# nodeTestPanel.net
KiCad netlist of a schematic drawn in EAGLE
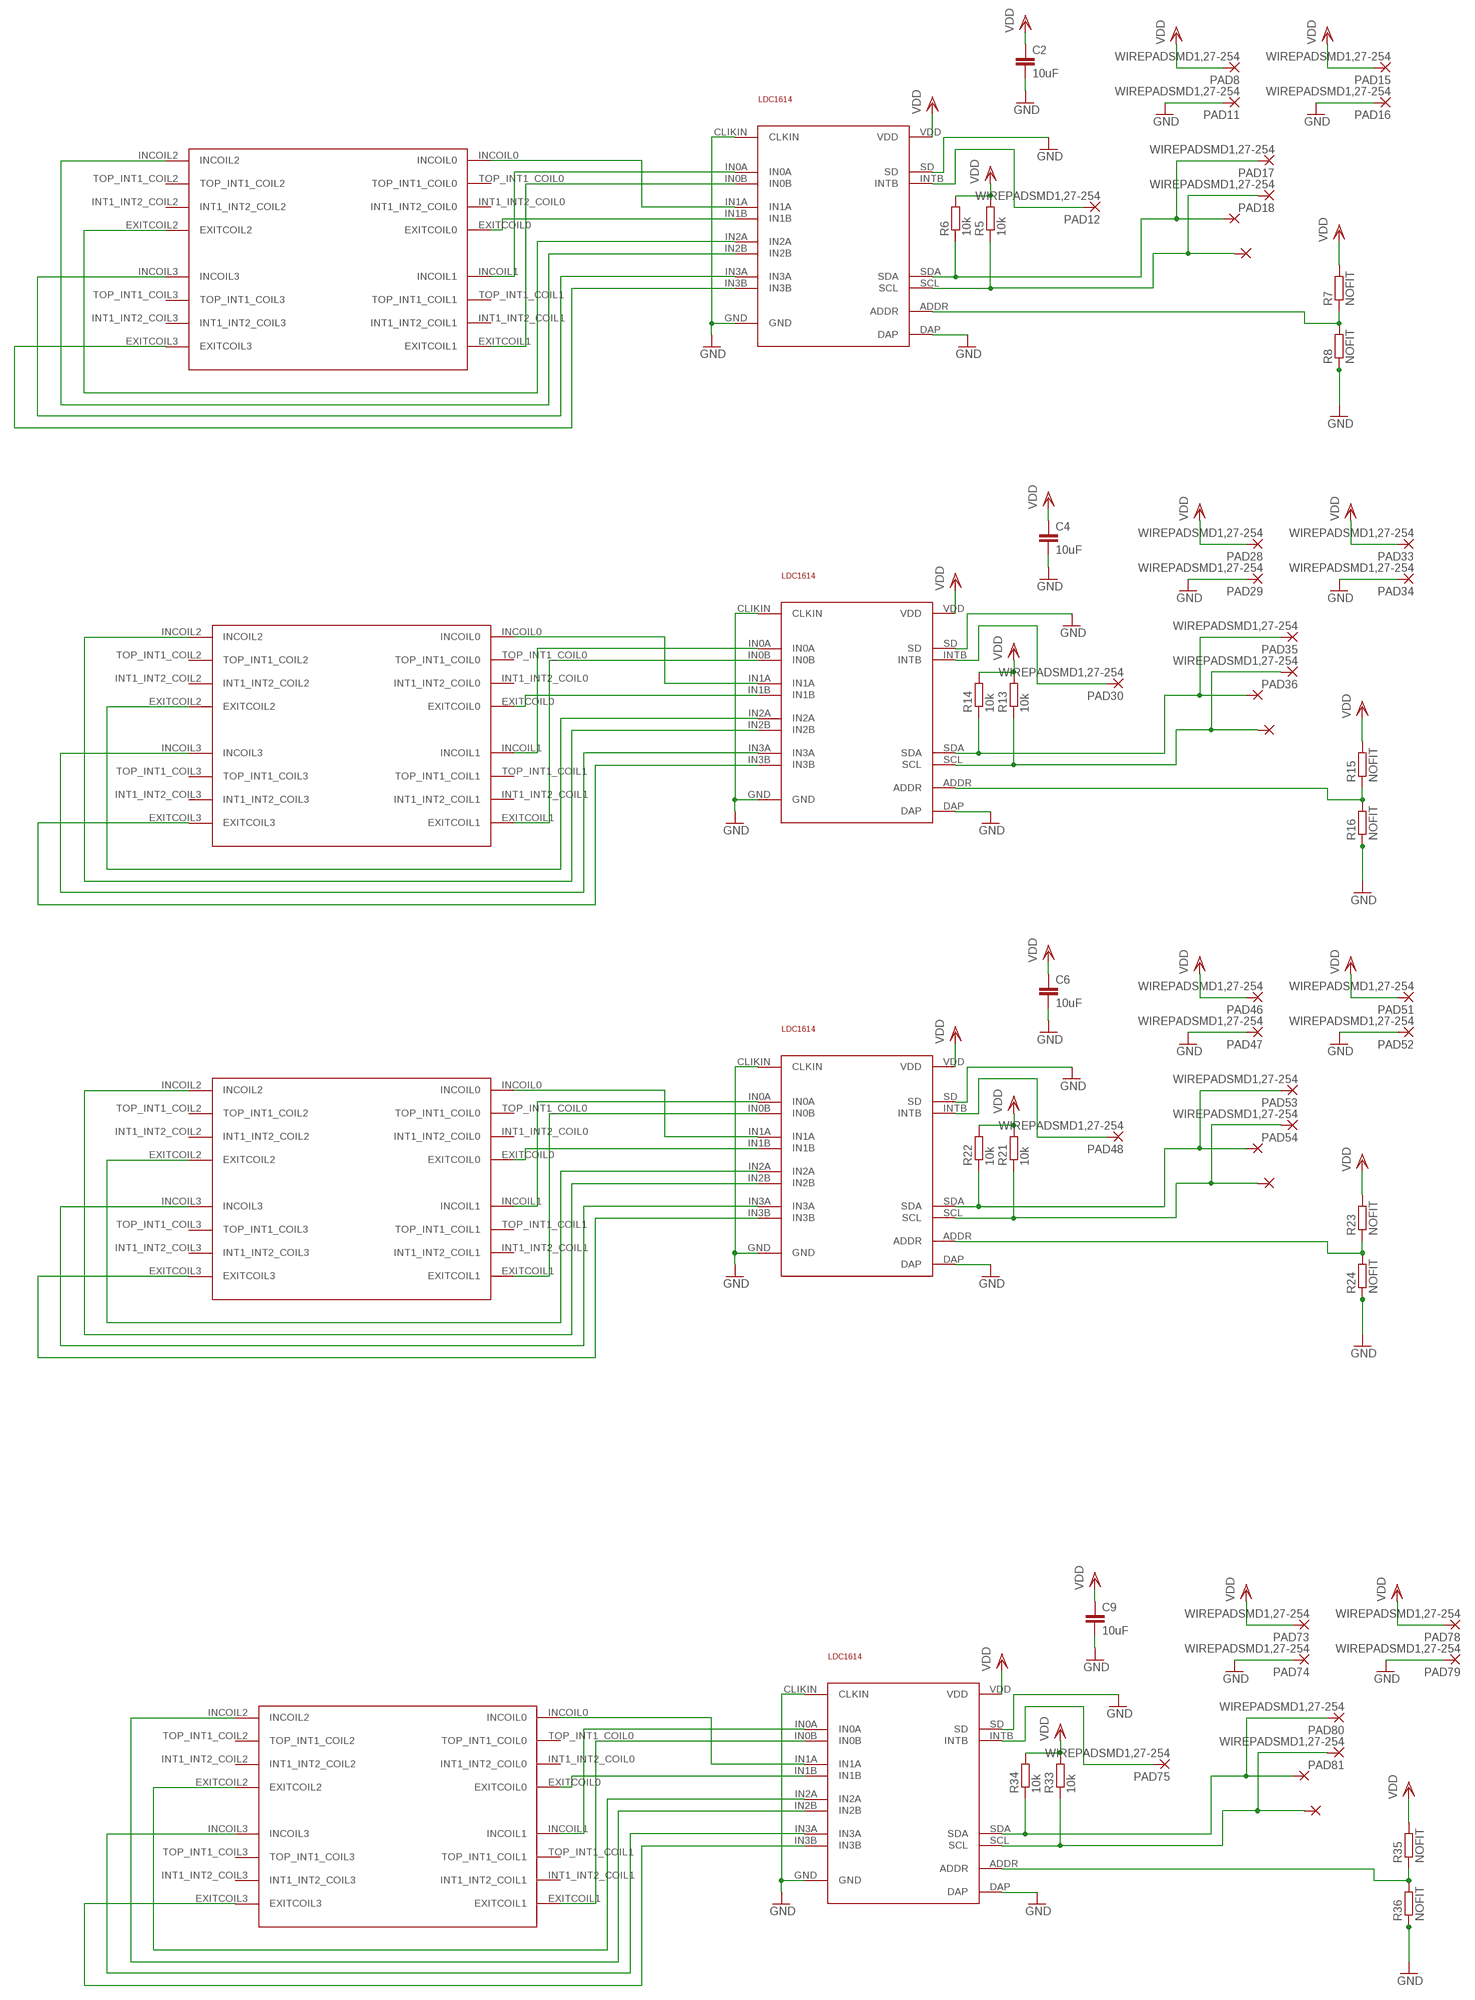
[diagram p0: schematic, sheet 1, part 1 of 3]
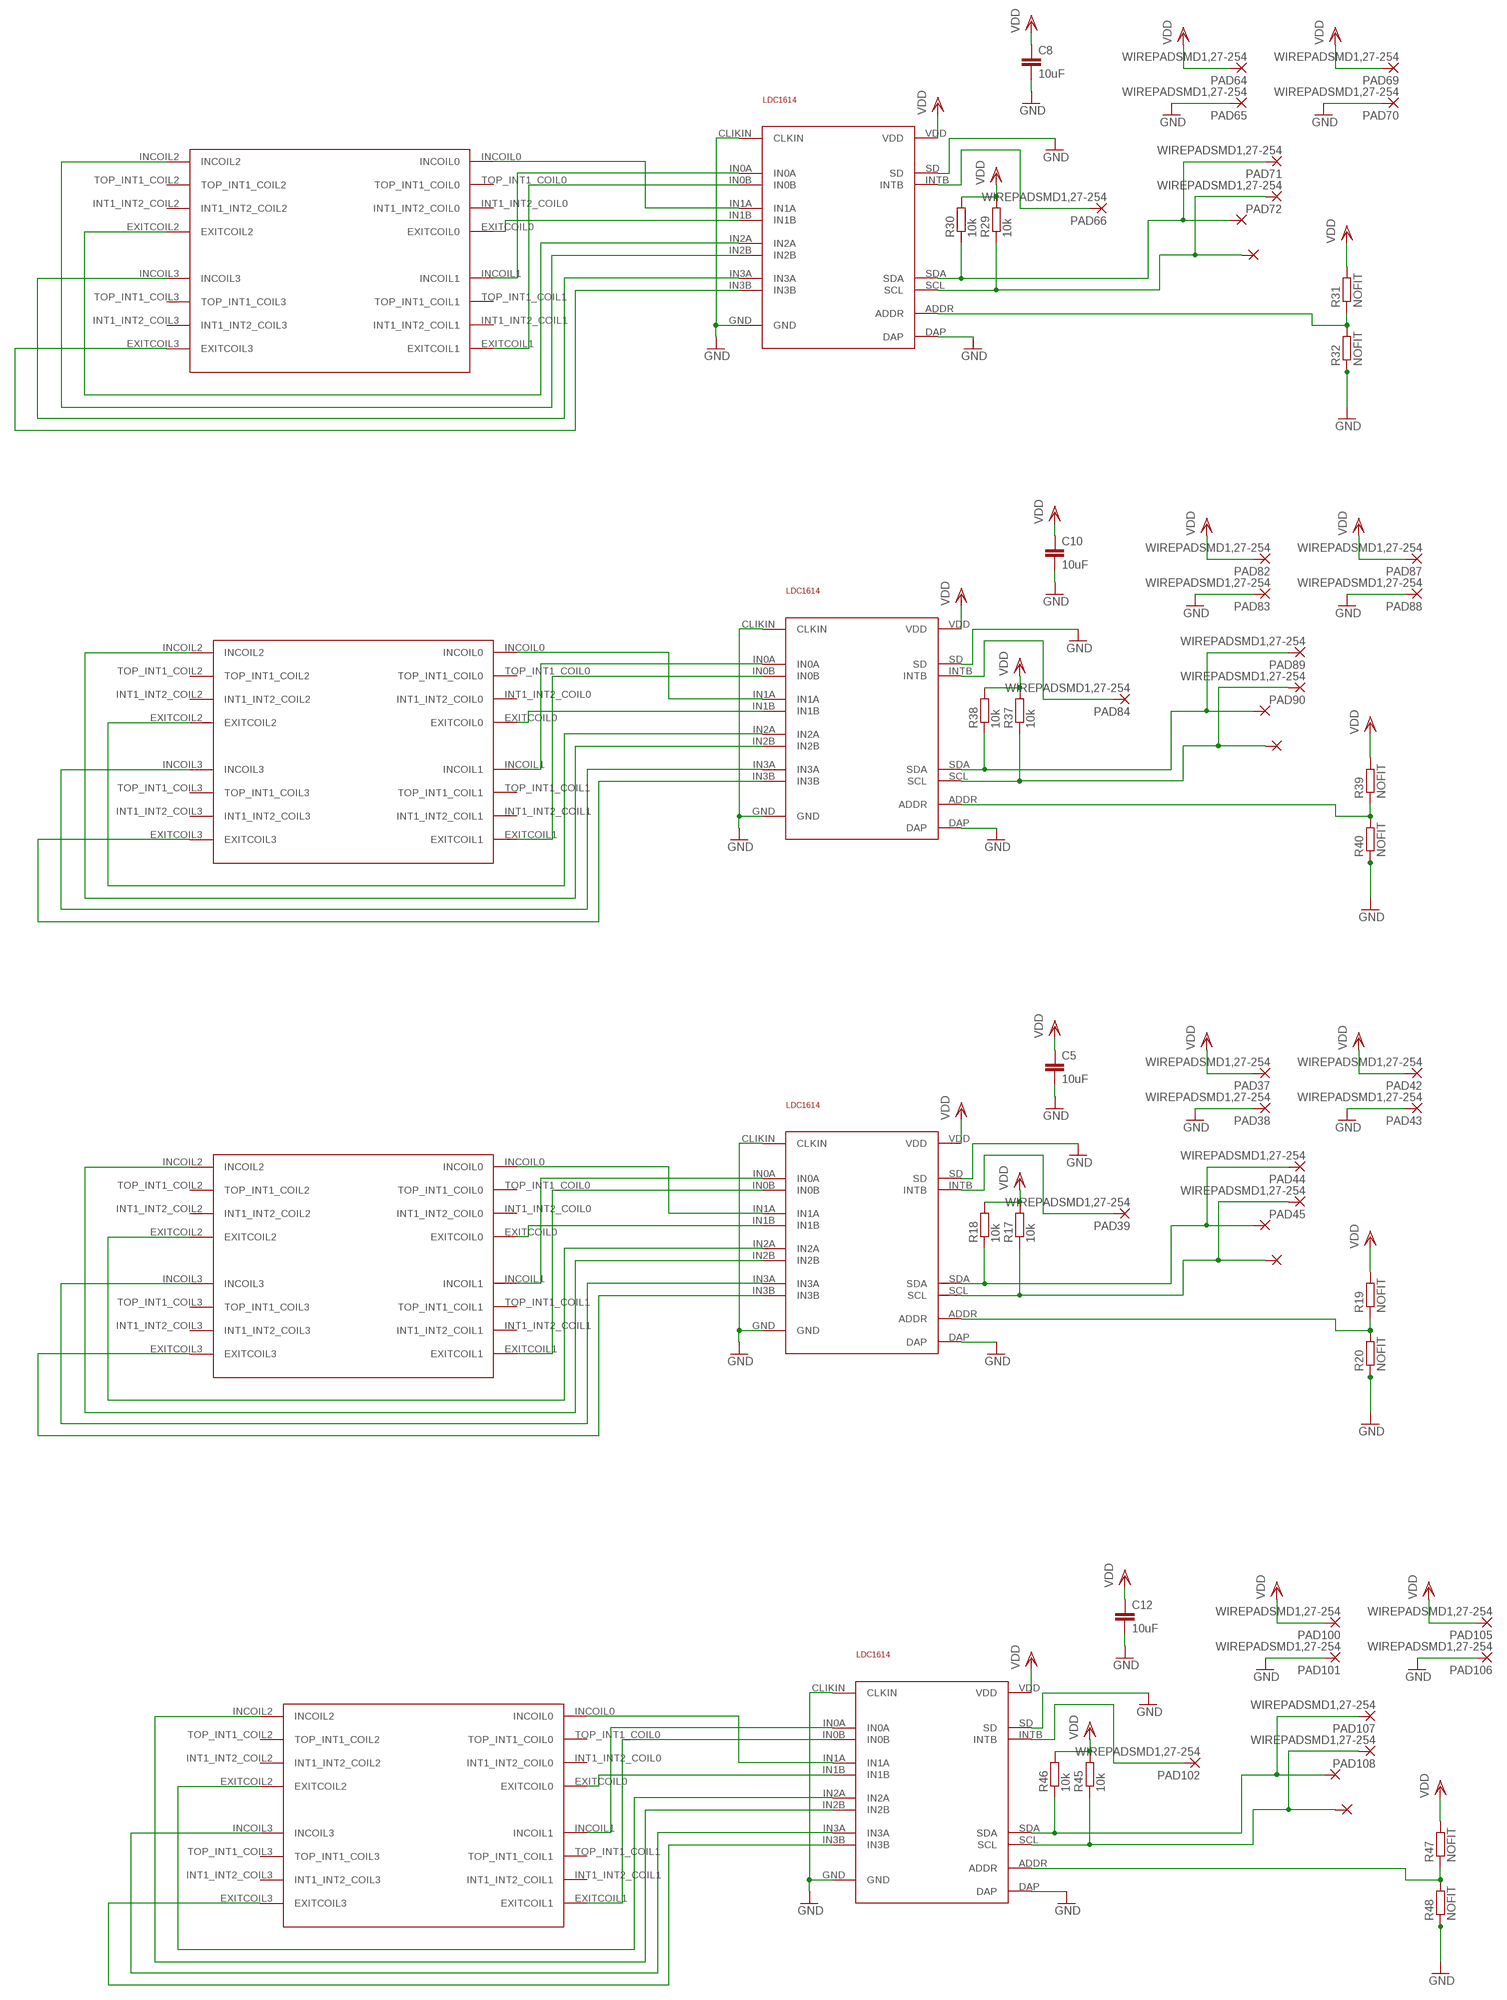
[diagram p1: schematic, sheet 1, part 2 of 3]
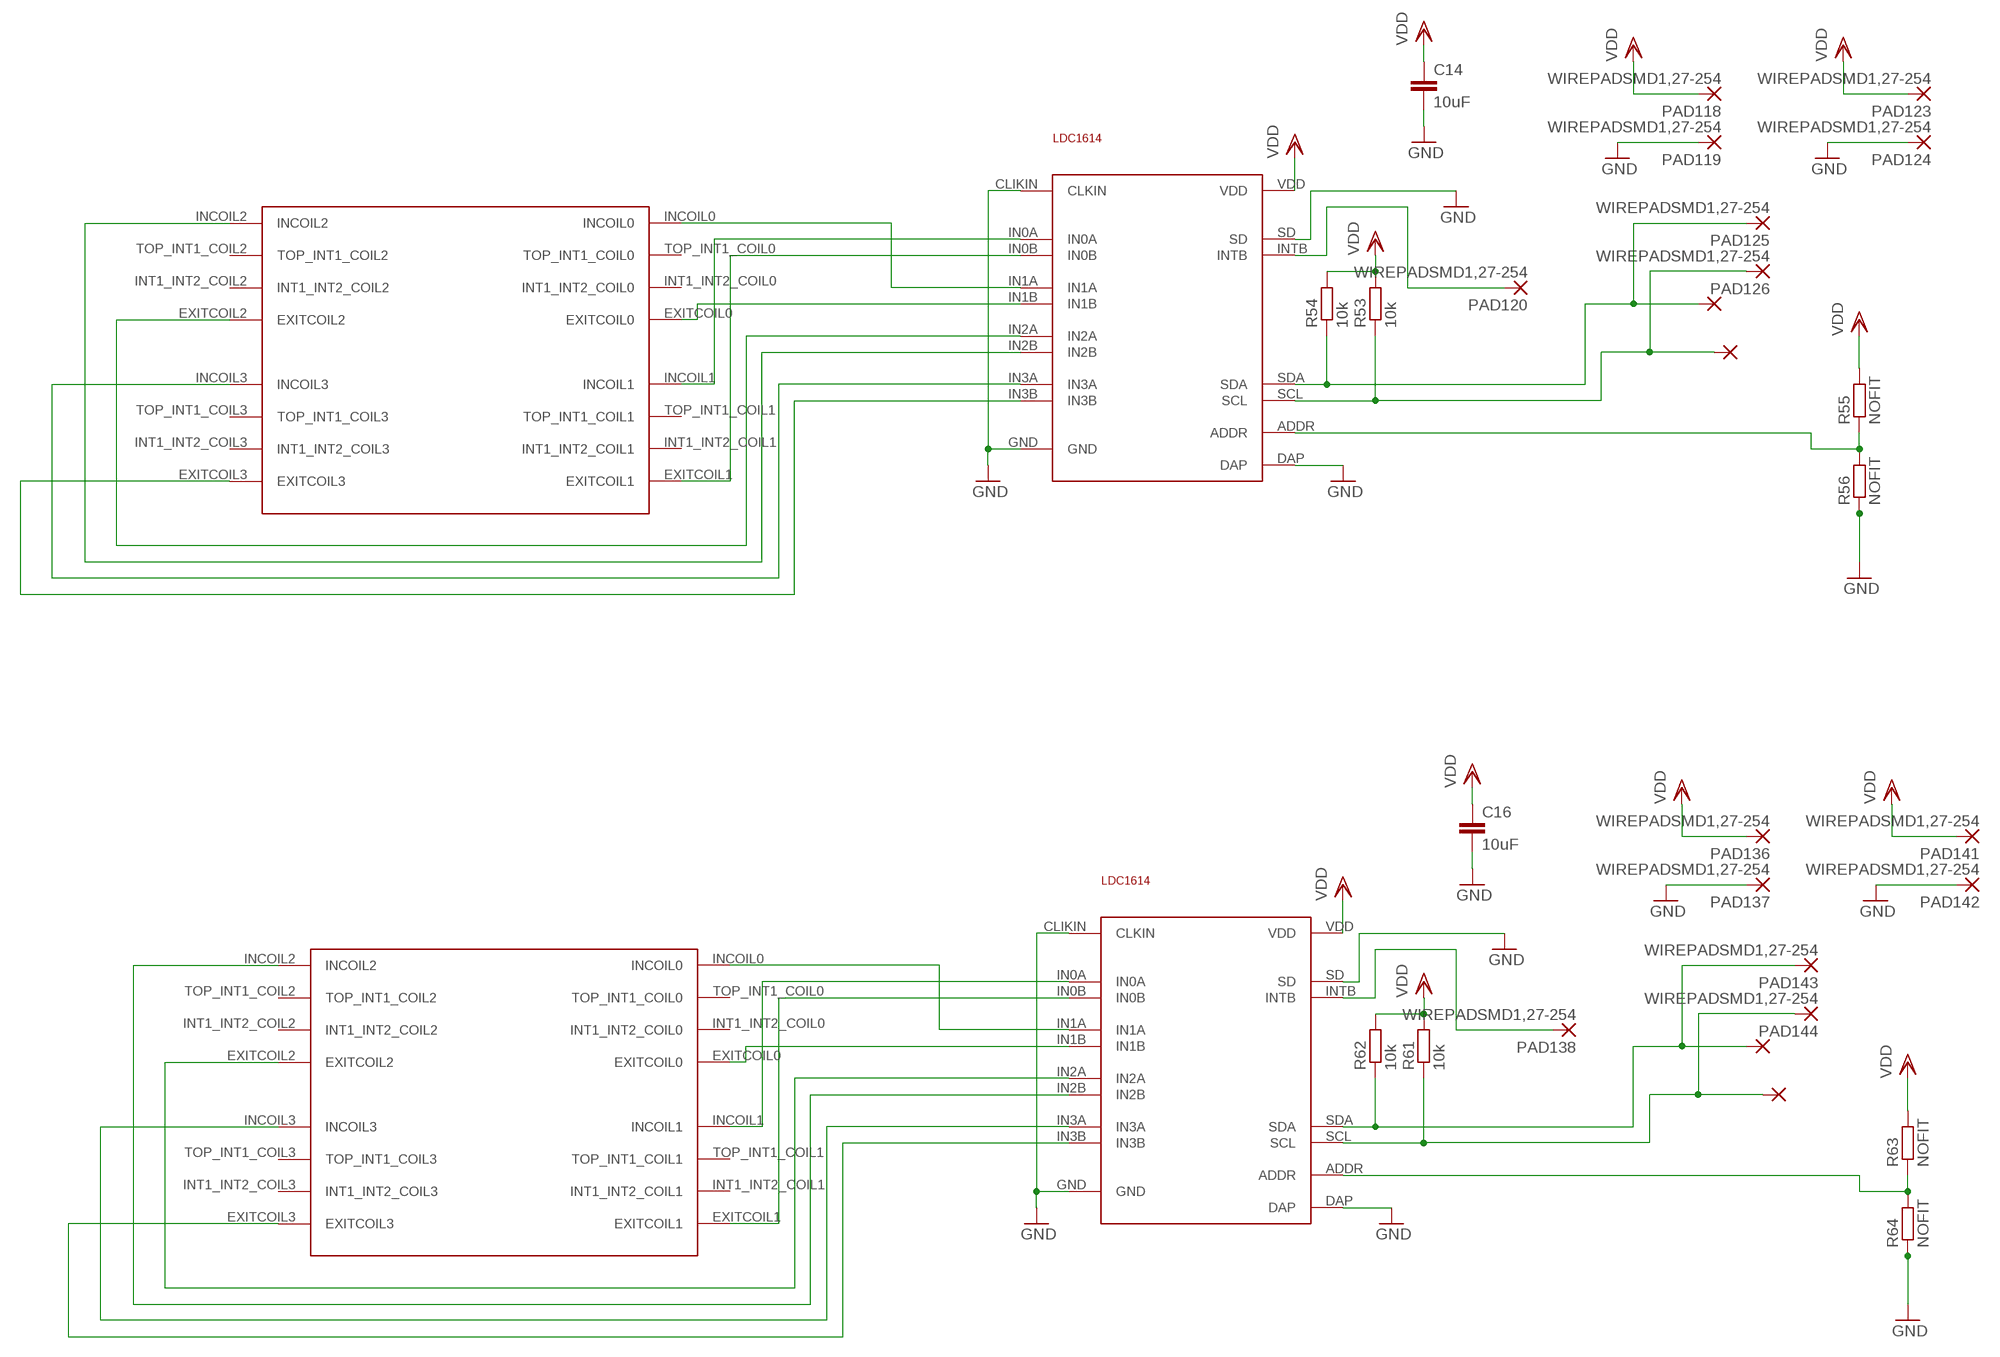
[diagram p2: schematic, sheet 1, part 3 of 3]
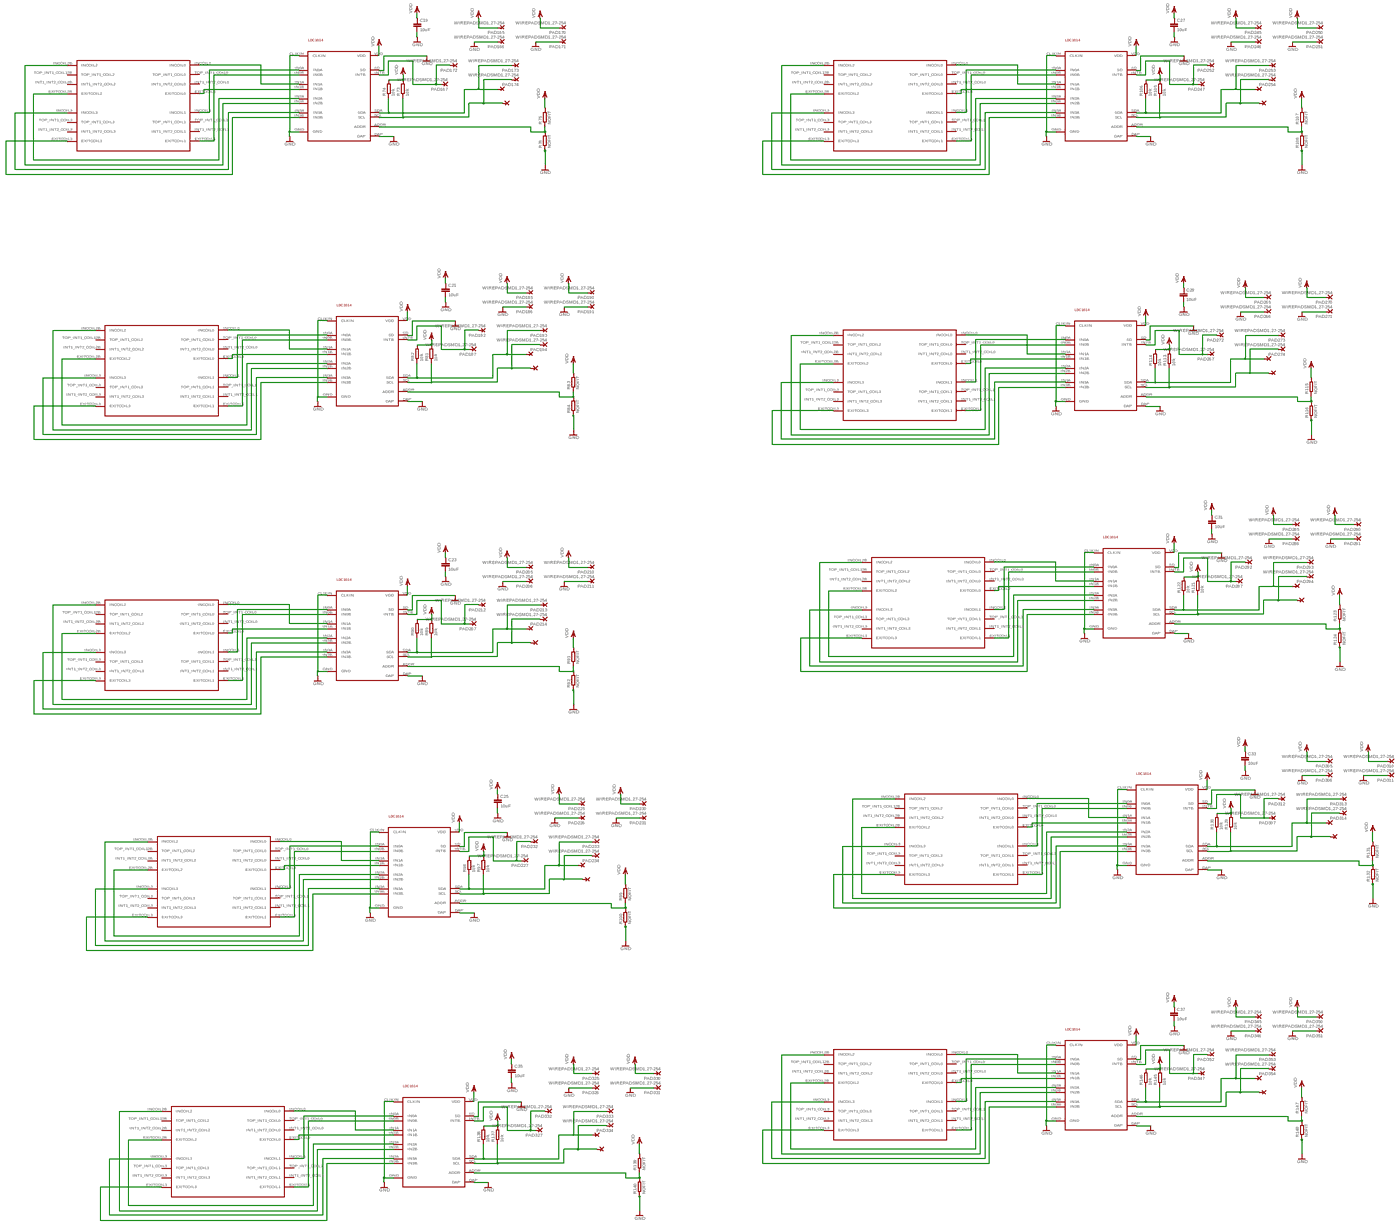
[diagram p3: schematic, sheet 2, overview]
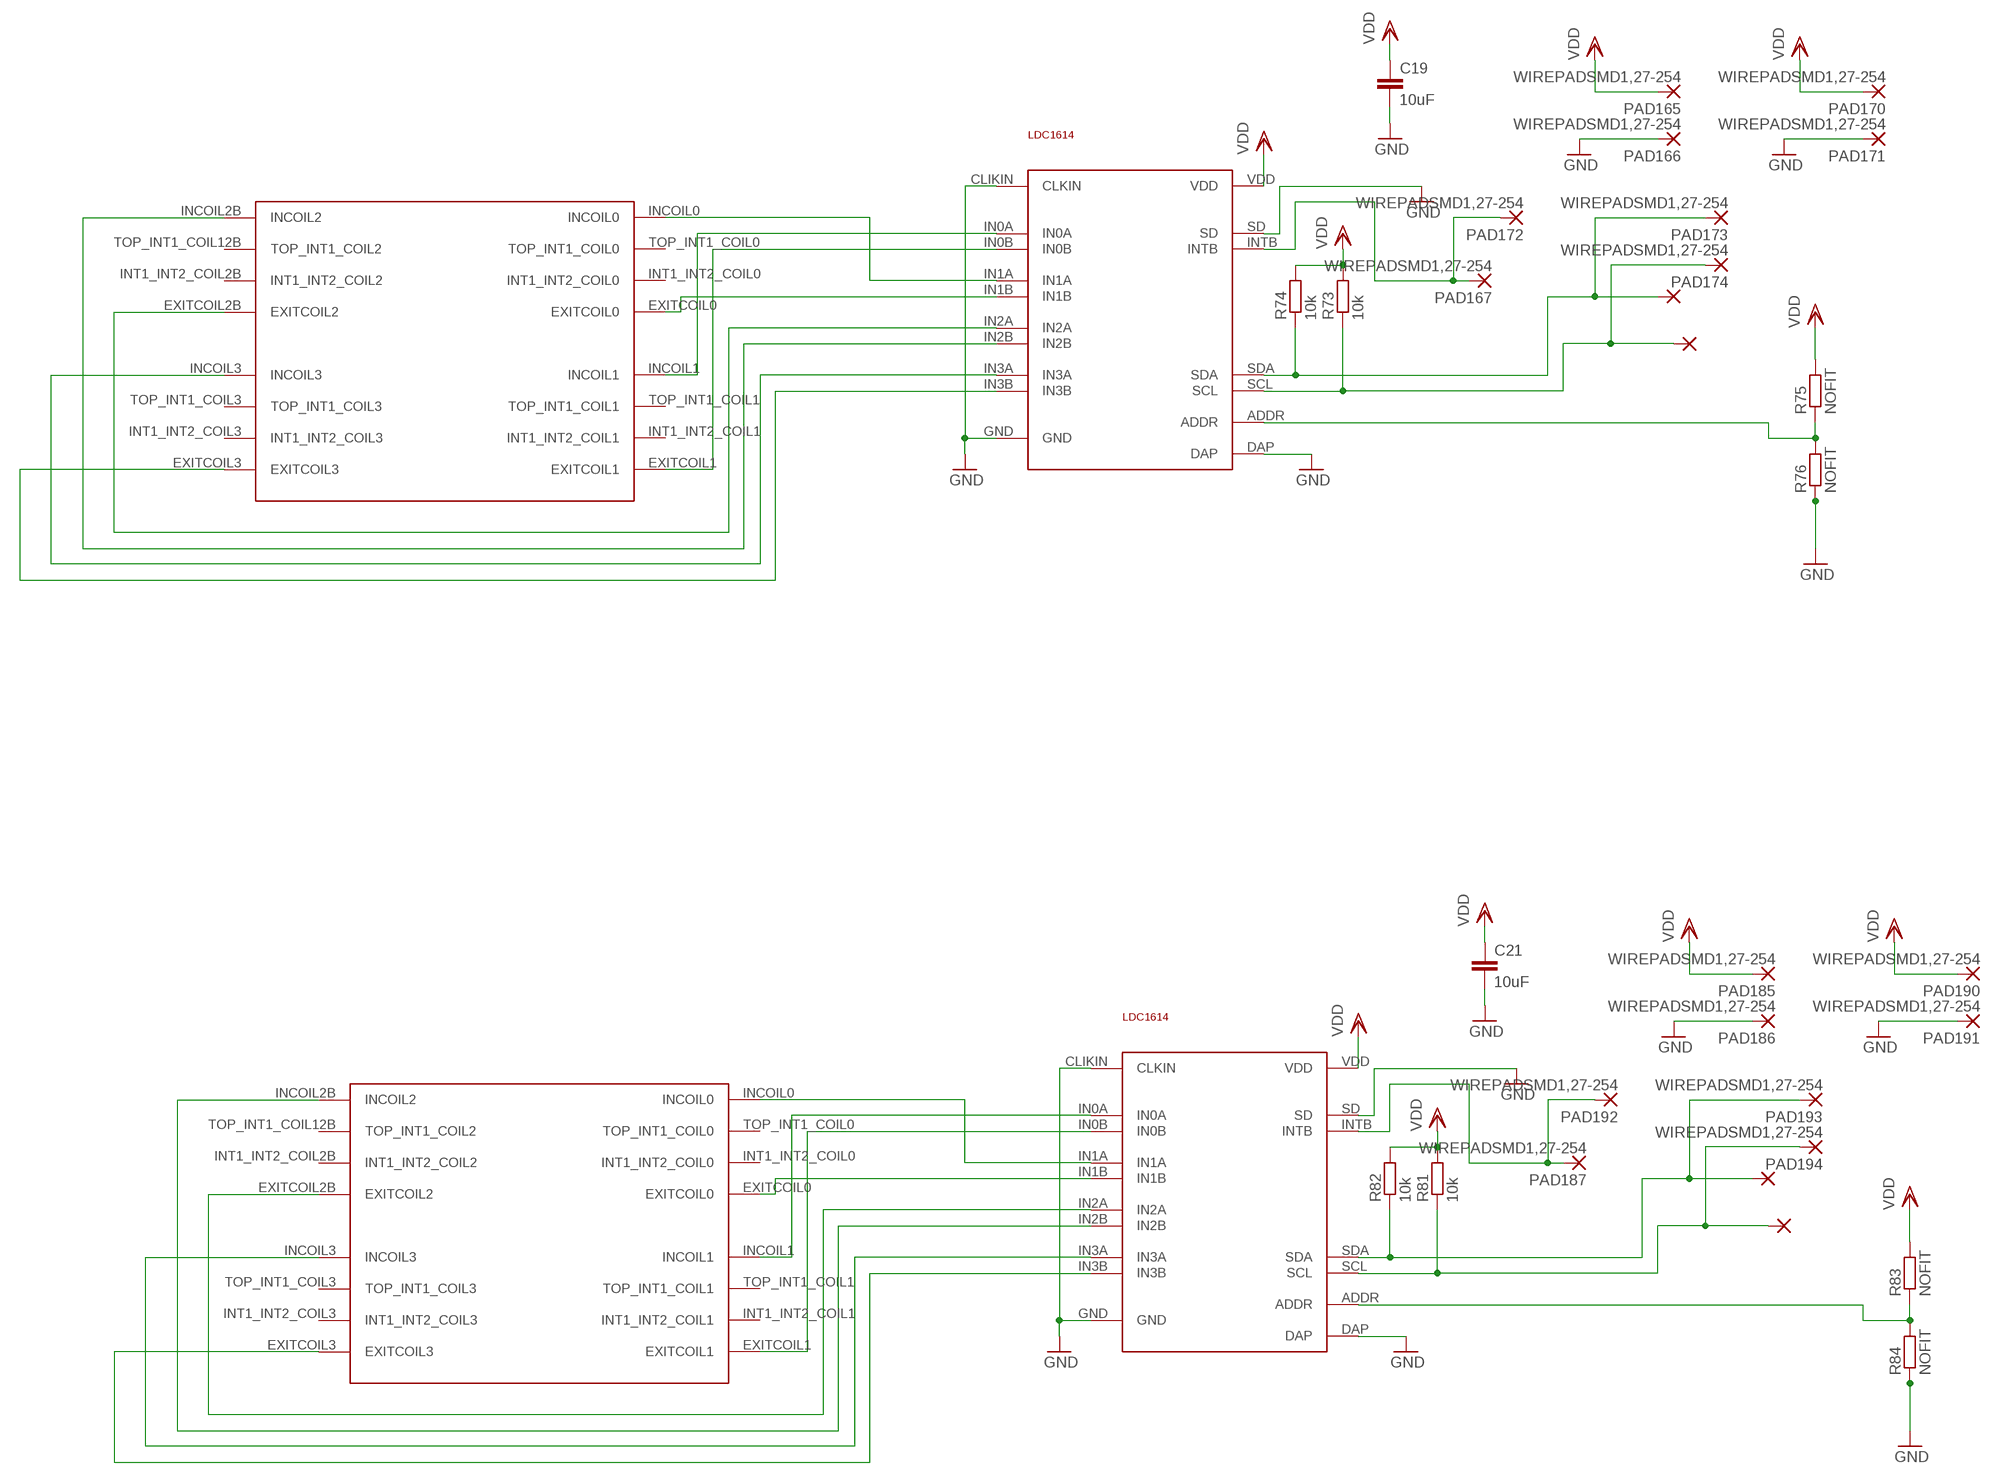
[diagram p4: schematic, sheet 2, part 1 of 4]
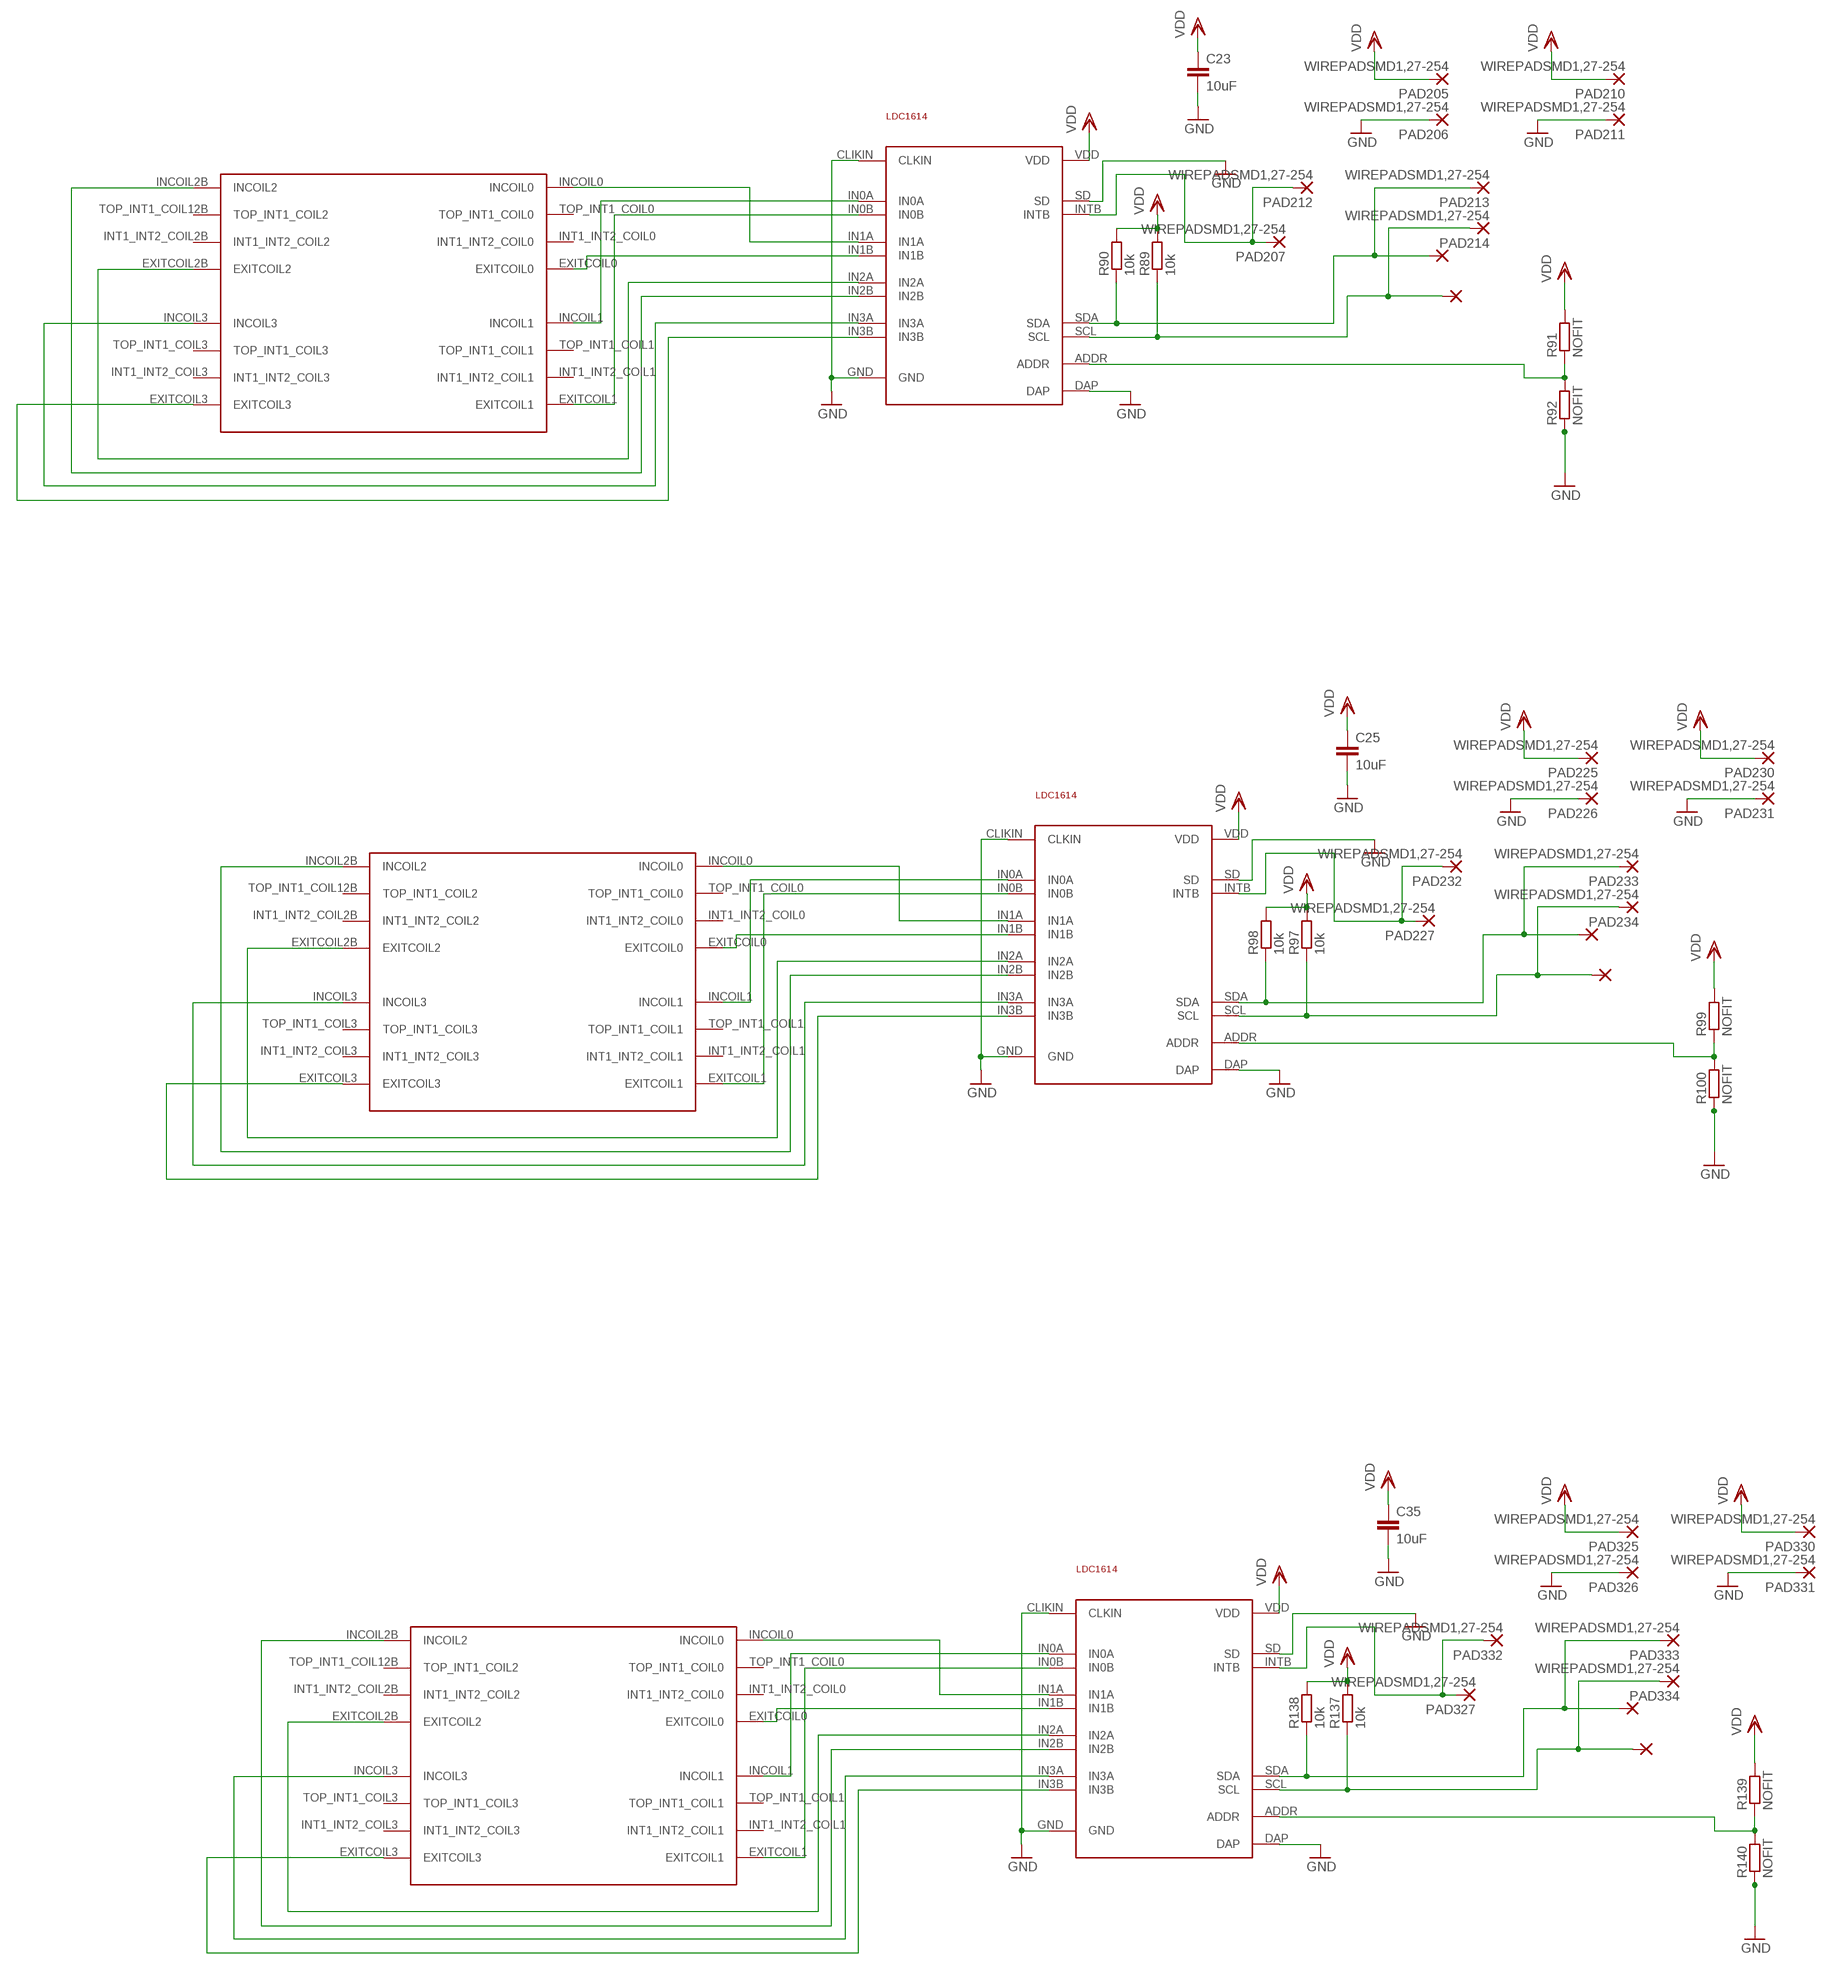
[diagram p5: schematic, sheet 2, part 2 of 4]
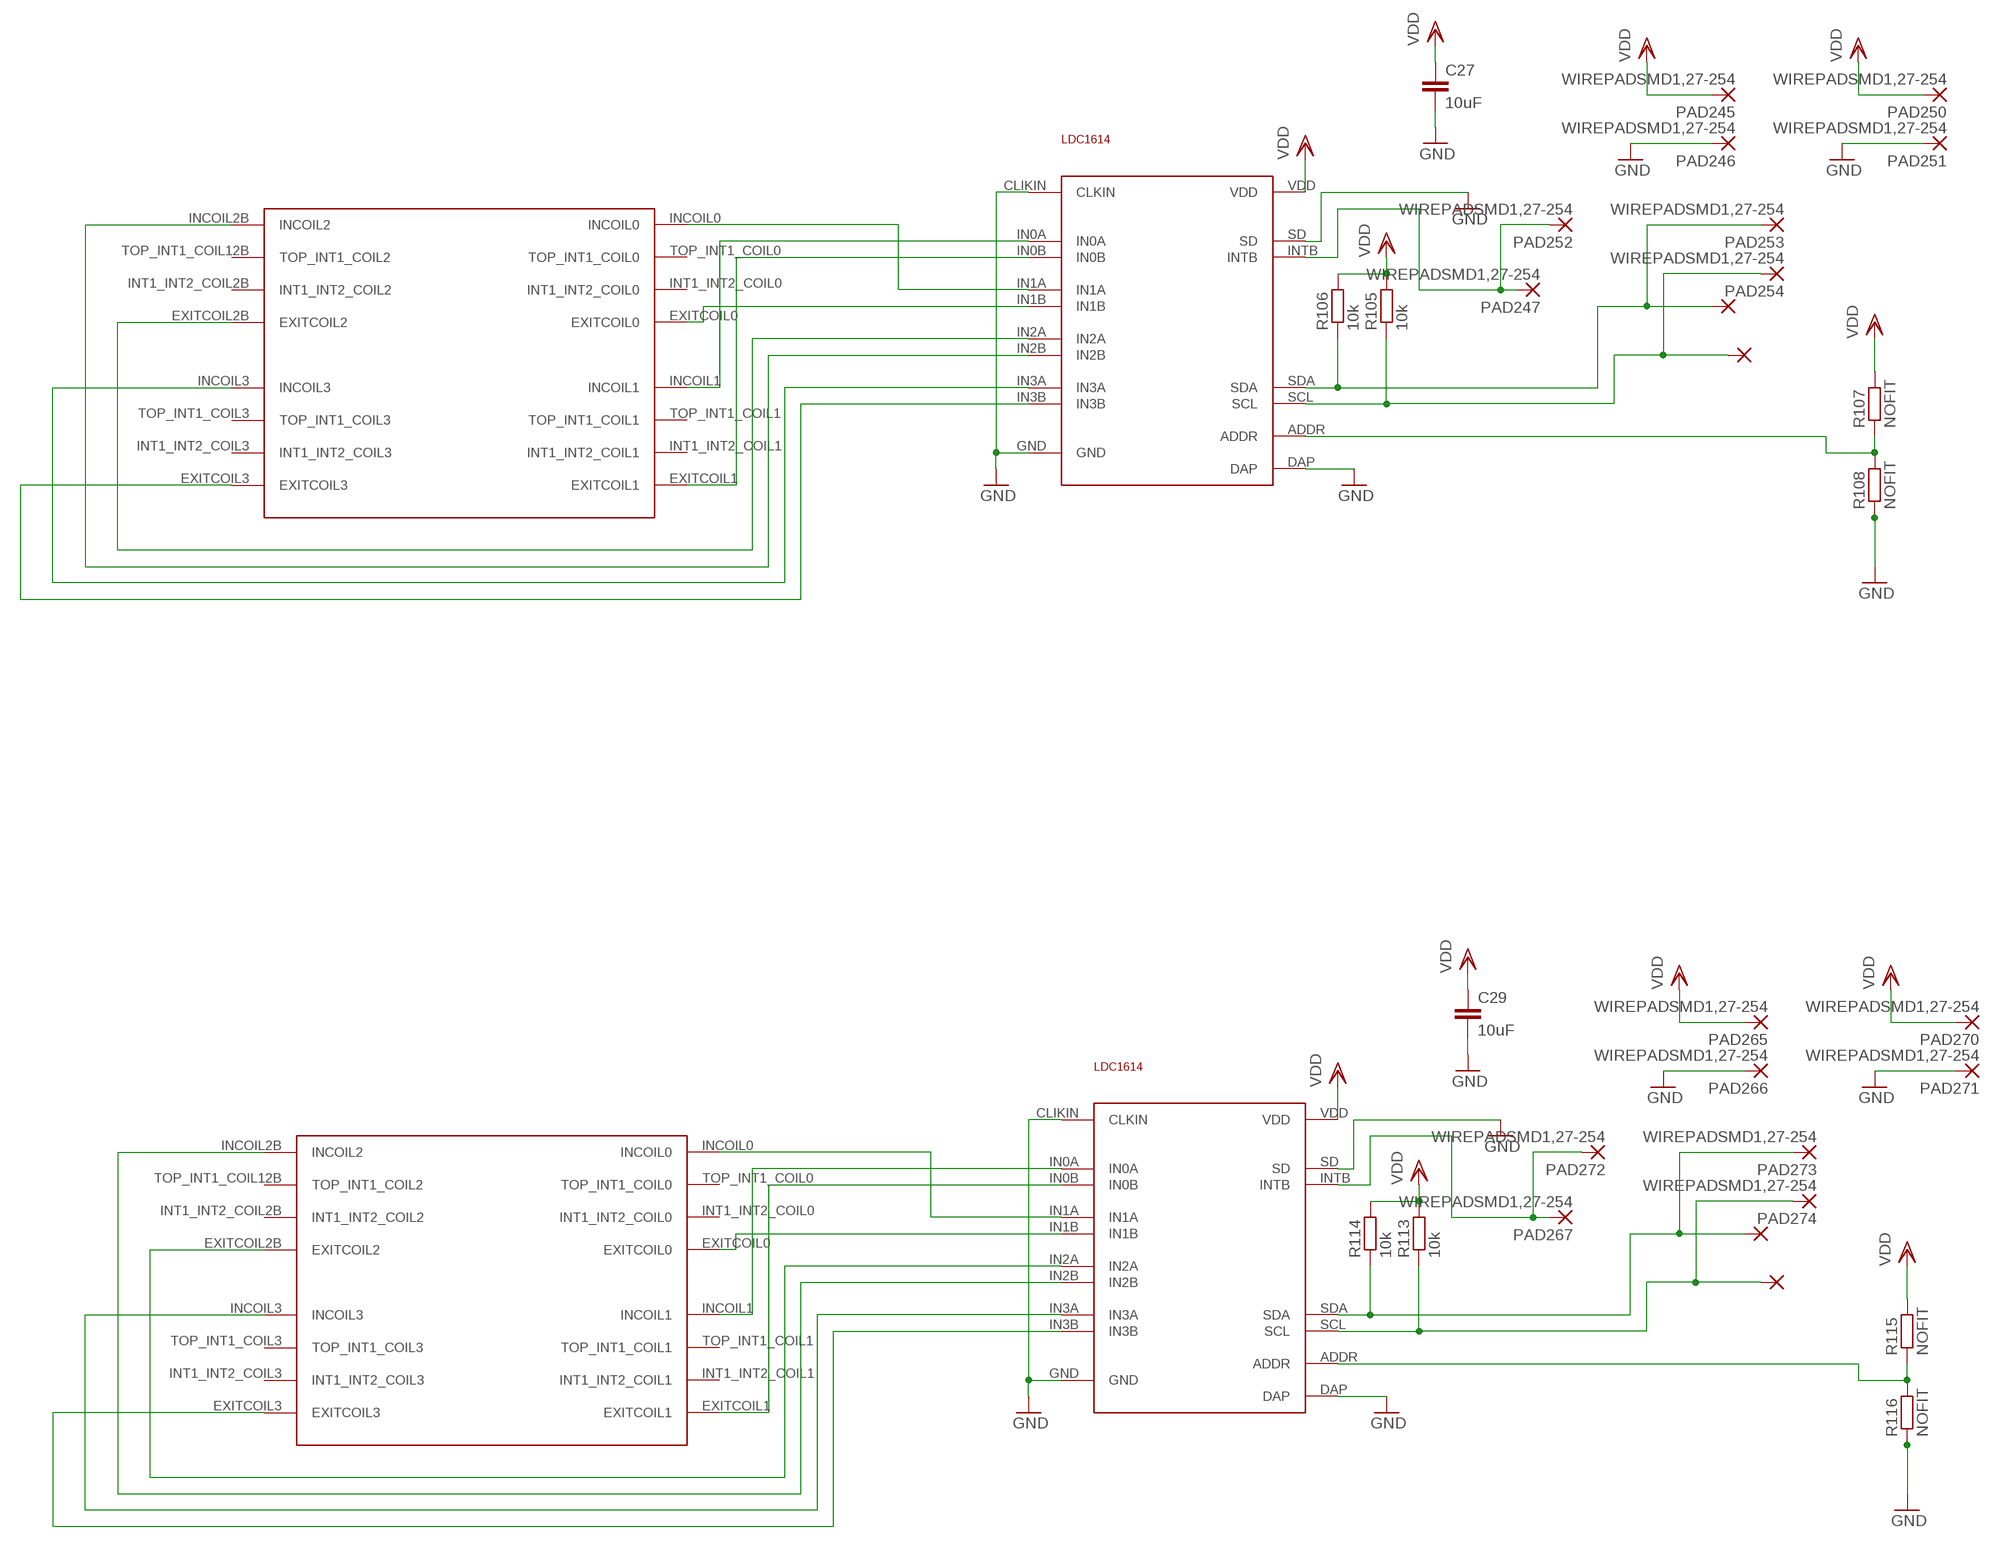
[diagram p6: schematic, sheet 2, part 3 of 4]
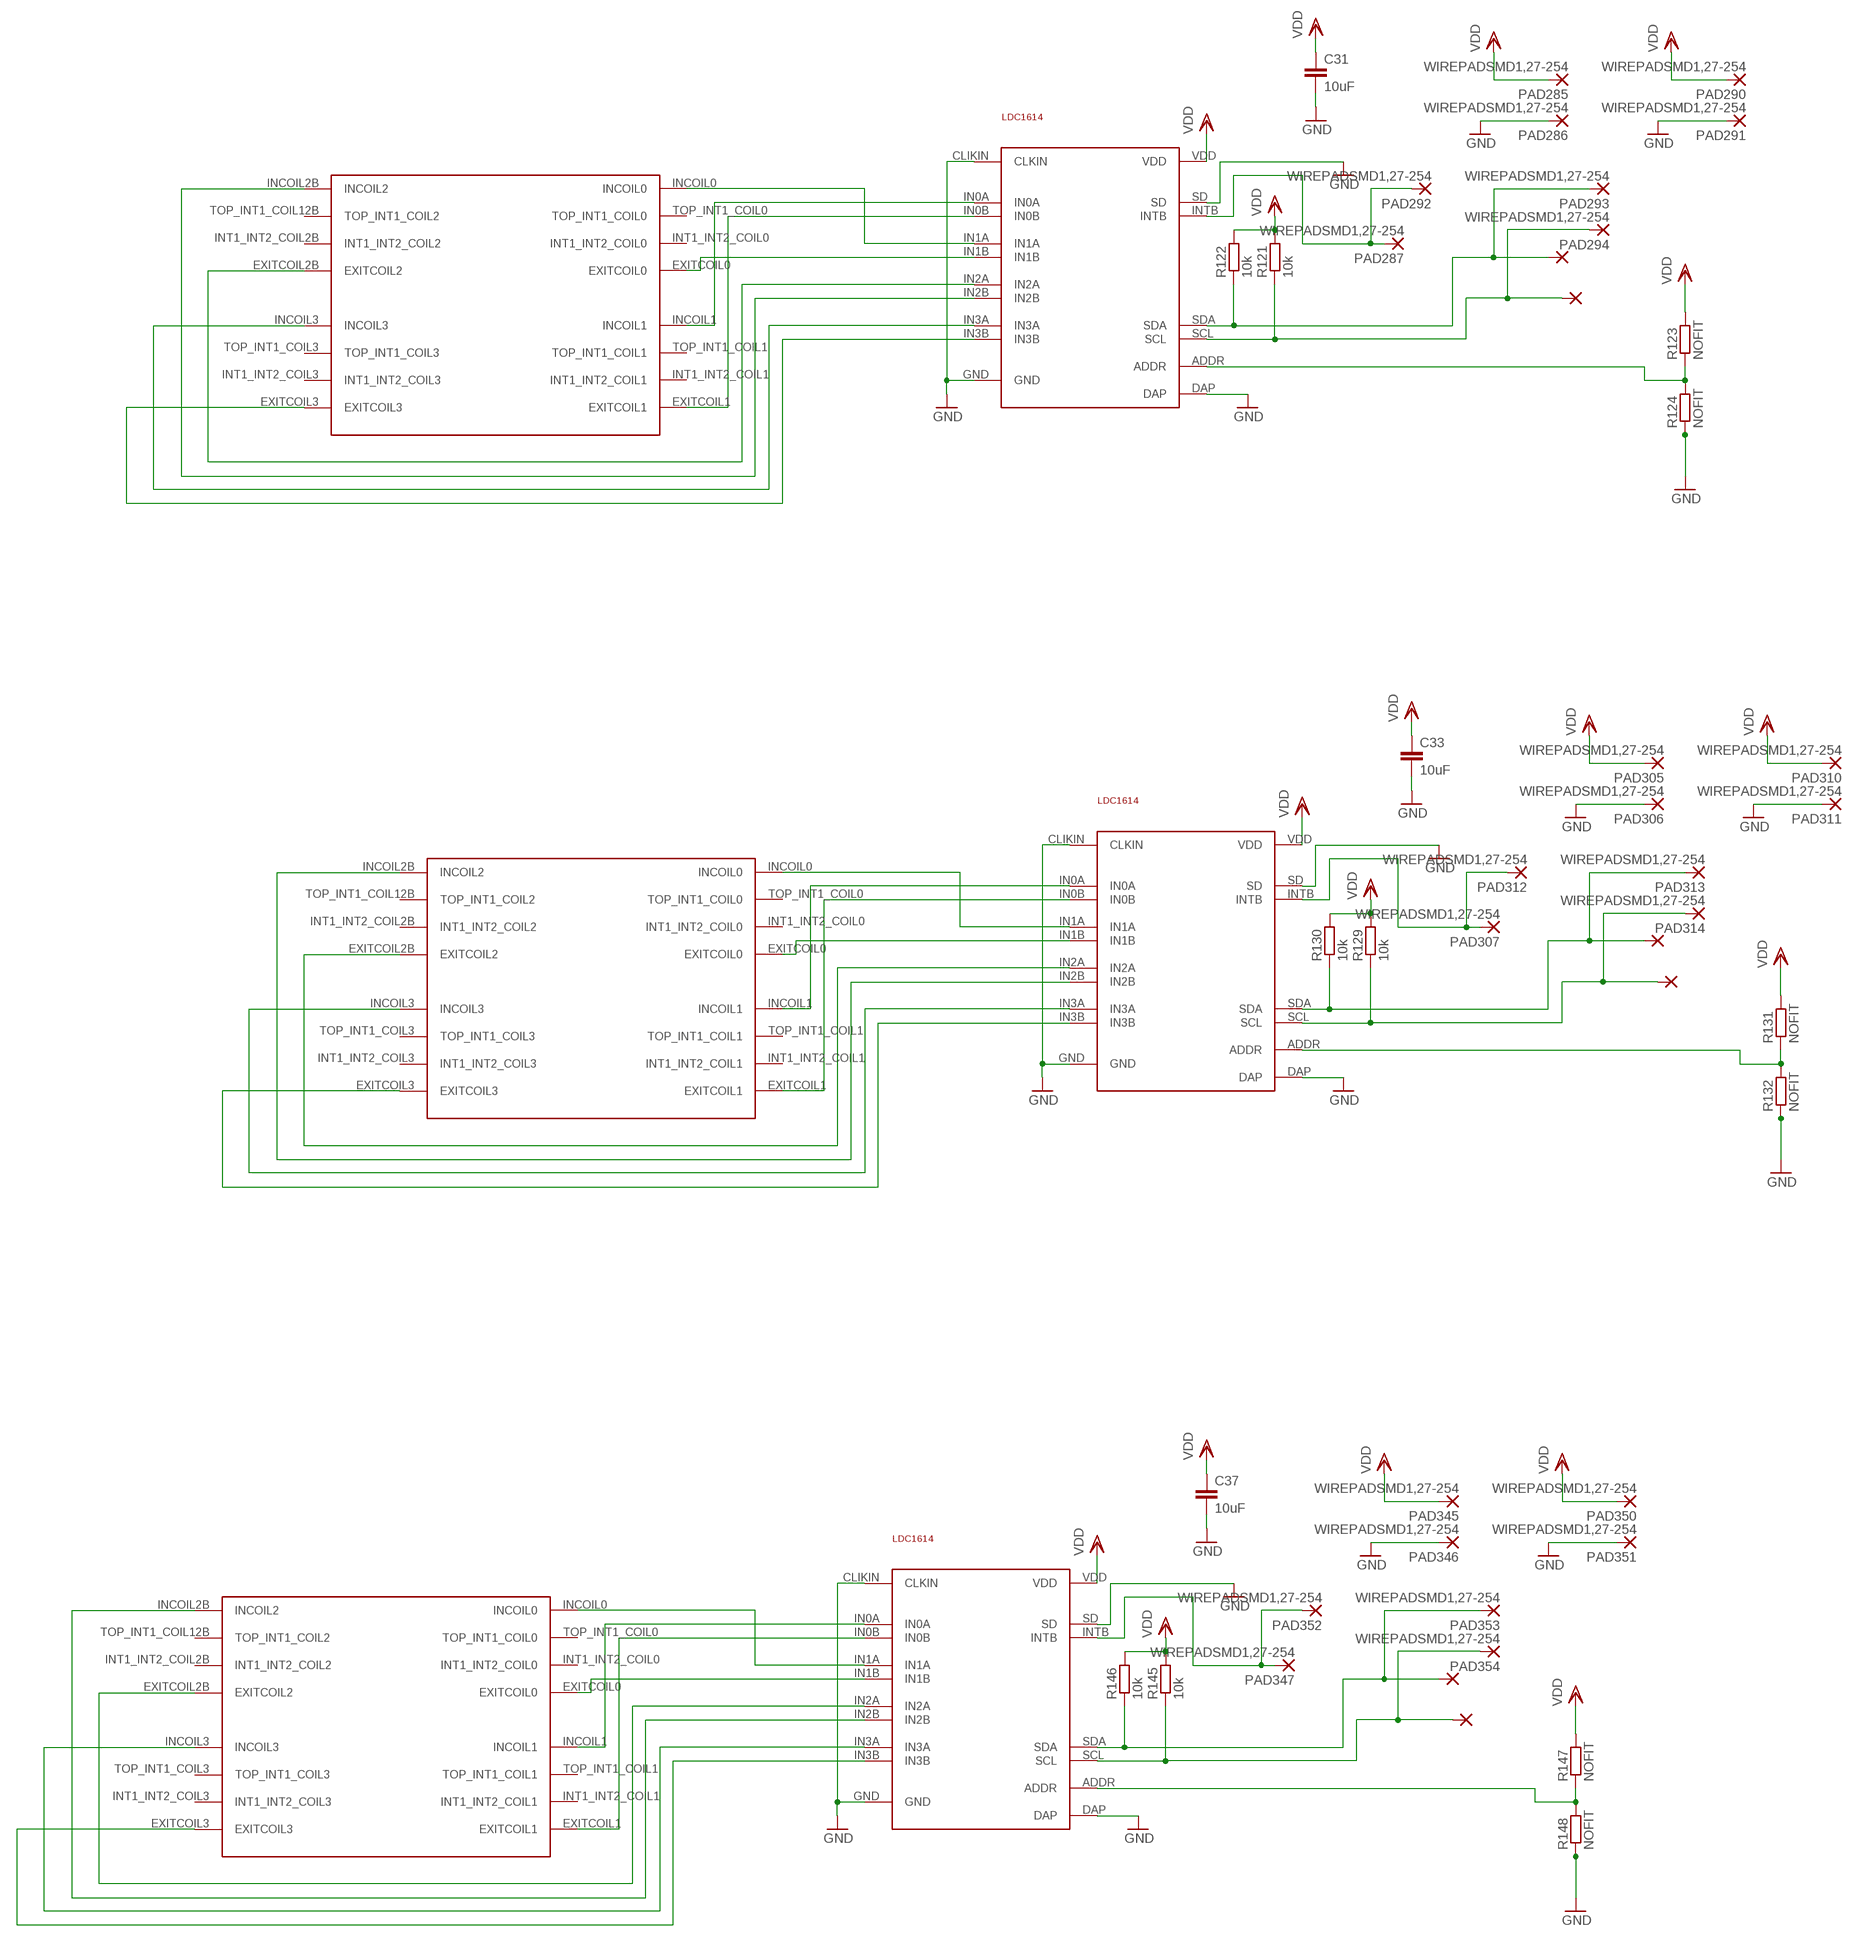
[diagram p7: schematic, sheet 2, part 4 of 4]

(export (version "E")
  (design (tool "Eeschema 10.0.6"))
  (components
    (comp (ref "C19")
      (value "10uF")
      (footprint "eagle-import:C0402")
      (libsource (lib "eagle-import") (part "C-EUC0402"))
    )
    (comp (ref "C21")
      (value "10uF")
      (footprint "eagle-import:C0402")
      (libsource (lib "eagle-import") (part "C-EUC0402"))
    )
    (comp (ref "C23")
      (value "10uF")
      (footprint "eagle-import:C0402")
      (libsource (lib "eagle-import") (part "C-EUC0402"))
    )
    (comp (ref "C25")
      (value "10uF")
      (footprint "eagle-import:C0402")
      (libsource (lib "eagle-import") (part "C-EUC0402"))
    )
    (comp (ref "C27")
      (value "10uF")
      (footprint "eagle-import:C0402")
      (libsource (lib "eagle-import") (part "C-EUC0402"))
    )
    (comp (ref "C29")
      (value "10uF")
      (footprint "eagle-import:C0402")
      (libsource (lib "eagle-import") (part "C-EUC0402"))
    )
    (comp (ref "C31")
      (value "10uF")
      (footprint "eagle-import:C0402")
      (libsource (lib "eagle-import") (part "C-EUC0402"))
    )
    (comp (ref "C33")
      (value "10uF")
      (footprint "eagle-import:C0402")
      (libsource (lib "eagle-import") (part "C-EUC0402"))
    )
    (comp (ref "C35")
      (value "10uF")
      (footprint "eagle-import:C0402")
      (libsource (lib "eagle-import") (part "C-EUC0402"))
    )
    (comp (ref "C37")
      (value "10uF")
      (footprint "eagle-import:C0402")
      (libsource (lib "eagle-import") (part "C-EUC0402"))
    )
    (comp (ref "PAD165")
      (value "WIREPADSMD1,27-254")
      (footprint "eagle-import:SMD1,27-2,54")
      (libsource (lib "eagle-import") (part "WIREPADSMD1,27-254"))
    )
    (comp (ref "PAD166")
      (value "WIREPADSMD1,27-254")
      (footprint "eagle-import:SMD1,27-2,54")
      (libsource (lib "eagle-import") (part "WIREPADSMD1,27-254"))
    )
    (comp (ref "PAD167")
      (value "WIREPADSMD1,27-254")
      (footprint "eagle-import:SMD1,27-2,54")
      (libsource (lib "eagle-import") (part "WIREPADSMD1,27-254"))
    )
    (comp (ref "PAD168")
      (value "WIREPADSMD1,27-254")
      (footprint "eagle-import:SMD1,27-2,54")
      (libsource (lib "eagle-import") (part "WIREPADSMD1,27-254"))
    )
    (comp (ref "PAD169")
      (value "WIREPADSMD1,27-254")
      (footprint "eagle-import:SMD1,27-2,54")
      (libsource (lib "eagle-import") (part "WIREPADSMD1,27-254"))
    )
    (comp (ref "PAD170")
      (value "WIREPADSMD1,27-254")
      (footprint "eagle-import:SMD1,27-2,54")
      (libsource (lib "eagle-import") (part "WIREPADSMD1,27-254"))
    )
    (comp (ref "PAD171")
      (value "WIREPADSMD1,27-254")
      (footprint "eagle-import:SMD1,27-2,54")
      (libsource (lib "eagle-import") (part "WIREPADSMD1,27-254"))
    )
    (comp (ref "PAD172")
      (value "WIREPADSMD1,27-254")
      (footprint "eagle-import:SMD1,27-2,54")
      (libsource (lib "eagle-import") (part "WIREPADSMD1,27-254"))
    )
    (comp (ref "PAD173")
      (value "WIREPADSMD1,27-254")
      (footprint "eagle-import:SMD1,27-2,54")
      (libsource (lib "eagle-import") (part "WIREPADSMD1,27-254"))
    )
    (comp (ref "PAD174")
      (value "WIREPADSMD1,27-254")
      (footprint "eagle-import:SMD1,27-2,54")
      (libsource (lib "eagle-import") (part "WIREPADSMD1,27-254"))
    )
    (comp (ref "PAD185")
      (value "WIREPADSMD1,27-254")
      (footprint "eagle-import:SMD1,27-2,54")
      (libsource (lib "eagle-import") (part "WIREPADSMD1,27-254"))
    )
    (comp (ref "PAD186")
      (value "WIREPADSMD1,27-254")
      (footprint "eagle-import:SMD1,27-2,54")
      (libsource (lib "eagle-import") (part "WIREPADSMD1,27-254"))
    )
    (comp (ref "PAD187")
      (value "WIREPADSMD1,27-254")
      (footprint "eagle-import:SMD1,27-2,54")
      (libsource (lib "eagle-import") (part "WIREPADSMD1,27-254"))
    )
    (comp (ref "PAD188")
      (value "WIREPADSMD1,27-254")
      (footprint "eagle-import:SMD1,27-2,54")
      (libsource (lib "eagle-import") (part "WIREPADSMD1,27-254"))
    )
    (comp (ref "PAD189")
      (value "WIREPADSMD1,27-254")
      (footprint "eagle-import:SMD1,27-2,54")
      (libsource (lib "eagle-import") (part "WIREPADSMD1,27-254"))
    )
    (comp (ref "PAD190")
      (value "WIREPADSMD1,27-254")
      (footprint "eagle-import:SMD1,27-2,54")
      (libsource (lib "eagle-import") (part "WIREPADSMD1,27-254"))
    )
    (comp (ref "PAD191")
      (value "WIREPADSMD1,27-254")
      (footprint "eagle-import:SMD1,27-2,54")
      (libsource (lib "eagle-import") (part "WIREPADSMD1,27-254"))
    )
    (comp (ref "PAD192")
      (value "WIREPADSMD1,27-254")
      (footprint "eagle-import:SMD1,27-2,54")
      (libsource (lib "eagle-import") (part "WIREPADSMD1,27-254"))
    )
    (comp (ref "PAD193")
      (value "WIREPADSMD1,27-254")
      (footprint "eagle-import:SMD1,27-2,54")
      (libsource (lib "eagle-import") (part "WIREPADSMD1,27-254"))
    )
    (comp (ref "PAD194")
      (value "WIREPADSMD1,27-254")
      (footprint "eagle-import:SMD1,27-2,54")
      (libsource (lib "eagle-import") (part "WIREPADSMD1,27-254"))
    )
    (comp (ref "PAD205")
      (value "WIREPADSMD1,27-254")
      (footprint "eagle-import:SMD1,27-2,54")
      (libsource (lib "eagle-import") (part "WIREPADSMD1,27-254"))
    )
    (comp (ref "PAD206")
      (value "WIREPADSMD1,27-254")
      (footprint "eagle-import:SMD1,27-2,54")
      (libsource (lib "eagle-import") (part "WIREPADSMD1,27-254"))
    )
    (comp (ref "PAD207")
      (value "WIREPADSMD1,27-254")
      (footprint "eagle-import:SMD1,27-2,54")
      (libsource (lib "eagle-import") (part "WIREPADSMD1,27-254"))
    )
    (comp (ref "PAD208")
      (value "WIREPADSMD1,27-254")
      (footprint "eagle-import:SMD1,27-2,54")
      (libsource (lib "eagle-import") (part "WIREPADSMD1,27-254"))
    )
    (comp (ref "PAD209")
      (value "WIREPADSMD1,27-254")
      (footprint "eagle-import:SMD1,27-2,54")
      (libsource (lib "eagle-import") (part "WIREPADSMD1,27-254"))
    )
    (comp (ref "PAD210")
      (value "WIREPADSMD1,27-254")
      (footprint "eagle-import:SMD1,27-2,54")
      (libsource (lib "eagle-import") (part "WIREPADSMD1,27-254"))
    )
    (comp (ref "PAD211")
      (value "WIREPADSMD1,27-254")
      (footprint "eagle-import:SMD1,27-2,54")
      (libsource (lib "eagle-import") (part "WIREPADSMD1,27-254"))
    )
    (comp (ref "PAD212")
      (value "WIREPADSMD1,27-254")
      (footprint "eagle-import:SMD1,27-2,54")
      (libsource (lib "eagle-import") (part "WIREPADSMD1,27-254"))
    )
    (comp (ref "PAD213")
      (value "WIREPADSMD1,27-254")
      (footprint "eagle-import:SMD1,27-2,54")
      (libsource (lib "eagle-import") (part "WIREPADSMD1,27-254"))
    )
    (comp (ref "PAD214")
      (value "WIREPADSMD1,27-254")
      (footprint "eagle-import:SMD1,27-2,54")
      (libsource (lib "eagle-import") (part "WIREPADSMD1,27-254"))
    )
    (comp (ref "PAD225")
      (value "WIREPADSMD1,27-254")
      (footprint "eagle-import:SMD1,27-2,54")
      (libsource (lib "eagle-import") (part "WIREPADSMD1,27-254"))
    )
    (comp (ref "PAD226")
      (value "WIREPADSMD1,27-254")
      (footprint "eagle-import:SMD1,27-2,54")
      (libsource (lib "eagle-import") (part "WIREPADSMD1,27-254"))
    )
    (comp (ref "PAD227")
      (value "WIREPADSMD1,27-254")
      (footprint "eagle-import:SMD1,27-2,54")
      (libsource (lib "eagle-import") (part "WIREPADSMD1,27-254"))
    )
    (comp (ref "PAD228")
      (value "WIREPADSMD1,27-254")
      (footprint "eagle-import:SMD1,27-2,54")
      (libsource (lib "eagle-import") (part "WIREPADSMD1,27-254"))
    )
    (comp (ref "PAD229")
      (value "WIREPADSMD1,27-254")
      (footprint "eagle-import:SMD1,27-2,54")
      (libsource (lib "eagle-import") (part "WIREPADSMD1,27-254"))
    )
    (comp (ref "PAD230")
      (value "WIREPADSMD1,27-254")
      (footprint "eagle-import:SMD1,27-2,54")
      (libsource (lib "eagle-import") (part "WIREPADSMD1,27-254"))
    )
    (comp (ref "PAD231")
      (value "WIREPADSMD1,27-254")
      (footprint "eagle-import:SMD1,27-2,54")
      (libsource (lib "eagle-import") (part "WIREPADSMD1,27-254"))
    )
    (comp (ref "PAD232")
      (value "WIREPADSMD1,27-254")
      (footprint "eagle-import:SMD1,27-2,54")
      (libsource (lib "eagle-import") (part "WIREPADSMD1,27-254"))
    )
    (comp (ref "PAD233")
      (value "WIREPADSMD1,27-254")
      (footprint "eagle-import:SMD1,27-2,54")
      (libsource (lib "eagle-import") (part "WIREPADSMD1,27-254"))
    )
    (comp (ref "PAD234")
      (value "WIREPADSMD1,27-254")
      (footprint "eagle-import:SMD1,27-2,54")
      (libsource (lib "eagle-import") (part "WIREPADSMD1,27-254"))
    )
    (comp (ref "PAD245")
      (value "WIREPADSMD1,27-254")
      (footprint "eagle-import:SMD1,27-2,54")
      (libsource (lib "eagle-import") (part "WIREPADSMD1,27-254"))
    )
    (comp (ref "PAD246")
      (value "WIREPADSMD1,27-254")
      (footprint "eagle-import:SMD1,27-2,54")
      (libsource (lib "eagle-import") (part "WIREPADSMD1,27-254"))
    )
    (comp (ref "PAD247")
      (value "WIREPADSMD1,27-254")
      (footprint "eagle-import:SMD1,27-2,54")
      (libsource (lib "eagle-import") (part "WIREPADSMD1,27-254"))
    )
    (comp (ref "PAD248")
      (value "WIREPADSMD1,27-254")
      (footprint "eagle-import:SMD1,27-2,54")
      (libsource (lib "eagle-import") (part "WIREPADSMD1,27-254"))
    )
    (comp (ref "PAD249")
      (value "WIREPADSMD1,27-254")
      (footprint "eagle-import:SMD1,27-2,54")
      (libsource (lib "eagle-import") (part "WIREPADSMD1,27-254"))
    )
    (comp (ref "PAD250")
      (value "WIREPADSMD1,27-254")
      (footprint "eagle-import:SMD1,27-2,54")
      (libsource (lib "eagle-import") (part "WIREPADSMD1,27-254"))
    )
    (comp (ref "PAD251")
      (value "WIREPADSMD1,27-254")
      (footprint "eagle-import:SMD1,27-2,54")
      (libsource (lib "eagle-import") (part "WIREPADSMD1,27-254"))
    )
    (comp (ref "PAD252")
      (value "WIREPADSMD1,27-254")
      (footprint "eagle-import:SMD1,27-2,54")
      (libsource (lib "eagle-import") (part "WIREPADSMD1,27-254"))
    )
    (comp (ref "PAD253")
      (value "WIREPADSMD1,27-254")
      (footprint "eagle-import:SMD1,27-2,54")
      (libsource (lib "eagle-import") (part "WIREPADSMD1,27-254"))
    )
    (comp (ref "PAD254")
      (value "WIREPADSMD1,27-254")
      (footprint "eagle-import:SMD1,27-2,54")
      (libsource (lib "eagle-import") (part "WIREPADSMD1,27-254"))
    )
    (comp (ref "PAD265")
      (value "WIREPADSMD1,27-254")
      (footprint "eagle-import:SMD1,27-2,54")
      (libsource (lib "eagle-import") (part "WIREPADSMD1,27-254"))
    )
    (comp (ref "PAD266")
      (value "WIREPADSMD1,27-254")
      (footprint "eagle-import:SMD1,27-2,54")
      (libsource (lib "eagle-import") (part "WIREPADSMD1,27-254"))
    )
    (comp (ref "PAD267")
      (value "WIREPADSMD1,27-254")
      (footprint "eagle-import:SMD1,27-2,54")
      (libsource (lib "eagle-import") (part "WIREPADSMD1,27-254"))
    )
    (comp (ref "PAD268")
      (value "WIREPADSMD1,27-254")
      (footprint "eagle-import:SMD1,27-2,54")
      (libsource (lib "eagle-import") (part "WIREPADSMD1,27-254"))
    )
    (comp (ref "PAD269")
      (value "WIREPADSMD1,27-254")
      (footprint "eagle-import:SMD1,27-2,54")
      (libsource (lib "eagle-import") (part "WIREPADSMD1,27-254"))
    )
    (comp (ref "PAD270")
      (value "WIREPADSMD1,27-254")
      (footprint "eagle-import:SMD1,27-2,54")
      (libsource (lib "eagle-import") (part "WIREPADSMD1,27-254"))
    )
    (comp (ref "PAD271")
      (value "WIREPADSMD1,27-254")
      (footprint "eagle-import:SMD1,27-2,54")
      (libsource (lib "eagle-import") (part "WIREPADSMD1,27-254"))
    )
    (comp (ref "PAD272")
      (value "WIREPADSMD1,27-254")
      (footprint "eagle-import:SMD1,27-2,54")
      (libsource (lib "eagle-import") (part "WIREPADSMD1,27-254"))
    )
    (comp (ref "PAD273")
      (value "WIREPADSMD1,27-254")
      (footprint "eagle-import:SMD1,27-2,54")
      (libsource (lib "eagle-import") (part "WIREPADSMD1,27-254"))
    )
    (comp (ref "PAD274")
      (value "WIREPADSMD1,27-254")
      (footprint "eagle-import:SMD1,27-2,54")
      (libsource (lib "eagle-import") (part "WIREPADSMD1,27-254"))
    )
    (comp (ref "PAD285")
      (value "WIREPADSMD1,27-254")
      (footprint "eagle-import:SMD1,27-2,54")
      (libsource (lib "eagle-import") (part "WIREPADSMD1,27-254"))
    )
    (comp (ref "PAD286")
      (value "WIREPADSMD1,27-254")
      (footprint "eagle-import:SMD1,27-2,54")
      (libsource (lib "eagle-import") (part "WIREPADSMD1,27-254"))
    )
    (comp (ref "PAD287")
      (value "WIREPADSMD1,27-254")
      (footprint "eagle-import:SMD1,27-2,54")
      (libsource (lib "eagle-import") (part "WIREPADSMD1,27-254"))
    )
    (comp (ref "PAD288")
      (value "WIREPADSMD1,27-254")
      (footprint "eagle-import:SMD1,27-2,54")
      (libsource (lib "eagle-import") (part "WIREPADSMD1,27-254"))
    )
    (comp (ref "PAD289")
      (value "WIREPADSMD1,27-254")
      (footprint "eagle-import:SMD1,27-2,54")
      (libsource (lib "eagle-import") (part "WIREPADSMD1,27-254"))
    )
    (comp (ref "PAD290")
      (value "WIREPADSMD1,27-254")
      (footprint "eagle-import:SMD1,27-2,54")
      (libsource (lib "eagle-import") (part "WIREPADSMD1,27-254"))
    )
    (comp (ref "PAD291")
      (value "WIREPADSMD1,27-254")
      (footprint "eagle-import:SMD1,27-2,54")
      (libsource (lib "eagle-import") (part "WIREPADSMD1,27-254"))
    )
    (comp (ref "PAD292")
      (value "WIREPADSMD1,27-254")
      (footprint "eagle-import:SMD1,27-2,54")
      (libsource (lib "eagle-import") (part "WIREPADSMD1,27-254"))
    )
    (comp (ref "PAD293")
      (value "WIREPADSMD1,27-254")
      (footprint "eagle-import:SMD1,27-2,54")
      (libsource (lib "eagle-import") (part "WIREPADSMD1,27-254"))
    )
    (comp (ref "PAD294")
      (value "WIREPADSMD1,27-254")
      (footprint "eagle-import:SMD1,27-2,54")
      (libsource (lib "eagle-import") (part "WIREPADSMD1,27-254"))
    )
    (comp (ref "PAD305")
      (value "WIREPADSMD1,27-254")
      (footprint "eagle-import:SMD1,27-2,54")
      (libsource (lib "eagle-import") (part "WIREPADSMD1,27-254"))
    )
    (comp (ref "PAD306")
      (value "WIREPADSMD1,27-254")
      (footprint "eagle-import:SMD1,27-2,54")
      (libsource (lib "eagle-import") (part "WIREPADSMD1,27-254"))
    )
    (comp (ref "PAD307")
      (value "WIREPADSMD1,27-254")
      (footprint "eagle-import:SMD1,27-2,54")
      (libsource (lib "eagle-import") (part "WIREPADSMD1,27-254"))
    )
    (comp (ref "PAD308")
      (value "WIREPADSMD1,27-254")
      (footprint "eagle-import:SMD1,27-2,54")
      (libsource (lib "eagle-import") (part "WIREPADSMD1,27-254"))
    )
    (comp (ref "PAD309")
      (value "WIREPADSMD1,27-254")
      (footprint "eagle-import:SMD1,27-2,54")
      (libsource (lib "eagle-import") (part "WIREPADSMD1,27-254"))
    )
    (comp (ref "PAD310")
      (value "WIREPADSMD1,27-254")
      (footprint "eagle-import:SMD1,27-2,54")
      (libsource (lib "eagle-import") (part "WIREPADSMD1,27-254"))
    )
    (comp (ref "PAD311")
      (value "WIREPADSMD1,27-254")
      (footprint "eagle-import:SMD1,27-2,54")
      (libsource (lib "eagle-import") (part "WIREPADSMD1,27-254"))
    )
    (comp (ref "PAD312")
      (value "WIREPADSMD1,27-254")
      (footprint "eagle-import:SMD1,27-2,54")
      (libsource (lib "eagle-import") (part "WIREPADSMD1,27-254"))
    )
    (comp (ref "PAD313")
      (value "WIREPADSMD1,27-254")
      (footprint "eagle-import:SMD1,27-2,54")
      (libsource (lib "eagle-import") (part "WIREPADSMD1,27-254"))
    )
    (comp (ref "PAD314")
      (value "WIREPADSMD1,27-254")
      (footprint "eagle-import:SMD1,27-2,54")
      (libsource (lib "eagle-import") (part "WIREPADSMD1,27-254"))
    )
    (comp (ref "PAD325")
      (value "WIREPADSMD1,27-254")
      (footprint "eagle-import:SMD1,27-2,54")
      (libsource (lib "eagle-import") (part "WIREPADSMD1,27-254"))
    )
    (comp (ref "PAD326")
      (value "WIREPADSMD1,27-254")
      (footprint "eagle-import:SMD1,27-2,54")
      (libsource (lib "eagle-import") (part "WIREPADSMD1,27-254"))
    )
    (comp (ref "PAD327")
      (value "WIREPADSMD1,27-254")
      (footprint "eagle-import:SMD1,27-2,54")
      (libsource (lib "eagle-import") (part "WIREPADSMD1,27-254"))
    )
    (comp (ref "PAD328")
      (value "WIREPADSMD1,27-254")
      (footprint "eagle-import:SMD1,27-2,54")
      (libsource (lib "eagle-import") (part "WIREPADSMD1,27-254"))
    )
    (comp (ref "PAD329")
      (value "WIREPADSMD1,27-254")
      (footprint "eagle-import:SMD1,27-2,54")
      (libsource (lib "eagle-import") (part "WIREPADSMD1,27-254"))
    )
    (comp (ref "PAD330")
      (value "WIREPADSMD1,27-254")
      (footprint "eagle-import:SMD1,27-2,54")
      (libsource (lib "eagle-import") (part "WIREPADSMD1,27-254"))
    )
    (comp (ref "PAD331")
      (value "WIREPADSMD1,27-254")
      (footprint "eagle-import:SMD1,27-2,54")
      (libsource (lib "eagle-import") (part "WIREPADSMD1,27-254"))
    )
    (comp (ref "PAD332")
      (value "WIREPADSMD1,27-254")
      (footprint "eagle-import:SMD1,27-2,54")
      (libsource (lib "eagle-import") (part "WIREPADSMD1,27-254"))
    )
    (comp (ref "PAD333")
      (value "WIREPADSMD1,27-254")
      (footprint "eagle-import:SMD1,27-2,54")
      (libsource (lib "eagle-import") (part "WIREPADSMD1,27-254"))
    )
    (comp (ref "PAD334")
      (value "WIREPADSMD1,27-254")
      (footprint "eagle-import:SMD1,27-2,54")
      (libsource (lib "eagle-import") (part "WIREPADSMD1,27-254"))
    )
    (comp (ref "PAD345")
      (value "WIREPADSMD1,27-254")
      (footprint "eagle-import:SMD1,27-2,54")
      (libsource (lib "eagle-import") (part "WIREPADSMD1,27-254"))
    )
    (comp (ref "PAD346")
      (value "WIREPADSMD1,27-254")
      (footprint "eagle-import:SMD1,27-2,54")
      (libsource (lib "eagle-import") (part "WIREPADSMD1,27-254"))
    )
    (comp (ref "PAD347")
      (value "WIREPADSMD1,27-254")
      (footprint "eagle-import:SMD1,27-2,54")
      (libsource (lib "eagle-import") (part "WIREPADSMD1,27-254"))
    )
    (comp (ref "PAD348")
      (value "WIREPADSMD1,27-254")
      (footprint "eagle-import:SMD1,27-2,54")
      (libsource (lib "eagle-import") (part "WIREPADSMD1,27-254"))
    )
    (comp (ref "PAD349")
      (value "WIREPADSMD1,27-254")
      (footprint "eagle-import:SMD1,27-2,54")
      (libsource (lib "eagle-import") (part "WIREPADSMD1,27-254"))
    )
    (comp (ref "PAD350")
      (value "WIREPADSMD1,27-254")
      (footprint "eagle-import:SMD1,27-2,54")
      (libsource (lib "eagle-import") (part "WIREPADSMD1,27-254"))
    )
    (comp (ref "PAD351")
      (value "WIREPADSMD1,27-254")
      (footprint "eagle-import:SMD1,27-2,54")
      (libsource (lib "eagle-import") (part "WIREPADSMD1,27-254"))
    )
    (comp (ref "PAD352")
      (value "WIREPADSMD1,27-254")
      (footprint "eagle-import:SMD1,27-2,54")
      (libsource (lib "eagle-import") (part "WIREPADSMD1,27-254"))
    )
    (comp (ref "PAD353")
      (value "WIREPADSMD1,27-254")
      (footprint "eagle-import:SMD1,27-2,54")
      (libsource (lib "eagle-import") (part "WIREPADSMD1,27-254"))
    )
    (comp (ref "PAD354")
      (value "WIREPADSMD1,27-254")
      (footprint "eagle-import:SMD1,27-2,54")
      (libsource (lib "eagle-import") (part "WIREPADSMD1,27-254"))
    )
    (comp (ref "R73")
      (value "10k")
      (footprint "eagle-import:R0402")
      (libsource (lib "eagle-import") (part "R-EU_R0402"))
    )
    (comp (ref "R74")
      (value "10k")
      (footprint "eagle-import:R0402")
      (libsource (lib "eagle-import") (part "R-EU_R0402"))
    )
    (comp (ref "R75")
      (value "NOFIT")
      (footprint "eagle-import:R0201")
      (libsource (lib "eagle-import") (part "R-EU_R0201"))
    )
    (comp (ref "R76")
      (value "NOFIT")
      (footprint "eagle-import:R0201")
      (libsource (lib "eagle-import") (part "R-EU_R0201"))
    )
    (comp (ref "R81")
      (value "10k")
      (footprint "eagle-import:R0402")
      (libsource (lib "eagle-import") (part "R-EU_R0402"))
    )
    (comp (ref "R82")
      (value "10k")
      (footprint "eagle-import:R0402")
      (libsource (lib "eagle-import") (part "R-EU_R0402"))
    )
    (comp (ref "R83")
      (value "NOFIT")
      (footprint "eagle-import:R0201")
      (libsource (lib "eagle-import") (part "R-EU_R0201"))
    )
    (comp (ref "R84")
      (value "NOFIT")
      (footprint "eagle-import:R0201")
      (libsource (lib "eagle-import") (part "R-EU_R0201"))
    )
    (comp (ref "R89")
      (value "10k")
      (footprint "eagle-import:R0402")
      (libsource (lib "eagle-import") (part "R-EU_R0402"))
    )
    (comp (ref "R90")
      (value "10k")
      (footprint "eagle-import:R0402")
      (libsource (lib "eagle-import") (part "R-EU_R0402"))
    )
    (comp (ref "R91")
      (value "NOFIT")
      (footprint "eagle-import:R0201")
      (libsource (lib "eagle-import") (part "R-EU_R0201"))
    )
    (comp (ref "R92")
      (value "NOFIT")
      (footprint "eagle-import:R0201")
      (libsource (lib "eagle-import") (part "R-EU_R0201"))
    )
    (comp (ref "R97")
      (value "10k")
      (footprint "eagle-import:R0402")
      (libsource (lib "eagle-import") (part "R-EU_R0402"))
    )
    (comp (ref "R98")
      (value "10k")
      (footprint "eagle-import:R0402")
      (libsource (lib "eagle-import") (part "R-EU_R0402"))
    )
    (comp (ref "R99")
      (value "NOFIT")
      (footprint "eagle-import:R0201")
      (libsource (lib "eagle-import") (part "R-EU_R0201"))
    )
    (comp (ref "R100")
      (value "NOFIT")
      (footprint "eagle-import:R0201")
      (libsource (lib "eagle-import") (part "R-EU_R0201"))
    )
    (comp (ref "R105")
      (value "10k")
      (footprint "eagle-import:R0402")
      (libsource (lib "eagle-import") (part "R-EU_R0402"))
    )
    (comp (ref "R106")
      (value "10k")
      (footprint "eagle-import:R0402")
      (libsource (lib "eagle-import") (part "R-EU_R0402"))
    )
    (comp (ref "R107")
      (value "NOFIT")
      (footprint "eagle-import:R0201")
      (libsource (lib "eagle-import") (part "R-EU_R0201"))
    )
    (comp (ref "R108")
      (value "NOFIT")
      (footprint "eagle-import:R0201")
      (libsource (lib "eagle-import") (part "R-EU_R0201"))
    )
    (comp (ref "R113")
      (value "10k")
      (footprint "eagle-import:R0402")
      (libsource (lib "eagle-import") (part "R-EU_R0402"))
    )
    (comp (ref "R114")
      (value "10k")
      (footprint "eagle-import:R0402")
      (libsource (lib "eagle-import") (part "R-EU_R0402"))
    )
    (comp (ref "R115")
      (value "NOFIT")
      (footprint "eagle-import:R0201")
      (libsource (lib "eagle-import") (part "R-EU_R0201"))
    )
    (comp (ref "R116")
      (value "NOFIT")
      (footprint "eagle-import:R0201")
      (libsource (lib "eagle-import") (part "R-EU_R0201"))
    )
    (comp (ref "R121")
      (value "10k")
      (footprint "eagle-import:R0402")
      (libsource (lib "eagle-import") (part "R-EU_R0402"))
    )
    (comp (ref "R122")
      (value "10k")
      (footprint "eagle-import:R0402")
      (libsource (lib "eagle-import") (part "R-EU_R0402"))
    )
    (comp (ref "R123")
      (value "NOFIT")
      (footprint "eagle-import:R0201")
      (libsource (lib "eagle-import") (part "R-EU_R0201"))
    )
    (comp (ref "R124")
      (value "NOFIT")
      (footprint "eagle-import:R0201")
      (libsource (lib "eagle-import") (part "R-EU_R0201"))
    )
    (comp (ref "R129")
      (value "10k")
      (footprint "eagle-import:R0402")
      (libsource (lib "eagle-import") (part "R-EU_R0402"))
    )
    (comp (ref "R130")
      (value "10k")
      (footprint "eagle-import:R0402")
      (libsource (lib "eagle-import") (part "R-EU_R0402"))
    )
    (comp (ref "R131")
      (value "NOFIT")
      (footprint "eagle-import:R0201")
      (libsource (lib "eagle-import") (part "R-EU_R0201"))
    )
    (comp (ref "R132")
      (value "NOFIT")
      (footprint "eagle-import:R0201")
      (libsource (lib "eagle-import") (part "R-EU_R0201"))
    )
    (comp (ref "R137")
      (value "10k")
      (footprint "eagle-import:R0402")
      (libsource (lib "eagle-import") (part "R-EU_R0402"))
    )
    (comp (ref "R138")
      (value "10k")
      (footprint "eagle-import:R0402")
      (libsource (lib "eagle-import") (part "R-EU_R0402"))
    )
    (comp (ref "R139")
      (value "NOFIT")
      (footprint "eagle-import:R0201")
      (libsource (lib "eagle-import") (part "R-EU_R0201"))
    )
    (comp (ref "R140")
      (value "NOFIT")
      (footprint "eagle-import:R0201")
      (libsource (lib "eagle-import") (part "R-EU_R0201"))
    )
    (comp (ref "R145")
      (value "10k")
      (footprint "eagle-import:R0402")
      (libsource (lib "eagle-import") (part "R-EU_R0402"))
    )
    (comp (ref "R146")
      (value "10k")
      (footprint "eagle-import:R0402")
      (libsource (lib "eagle-import") (part "R-EU_R0402"))
    )
    (comp (ref "R147")
      (value "NOFIT")
      (footprint "eagle-import:R0201")
      (libsource (lib "eagle-import") (part "R-EU_R0201"))
    )
    (comp (ref "R148")
      (value "NOFIT")
      (footprint "eagle-import:R0201")
      (libsource (lib "eagle-import") (part "R-EU_R0201"))
    )
    (comp (ref "U$19")
      (value "FATFAN_GROUP")
      (footprint "eagle-import:FAT_FAN")
      (libsource (lib "eagle-import") (part "FATFAN_GROUP"))
    )
    (comp (ref "U$21")
      (value "FATFAN_GROUP")
      (footprint "eagle-import:FAT_FAN")
      (libsource (lib "eagle-import") (part "FATFAN_GROUP"))
    )
    (comp (ref "U$23")
      (value "FATFAN_GROUP")
      (footprint "eagle-import:FAT_FAN")
      (libsource (lib "eagle-import") (part "FATFAN_GROUP"))
    )
    (comp (ref "U$25")
      (value "FATFAN_GROUP")
      (footprint "eagle-import:FAT_FAN")
      (libsource (lib "eagle-import") (part "FATFAN_GROUP"))
    )
    (comp (ref "U$27")
      (value "FATFAN_GROUP")
      (footprint "eagle-import:FAT_FAN")
      (libsource (lib "eagle-import") (part "FATFAN_GROUP"))
    )
    (comp (ref "U$29")
      (value "FATFAN_GROUP")
      (footprint "eagle-import:FAT_FAN")
      (libsource (lib "eagle-import") (part "FATFAN_GROUP"))
    )
    (comp (ref "U$31")
      (value "FATFAN_GROUP")
      (footprint "eagle-import:FAT_FAN")
      (libsource (lib "eagle-import") (part "FATFAN_GROUP"))
    )
    (comp (ref "U$33")
      (value "FATFAN_GROUP")
      (footprint "eagle-import:FAT_FAN")
      (libsource (lib "eagle-import") (part "FATFAN_GROUP"))
    )
    (comp (ref "U$35")
      (value "FATFAN_GROUP")
      (footprint "eagle-import:FAT_FAN")
      (libsource (lib "eagle-import") (part "FATFAN_GROUP"))
    )
    (comp (ref "U$37")
      (value "FATFAN_GROUP")
      (footprint "eagle-import:FAT_FAN")
      (libsource (lib "eagle-import") (part "FATFAN_GROUP"))
    )
    (comp (ref "U19")
      (value "LDC1614")
      (footprint "eagle-import:WQFN-16")
      (libsource (lib "eagle-import") (part "LDC1614"))
    )
    (comp (ref "U21")
      (value "LDC1614")
      (footprint "eagle-import:WQFN-16")
      (libsource (lib "eagle-import") (part "LDC1614"))
    )
    (comp (ref "U23")
      (value "LDC1614")
      (footprint "eagle-import:WQFN-16")
      (libsource (lib "eagle-import") (part "LDC1614"))
    )
    (comp (ref "U25")
      (value "LDC1614")
      (footprint "eagle-import:WQFN-16")
      (libsource (lib "eagle-import") (part "LDC1614"))
    )
    (comp (ref "U27")
      (value "LDC1614")
      (footprint "eagle-import:WQFN-16")
      (libsource (lib "eagle-import") (part "LDC1614"))
    )
    (comp (ref "U29")
      (value "LDC1614")
      (footprint "eagle-import:WQFN-16")
      (libsource (lib "eagle-import") (part "LDC1614"))
    )
    (comp (ref "U31")
      (value "LDC1614")
      (footprint "eagle-import:WQFN-16")
      (libsource (lib "eagle-import") (part "LDC1614"))
    )
    (comp (ref "U33")
      (value "LDC1614")
      (footprint "eagle-import:WQFN-16")
      (libsource (lib "eagle-import") (part "LDC1614"))
    )
    (comp (ref "U35")
      (value "LDC1614")
      (footprint "eagle-import:WQFN-16")
      (libsource (lib "eagle-import") (part "LDC1614"))
    )
    (comp (ref "U37")
      (value "LDC1614")
      (footprint "eagle-import:WQFN-16")
      (libsource (lib "eagle-import") (part "LDC1614"))
    )
    (comp (ref "C2")
      (value "10uF")
      (footprint "eagle-import:C0402")
      (libsource (lib "eagle-import") (part "C-EUC0402"))
    )
    (comp (ref "C4")
      (value "10uF")
      (footprint "eagle-import:C0402")
      (libsource (lib "eagle-import") (part "C-EUC0402"))
    )
    (comp (ref "C5")
      (value "10uF")
      (footprint "eagle-import:C0402")
      (libsource (lib "eagle-import") (part "C-EUC0402"))
    )
    (comp (ref "C6")
      (value "10uF")
      (footprint "eagle-import:C0402")
      (libsource (lib "eagle-import") (part "C-EUC0402"))
    )
    (comp (ref "C8")
      (value "10uF")
      (footprint "eagle-import:C0402")
      (libsource (lib "eagle-import") (part "C-EUC0402"))
    )
    (comp (ref "C9")
      (value "10uF")
      (footprint "eagle-import:C0402")
      (libsource (lib "eagle-import") (part "C-EUC0402"))
    )
    (comp (ref "C10")
      (value "10uF")
      (footprint "eagle-import:C0402")
      (libsource (lib "eagle-import") (part "C-EUC0402"))
    )
    (comp (ref "C12")
      (value "10uF")
      (footprint "eagle-import:C0402")
      (libsource (lib "eagle-import") (part "C-EUC0402"))
    )
    (comp (ref "C14")
      (value "10uF")
      (footprint "eagle-import:C0402")
      (libsource (lib "eagle-import") (part "C-EUC0402"))
    )
    (comp (ref "C16")
      (value "10uF")
      (footprint "eagle-import:C0402")
      (libsource (lib "eagle-import") (part "C-EUC0402"))
    )
    (comp (ref "PAD8")
      (value "WIREPADSMD1,27-254")
      (footprint "eagle-import:SMD1,27-2,54")
      (libsource (lib "eagle-import") (part "WIREPADSMD1,27-254"))
    )
    (comp (ref "PAD11")
      (value "WIREPADSMD1,27-254")
      (footprint "eagle-import:SMD1,27-2,54")
      (libsource (lib "eagle-import") (part "WIREPADSMD1,27-254"))
    )
    (comp (ref "PAD12")
      (value "WIREPADSMD1,27-254")
      (footprint "eagle-import:SMD1,27-2,54")
      (libsource (lib "eagle-import") (part "WIREPADSMD1,27-254"))
    )
    (comp (ref "PAD13")
      (value "WIREPADSMD1,27-254")
      (footprint "eagle-import:SMD1,27-2,54")
      (libsource (lib "eagle-import") (part "WIREPADSMD1,27-254"))
    )
    (comp (ref "PAD14")
      (value "WIREPADSMD1,27-254")
      (footprint "eagle-import:SMD1,27-2,54")
      (libsource (lib "eagle-import") (part "WIREPADSMD1,27-254"))
    )
    (comp (ref "PAD15")
      (value "WIREPADSMD1,27-254")
      (footprint "eagle-import:SMD1,27-2,54")
      (libsource (lib "eagle-import") (part "WIREPADSMD1,27-254"))
    )
    (comp (ref "PAD16")
      (value "WIREPADSMD1,27-254")
      (footprint "eagle-import:SMD1,27-2,54")
      (libsource (lib "eagle-import") (part "WIREPADSMD1,27-254"))
    )
    (comp (ref "PAD17")
      (value "WIREPADSMD1,27-254")
      (footprint "eagle-import:SMD1,27-2,54")
      (libsource (lib "eagle-import") (part "WIREPADSMD1,27-254"))
    )
    (comp (ref "PAD18")
      (value "WIREPADSMD1,27-254")
      (footprint "eagle-import:SMD1,27-2,54")
      (libsource (lib "eagle-import") (part "WIREPADSMD1,27-254"))
    )
    (comp (ref "PAD28")
      (value "WIREPADSMD1,27-254")
      (footprint "eagle-import:SMD1,27-2,54")
      (libsource (lib "eagle-import") (part "WIREPADSMD1,27-254"))
    )
    (comp (ref "PAD29")
      (value "WIREPADSMD1,27-254")
      (footprint "eagle-import:SMD1,27-2,54")
      (libsource (lib "eagle-import") (part "WIREPADSMD1,27-254"))
    )
    (comp (ref "PAD30")
      (value "WIREPADSMD1,27-254")
      (footprint "eagle-import:SMD1,27-2,54")
      (libsource (lib "eagle-import") (part "WIREPADSMD1,27-254"))
    )
    (comp (ref "PAD31")
      (value "WIREPADSMD1,27-254")
      (footprint "eagle-import:SMD1,27-2,54")
      (libsource (lib "eagle-import") (part "WIREPADSMD1,27-254"))
    )
    (comp (ref "PAD32")
      (value "WIREPADSMD1,27-254")
      (footprint "eagle-import:SMD1,27-2,54")
      (libsource (lib "eagle-import") (part "WIREPADSMD1,27-254"))
    )
    (comp (ref "PAD33")
      (value "WIREPADSMD1,27-254")
      (footprint "eagle-import:SMD1,27-2,54")
      (libsource (lib "eagle-import") (part "WIREPADSMD1,27-254"))
    )
    (comp (ref "PAD34")
      (value "WIREPADSMD1,27-254")
      (footprint "eagle-import:SMD1,27-2,54")
      (libsource (lib "eagle-import") (part "WIREPADSMD1,27-254"))
    )
    (comp (ref "PAD35")
      (value "WIREPADSMD1,27-254")
      (footprint "eagle-import:SMD1,27-2,54")
      (libsource (lib "eagle-import") (part "WIREPADSMD1,27-254"))
    )
    (comp (ref "PAD36")
      (value "WIREPADSMD1,27-254")
      (footprint "eagle-import:SMD1,27-2,54")
      (libsource (lib "eagle-import") (part "WIREPADSMD1,27-254"))
    )
    (comp (ref "PAD37")
      (value "WIREPADSMD1,27-254")
      (footprint "eagle-import:SMD1,27-2,54")
      (libsource (lib "eagle-import") (part "WIREPADSMD1,27-254"))
    )
    (comp (ref "PAD38")
      (value "WIREPADSMD1,27-254")
      (footprint "eagle-import:SMD1,27-2,54")
      (libsource (lib "eagle-import") (part "WIREPADSMD1,27-254"))
    )
    (comp (ref "PAD39")
      (value "WIREPADSMD1,27-254")
      (footprint "eagle-import:SMD1,27-2,54")
      (libsource (lib "eagle-import") (part "WIREPADSMD1,27-254"))
    )
    (comp (ref "PAD40")
      (value "WIREPADSMD1,27-254")
      (footprint "eagle-import:SMD1,27-2,54")
      (libsource (lib "eagle-import") (part "WIREPADSMD1,27-254"))
    )
    (comp (ref "PAD41")
      (value "WIREPADSMD1,27-254")
      (footprint "eagle-import:SMD1,27-2,54")
      (libsource (lib "eagle-import") (part "WIREPADSMD1,27-254"))
    )
    (comp (ref "PAD42")
      (value "WIREPADSMD1,27-254")
      (footprint "eagle-import:SMD1,27-2,54")
      (libsource (lib "eagle-import") (part "WIREPADSMD1,27-254"))
    )
    (comp (ref "PAD43")
      (value "WIREPADSMD1,27-254")
      (footprint "eagle-import:SMD1,27-2,54")
      (libsource (lib "eagle-import") (part "WIREPADSMD1,27-254"))
    )
    (comp (ref "PAD44")
      (value "WIREPADSMD1,27-254")
      (footprint "eagle-import:SMD1,27-2,54")
      (libsource (lib "eagle-import") (part "WIREPADSMD1,27-254"))
    )
    (comp (ref "PAD45")
      (value "WIREPADSMD1,27-254")
      (footprint "eagle-import:SMD1,27-2,54")
      (libsource (lib "eagle-import") (part "WIREPADSMD1,27-254"))
    )
    (comp (ref "PAD46")
      (value "WIREPADSMD1,27-254")
      (footprint "eagle-import:SMD1,27-2,54")
      (libsource (lib "eagle-import") (part "WIREPADSMD1,27-254"))
    )
    (comp (ref "PAD47")
      (value "WIREPADSMD1,27-254")
      (footprint "eagle-import:SMD1,27-2,54")
      (libsource (lib "eagle-import") (part "WIREPADSMD1,27-254"))
    )
    (comp (ref "PAD48")
      (value "WIREPADSMD1,27-254")
      (footprint "eagle-import:SMD1,27-2,54")
      (libsource (lib "eagle-import") (part "WIREPADSMD1,27-254"))
    )
    (comp (ref "PAD49")
      (value "WIREPADSMD1,27-254")
      (footprint "eagle-import:SMD1,27-2,54")
      (libsource (lib "eagle-import") (part "WIREPADSMD1,27-254"))
    )
    (comp (ref "PAD50")
      (value "WIREPADSMD1,27-254")
      (footprint "eagle-import:SMD1,27-2,54")
      (libsource (lib "eagle-import") (part "WIREPADSMD1,27-254"))
    )
    (comp (ref "PAD51")
      (value "WIREPADSMD1,27-254")
      (footprint "eagle-import:SMD1,27-2,54")
      (libsource (lib "eagle-import") (part "WIREPADSMD1,27-254"))
    )
    (comp (ref "PAD52")
      (value "WIREPADSMD1,27-254")
      (footprint "eagle-import:SMD1,27-2,54")
      (libsource (lib "eagle-import") (part "WIREPADSMD1,27-254"))
    )
    (comp (ref "PAD53")
      (value "WIREPADSMD1,27-254")
      (footprint "eagle-import:SMD1,27-2,54")
      (libsource (lib "eagle-import") (part "WIREPADSMD1,27-254"))
    )
    (comp (ref "PAD54")
      (value "WIREPADSMD1,27-254")
      (footprint "eagle-import:SMD1,27-2,54")
      (libsource (lib "eagle-import") (part "WIREPADSMD1,27-254"))
    )
    (comp (ref "PAD64")
      (value "WIREPADSMD1,27-254")
      (footprint "eagle-import:SMD1,27-2,54")
      (libsource (lib "eagle-import") (part "WIREPADSMD1,27-254"))
    )
    (comp (ref "PAD65")
      (value "WIREPADSMD1,27-254")
      (footprint "eagle-import:SMD1,27-2,54")
      (libsource (lib "eagle-import") (part "WIREPADSMD1,27-254"))
    )
    (comp (ref "PAD66")
      (value "WIREPADSMD1,27-254")
      (footprint "eagle-import:SMD1,27-2,54")
      (libsource (lib "eagle-import") (part "WIREPADSMD1,27-254"))
    )
    (comp (ref "PAD67")
      (value "WIREPADSMD1,27-254")
      (footprint "eagle-import:SMD1,27-2,54")
      (libsource (lib "eagle-import") (part "WIREPADSMD1,27-254"))
    )
    (comp (ref "PAD68")
      (value "WIREPADSMD1,27-254")
      (footprint "eagle-import:SMD1,27-2,54")
      (libsource (lib "eagle-import") (part "WIREPADSMD1,27-254"))
    )
    (comp (ref "PAD69")
      (value "WIREPADSMD1,27-254")
      (footprint "eagle-import:SMD1,27-2,54")
      (libsource (lib "eagle-import") (part "WIREPADSMD1,27-254"))
    )
    (comp (ref "PAD70")
      (value "WIREPADSMD1,27-254")
      (footprint "eagle-import:SMD1,27-2,54")
      (libsource (lib "eagle-import") (part "WIREPADSMD1,27-254"))
    )
    (comp (ref "PAD71")
      (value "WIREPADSMD1,27-254")
      (footprint "eagle-import:SMD1,27-2,54")
      (libsource (lib "eagle-import") (part "WIREPADSMD1,27-254"))
    )
    (comp (ref "PAD72")
      (value "WIREPADSMD1,27-254")
      (footprint "eagle-import:SMD1,27-2,54")
      (libsource (lib "eagle-import") (part "WIREPADSMD1,27-254"))
    )
    (comp (ref "PAD73")
      (value "WIREPADSMD1,27-254")
      (footprint "eagle-import:SMD1,27-2,54")
      (libsource (lib "eagle-import") (part "WIREPADSMD1,27-254"))
    )
    (comp (ref "PAD74")
      (value "WIREPADSMD1,27-254")
      (footprint "eagle-import:SMD1,27-2,54")
      (libsource (lib "eagle-import") (part "WIREPADSMD1,27-254"))
    )
    (comp (ref "PAD75")
      (value "WIREPADSMD1,27-254")
      (footprint "eagle-import:SMD1,27-2,54")
      (libsource (lib "eagle-import") (part "WIREPADSMD1,27-254"))
    )
    (comp (ref "PAD76")
      (value "WIREPADSMD1,27-254")
      (footprint "eagle-import:SMD1,27-2,54")
      (libsource (lib "eagle-import") (part "WIREPADSMD1,27-254"))
    )
    (comp (ref "PAD77")
      (value "WIREPADSMD1,27-254")
      (footprint "eagle-import:SMD1,27-2,54")
      (libsource (lib "eagle-import") (part "WIREPADSMD1,27-254"))
    )
    (comp (ref "PAD78")
      (value "WIREPADSMD1,27-254")
      (footprint "eagle-import:SMD1,27-2,54")
      (libsource (lib "eagle-import") (part "WIREPADSMD1,27-254"))
    )
    (comp (ref "PAD79")
      (value "WIREPADSMD1,27-254")
      (footprint "eagle-import:SMD1,27-2,54")
      (libsource (lib "eagle-import") (part "WIREPADSMD1,27-254"))
    )
    (comp (ref "PAD80")
      (value "WIREPADSMD1,27-254")
      (footprint "eagle-import:SMD1,27-2,54")
      (libsource (lib "eagle-import") (part "WIREPADSMD1,27-254"))
    )
    (comp (ref "PAD81")
      (value "WIREPADSMD1,27-254")
      (footprint "eagle-import:SMD1,27-2,54")
      (libsource (lib "eagle-import") (part "WIREPADSMD1,27-254"))
    )
    (comp (ref "PAD82")
      (value "WIREPADSMD1,27-254")
      (footprint "eagle-import:SMD1,27-2,54")
      (libsource (lib "eagle-import") (part "WIREPADSMD1,27-254"))
    )
    (comp (ref "PAD83")
      (value "WIREPADSMD1,27-254")
      (footprint "eagle-import:SMD1,27-2,54")
      (libsource (lib "eagle-import") (part "WIREPADSMD1,27-254"))
    )
    (comp (ref "PAD84")
      (value "WIREPADSMD1,27-254")
      (footprint "eagle-import:SMD1,27-2,54")
      (libsource (lib "eagle-import") (part "WIREPADSMD1,27-254"))
    )
    (comp (ref "PAD85")
      (value "WIREPADSMD1,27-254")
      (footprint "eagle-import:SMD1,27-2,54")
      (libsource (lib "eagle-import") (part "WIREPADSMD1,27-254"))
    )
    (comp (ref "PAD86")
      (value "WIREPADSMD1,27-254")
      (footprint "eagle-import:SMD1,27-2,54")
      (libsource (lib "eagle-import") (part "WIREPADSMD1,27-254"))
    )
    (comp (ref "PAD87")
      (value "WIREPADSMD1,27-254")
      (footprint "eagle-import:SMD1,27-2,54")
      (libsource (lib "eagle-import") (part "WIREPADSMD1,27-254"))
    )
    (comp (ref "PAD88")
      (value "WIREPADSMD1,27-254")
      (footprint "eagle-import:SMD1,27-2,54")
      (libsource (lib "eagle-import") (part "WIREPADSMD1,27-254"))
    )
    (comp (ref "PAD89")
      (value "WIREPADSMD1,27-254")
      (footprint "eagle-import:SMD1,27-2,54")
      (libsource (lib "eagle-import") (part "WIREPADSMD1,27-254"))
    )
    (comp (ref "PAD90")
      (value "WIREPADSMD1,27-254")
      (footprint "eagle-import:SMD1,27-2,54")
      (libsource (lib "eagle-import") (part "WIREPADSMD1,27-254"))
    )
    (comp (ref "PAD100")
      (value "WIREPADSMD1,27-254")
      (footprint "eagle-import:SMD1,27-2,54")
      (libsource (lib "eagle-import") (part "WIREPADSMD1,27-254"))
    )
    (comp (ref "PAD101")
      (value "WIREPADSMD1,27-254")
      (footprint "eagle-import:SMD1,27-2,54")
      (libsource (lib "eagle-import") (part "WIREPADSMD1,27-254"))
    )
    (comp (ref "PAD102")
      (value "WIREPADSMD1,27-254")
      (footprint "eagle-import:SMD1,27-2,54")
      (libsource (lib "eagle-import") (part "WIREPADSMD1,27-254"))
    )
    (comp (ref "PAD103")
      (value "WIREPADSMD1,27-254")
      (footprint "eagle-import:SMD1,27-2,54")
      (libsource (lib "eagle-import") (part "WIREPADSMD1,27-254"))
    )
    (comp (ref "PAD104")
      (value "WIREPADSMD1,27-254")
      (footprint "eagle-import:SMD1,27-2,54")
      (libsource (lib "eagle-import") (part "WIREPADSMD1,27-254"))
    )
    (comp (ref "PAD105")
      (value "WIREPADSMD1,27-254")
      (footprint "eagle-import:SMD1,27-2,54")
      (libsource (lib "eagle-import") (part "WIREPADSMD1,27-254"))
    )
    (comp (ref "PAD106")
      (value "WIREPADSMD1,27-254")
      (footprint "eagle-import:SMD1,27-2,54")
      (libsource (lib "eagle-import") (part "WIREPADSMD1,27-254"))
    )
    (comp (ref "PAD107")
      (value "WIREPADSMD1,27-254")
      (footprint "eagle-import:SMD1,27-2,54")
      (libsource (lib "eagle-import") (part "WIREPADSMD1,27-254"))
    )
    (comp (ref "PAD108")
      (value "WIREPADSMD1,27-254")
      (footprint "eagle-import:SMD1,27-2,54")
      (libsource (lib "eagle-import") (part "WIREPADSMD1,27-254"))
    )
    (comp (ref "PAD118")
      (value "WIREPADSMD1,27-254")
      (footprint "eagle-import:SMD1,27-2,54")
      (libsource (lib "eagle-import") (part "WIREPADSMD1,27-254"))
    )
    (comp (ref "PAD119")
      (value "WIREPADSMD1,27-254")
      (footprint "eagle-import:SMD1,27-2,54")
      (libsource (lib "eagle-import") (part "WIREPADSMD1,27-254"))
    )
    (comp (ref "PAD120")
      (value "WIREPADSMD1,27-254")
      (footprint "eagle-import:SMD1,27-2,54")
      (libsource (lib "eagle-import") (part "WIREPADSMD1,27-254"))
    )
    (comp (ref "PAD121")
      (value "WIREPADSMD1,27-254")
      (footprint "eagle-import:SMD1,27-2,54")
      (libsource (lib "eagle-import") (part "WIREPADSMD1,27-254"))
    )
    (comp (ref "PAD122")
      (value "WIREPADSMD1,27-254")
      (footprint "eagle-import:SMD1,27-2,54")
      (libsource (lib "eagle-import") (part "WIREPADSMD1,27-254"))
    )
    (comp (ref "PAD123")
      (value "WIREPADSMD1,27-254")
      (footprint "eagle-import:SMD1,27-2,54")
      (libsource (lib "eagle-import") (part "WIREPADSMD1,27-254"))
    )
    (comp (ref "PAD124")
      (value "WIREPADSMD1,27-254")
      (footprint "eagle-import:SMD1,27-2,54")
      (libsource (lib "eagle-import") (part "WIREPADSMD1,27-254"))
    )
    (comp (ref "PAD125")
      (value "WIREPADSMD1,27-254")
      (footprint "eagle-import:SMD1,27-2,54")
      (libsource (lib "eagle-import") (part "WIREPADSMD1,27-254"))
    )
    (comp (ref "PAD126")
      (value "WIREPADSMD1,27-254")
      (footprint "eagle-import:SMD1,27-2,54")
      (libsource (lib "eagle-import") (part "WIREPADSMD1,27-254"))
    )
    (comp (ref "PAD136")
      (value "WIREPADSMD1,27-254")
      (footprint "eagle-import:SMD1,27-2,54")
      (libsource (lib "eagle-import") (part "WIREPADSMD1,27-254"))
    )
    (comp (ref "PAD137")
      (value "WIREPADSMD1,27-254")
      (footprint "eagle-import:SMD1,27-2,54")
      (libsource (lib "eagle-import") (part "WIREPADSMD1,27-254"))
    )
    (comp (ref "PAD138")
      (value "WIREPADSMD1,27-254")
      (footprint "eagle-import:SMD1,27-2,54")
      (libsource (lib "eagle-import") (part "WIREPADSMD1,27-254"))
    )
    (comp (ref "PAD139")
      (value "WIREPADSMD1,27-254")
      (footprint "eagle-import:SMD1,27-2,54")
      (libsource (lib "eagle-import") (part "WIREPADSMD1,27-254"))
    )
    (comp (ref "PAD140")
      (value "WIREPADSMD1,27-254")
      (footprint "eagle-import:SMD1,27-2,54")
      (libsource (lib "eagle-import") (part "WIREPADSMD1,27-254"))
    )
    (comp (ref "PAD141")
      (value "WIREPADSMD1,27-254")
      (footprint "eagle-import:SMD1,27-2,54")
      (libsource (lib "eagle-import") (part "WIREPADSMD1,27-254"))
    )
    (comp (ref "PAD142")
      (value "WIREPADSMD1,27-254")
      (footprint "eagle-import:SMD1,27-2,54")
      (libsource (lib "eagle-import") (part "WIREPADSMD1,27-254"))
    )
    (comp (ref "PAD143")
      (value "WIREPADSMD1,27-254")
      (footprint "eagle-import:SMD1,27-2,54")
      (libsource (lib "eagle-import") (part "WIREPADSMD1,27-254"))
    )
    (comp (ref "PAD144")
      (value "WIREPADSMD1,27-254")
      (footprint "eagle-import:SMD1,27-2,54")
      (libsource (lib "eagle-import") (part "WIREPADSMD1,27-254"))
    )
    (comp (ref "R5")
      (value "10k")
      (footprint "eagle-import:R0402")
      (libsource (lib "eagle-import") (part "R-EU_R0402"))
    )
    (comp (ref "R6")
      (value "10k")
      (footprint "eagle-import:R0402")
      (libsource (lib "eagle-import") (part "R-EU_R0402"))
    )
    (comp (ref "R7")
      (value "NOFIT")
      (footprint "eagle-import:R0201")
      (libsource (lib "eagle-import") (part "R-EU_R0201"))
    )
    (comp (ref "R8")
      (value "NOFIT")
      (footprint "eagle-import:R0201")
      (libsource (lib "eagle-import") (part "R-EU_R0201"))
    )
    (comp (ref "R13")
      (value "10k")
      (footprint "eagle-import:R0402")
      (libsource (lib "eagle-import") (part "R-EU_R0402"))
    )
    (comp (ref "R14")
      (value "10k")
      (footprint "eagle-import:R0402")
      (libsource (lib "eagle-import") (part "R-EU_R0402"))
    )
    (comp (ref "R15")
      (value "NOFIT")
      (footprint "eagle-import:R0201")
      (libsource (lib "eagle-import") (part "R-EU_R0201"))
    )
    (comp (ref "R16")
      (value "NOFIT")
      (footprint "eagle-import:R0201")
      (libsource (lib "eagle-import") (part "R-EU_R0201"))
    )
    (comp (ref "R17")
      (value "10k")
      (footprint "eagle-import:R0402")
      (libsource (lib "eagle-import") (part "R-EU_R0402"))
    )
    (comp (ref "R18")
      (value "10k")
      (footprint "eagle-import:R0402")
      (libsource (lib "eagle-import") (part "R-EU_R0402"))
    )
    (comp (ref "R19")
      (value "NOFIT")
      (footprint "eagle-import:R0201")
      (libsource (lib "eagle-import") (part "R-EU_R0201"))
    )
    (comp (ref "R20")
      (value "NOFIT")
      (footprint "eagle-import:R0201")
      (libsource (lib "eagle-import") (part "R-EU_R0201"))
    )
    (comp (ref "R21")
      (value "10k")
      (footprint "eagle-import:R0402")
      (libsource (lib "eagle-import") (part "R-EU_R0402"))
    )
    (comp (ref "R22")
      (value "10k")
      (footprint "eagle-import:R0402")
      (libsource (lib "eagle-import") (part "R-EU_R0402"))
    )
    (comp (ref "R23")
      (value "NOFIT")
      (footprint "eagle-import:R0201")
      (libsource (lib "eagle-import") (part "R-EU_R0201"))
    )
    (comp (ref "R24")
      (value "NOFIT")
      (footprint "eagle-import:R0201")
      (libsource (lib "eagle-import") (part "R-EU_R0201"))
    )
    (comp (ref "R29")
      (value "10k")
      (footprint "eagle-import:R0402")
      (libsource (lib "eagle-import") (part "R-EU_R0402"))
    )
    (comp (ref "R30")
      (value "10k")
      (footprint "eagle-import:R0402")
      (libsource (lib "eagle-import") (part "R-EU_R0402"))
    )
    (comp (ref "R31")
      (value "NOFIT")
      (footprint "eagle-import:R0201")
      (libsource (lib "eagle-import") (part "R-EU_R0201"))
    )
    (comp (ref "R32")
      (value "NOFIT")
      (footprint "eagle-import:R0201")
      (libsource (lib "eagle-import") (part "R-EU_R0201"))
    )
    (comp (ref "R33")
      (value "10k")
      (footprint "eagle-import:R0402")
      (libsource (lib "eagle-import") (part "R-EU_R0402"))
    )
    (comp (ref "R34")
      (value "10k")
      (footprint "eagle-import:R0402")
      (libsource (lib "eagle-import") (part "R-EU_R0402"))
    )
    (comp (ref "R35")
      (value "NOFIT")
      (footprint "eagle-import:R0201")
      (libsource (lib "eagle-import") (part "R-EU_R0201"))
    )
    (comp (ref "R36")
      (value "NOFIT")
      (footprint "eagle-import:R0201")
      (libsource (lib "eagle-import") (part "R-EU_R0201"))
    )
    (comp (ref "R37")
      (value "10k")
      (footprint "eagle-import:R0402")
      (libsource (lib "eagle-import") (part "R-EU_R0402"))
    )
    (comp (ref "R38")
      (value "10k")
      (footprint "eagle-import:R0402")
      (libsource (lib "eagle-import") (part "R-EU_R0402"))
    )
    (comp (ref "R39")
      (value "NOFIT")
      (footprint "eagle-import:R0201")
      (libsource (lib "eagle-import") (part "R-EU_R0201"))
    )
    (comp (ref "R40")
      (value "NOFIT")
      (footprint "eagle-import:R0201")
      (libsource (lib "eagle-import") (part "R-EU_R0201"))
    )
    (comp (ref "R45")
      (value "10k")
      (footprint "eagle-import:R0402")
      (libsource (lib "eagle-import") (part "R-EU_R0402"))
    )
    (comp (ref "R46")
      (value "10k")
      (footprint "eagle-import:R0402")
      (libsource (lib "eagle-import") (part "R-EU_R0402"))
    )
    (comp (ref "R47")
      (value "NOFIT")
      (footprint "eagle-import:R0201")
      (libsource (lib "eagle-import") (part "R-EU_R0201"))
    )
    (comp (ref "R48")
      (value "NOFIT")
      (footprint "eagle-import:R0201")
      (libsource (lib "eagle-import") (part "R-EU_R0201"))
    )
    (comp (ref "R53")
      (value "10k")
      (footprint "eagle-import:R0402")
      (libsource (lib "eagle-import") (part "R-EU_R0402"))
    )
    (comp (ref "R54")
      (value "10k")
      (footprint "eagle-import:R0402")
      (libsource (lib "eagle-import") (part "R-EU_R0402"))
    )
    (comp (ref "R55")
      (value "NOFIT")
      (footprint "eagle-import:R0201")
      (libsource (lib "eagle-import") (part "R-EU_R0201"))
    )
    (comp (ref "R56")
      (value "NOFIT")
      (footprint "eagle-import:R0201")
      (libsource (lib "eagle-import") (part "R-EU_R0201"))
    )
    (comp (ref "R61")
      (value "10k")
      (footprint "eagle-import:R0402")
      (libsource (lib "eagle-import") (part "R-EU_R0402"))
    )
    (comp (ref "R62")
      (value "10k")
      (footprint "eagle-import:R0402")
      (libsource (lib "eagle-import") (part "R-EU_R0402"))
    )
    (comp (ref "R63")
      (value "NOFIT")
      (footprint "eagle-import:R0201")
      (libsource (lib "eagle-import") (part "R-EU_R0201"))
    )
    (comp (ref "R64")
      (value "NOFIT")
      (footprint "eagle-import:R0201")
      (libsource (lib "eagle-import") (part "R-EU_R0201"))
    )
    (comp (ref "U$1")
      (value "FATSQUARE_GROUP")
      (footprint "eagle-import:FAT_SQUARE")
      (libsource (lib "eagle-import") (part "FATSQUARE_GROUP"))
    )
    (comp (ref "U$4")
      (value "FATSQUARE_GROUP")
      (footprint "eagle-import:FAT_SQUARE")
      (libsource (lib "eagle-import") (part "FATSQUARE_GROUP"))
    )
    (comp (ref "U$5")
      (value "FATSQUARE_GROUP")
      (footprint "eagle-import:FAT_SQUARE")
      (libsource (lib "eagle-import") (part "FATSQUARE_GROUP"))
    )
    (comp (ref "U$6")
      (value "FATSQUARE_GROUP")
      (footprint "eagle-import:FAT_SQUARE")
      (libsource (lib "eagle-import") (part "FATSQUARE_GROUP"))
    )
    (comp (ref "U$8")
      (value "FATSQUARE_GROUP")
      (footprint "eagle-import:FAT_SQUARE")
      (libsource (lib "eagle-import") (part "FATSQUARE_GROUP"))
    )
    (comp (ref "U$9")
      (value "FATSQUARE_GROUP")
      (footprint "eagle-import:FAT_SQUARE")
      (libsource (lib "eagle-import") (part "FATSQUARE_GROUP"))
    )
    (comp (ref "U$10")
      (value "FATSQUARE_GROUP")
      (footprint "eagle-import:FAT_SQUARE")
      (libsource (lib "eagle-import") (part "FATSQUARE_GROUP"))
    )
    (comp (ref "U$12")
      (value "FATSQUARE_GROUP")
      (footprint "eagle-import:FAT_SQUARE")
      (libsource (lib "eagle-import") (part "FATSQUARE_GROUP"))
    )
    (comp (ref "U$14")
      (value "FATSQUARE_GROUP")
      (footprint "eagle-import:FAT_SQUARE")
      (libsource (lib "eagle-import") (part "FATSQUARE_GROUP"))
    )
    (comp (ref "U$16")
      (value "FATSQUARE_GROUP")
      (footprint "eagle-import:FAT_SQUARE")
      (libsource (lib "eagle-import") (part "FATSQUARE_GROUP"))
    )
    (comp (ref "U2")
      (value "LDC1614")
      (footprint "eagle-import:WQFN-16")
      (libsource (lib "eagle-import") (part "LDC1614"))
    )
    (comp (ref "U4")
      (value "LDC1614")
      (footprint "eagle-import:WQFN-16")
      (libsource (lib "eagle-import") (part "LDC1614"))
    )
    (comp (ref "U5")
      (value "LDC1614")
      (footprint "eagle-import:WQFN-16")
      (libsource (lib "eagle-import") (part "LDC1614"))
    )
    (comp (ref "U6")
      (value "LDC1614")
      (footprint "eagle-import:WQFN-16")
      (libsource (lib "eagle-import") (part "LDC1614"))
    )
    (comp (ref "U8")
      (value "LDC1614")
      (footprint "eagle-import:WQFN-16")
      (libsource (lib "eagle-import") (part "LDC1614"))
    )
    (comp (ref "U9")
      (value "LDC1614")
      (footprint "eagle-import:WQFN-16")
      (libsource (lib "eagle-import") (part "LDC1614"))
    )
    (comp (ref "U10")
      (value "LDC1614")
      (footprint "eagle-import:WQFN-16")
      (libsource (lib "eagle-import") (part "LDC1614"))
    )
    (comp (ref "U12")
      (value "LDC1614")
      (footprint "eagle-import:WQFN-16")
      (libsource (lib "eagle-import") (part "LDC1614"))
    )
    (comp (ref "U14")
      (value "LDC1614")
      (footprint "eagle-import:WQFN-16")
      (libsource (lib "eagle-import") (part "LDC1614"))
    )
    (comp (ref "U16")
      (value "LDC1614")
      (footprint "eagle-import:WQFN-16")
      (libsource (lib "eagle-import") (part "LDC1614"))
    )
  )
  (nets
    (net (code "1") (name "GND") (class "Default")
      (node (ref "C10") (pin "2") (pinfunction "2_2") (pintype "passive"))
      (node (ref "C12") (pin "2") (pinfunction "2_2") (pintype "passive"))
      (node (ref "C14") (pin "2") (pinfunction "2_2") (pintype "passive"))
      (node (ref "C16") (pin "2") (pinfunction "2_2") (pintype "passive"))
      (node (ref "C19") (pin "2") (pinfunction "2_2") (pintype "passive"))
      (node (ref "C2") (pin "2") (pinfunction "2_2") (pintype "passive"))
      (node (ref "C21") (pin "2") (pinfunction "2_2") (pintype "passive"))
      (node (ref "C23") (pin "2") (pinfunction "2_2") (pintype "passive"))
      (node (ref "C25") (pin "2") (pinfunction "2_2") (pintype "passive"))
      (node (ref "C27") (pin "2") (pinfunction "2_2") (pintype "passive"))
      (node (ref "C29") (pin "2") (pinfunction "2_2") (pintype "passive"))
      (node (ref "C31") (pin "2") (pinfunction "2_2") (pintype "passive"))
      (node (ref "C33") (pin "2") (pinfunction "2_2") (pintype "passive"))
      (node (ref "C35") (pin "2") (pinfunction "2_2") (pintype "passive"))
      (node (ref "C37") (pin "2") (pinfunction "2_2") (pintype "passive"))
      (node (ref "C4") (pin "2") (pinfunction "2_2") (pintype "passive"))
      (node (ref "C5") (pin "2") (pinfunction "2_2") (pintype "passive"))
      (node (ref "C6") (pin "2") (pinfunction "2_2") (pintype "passive"))
      (node (ref "C8") (pin "2") (pinfunction "2_2") (pintype "passive"))
      (node (ref "C9") (pin "2") (pinfunction "2_2") (pintype "passive"))
      (node (ref "PAD101") (pin "1") (pinfunction "P_1") (pintype "passive"))
      (node (ref "PAD106") (pin "1") (pinfunction "P_1") (pintype "passive"))
      (node (ref "PAD11") (pin "1") (pinfunction "P_1") (pintype "passive"))
      (node (ref "PAD119") (pin "1") (pinfunction "P_1") (pintype "passive"))
      (node (ref "PAD124") (pin "1") (pinfunction "P_1") (pintype "passive"))
      (node (ref "PAD137") (pin "1") (pinfunction "P_1") (pintype "passive"))
      (node (ref "PAD142") (pin "1") (pinfunction "P_1") (pintype "passive"))
      (node (ref "PAD16") (pin "1") (pinfunction "P_1") (pintype "passive"))
      (node (ref "PAD166") (pin "1") (pinfunction "P_1") (pintype "passive"))
      (node (ref "PAD171") (pin "1") (pinfunction "P_1") (pintype "passive"))
      (node (ref "PAD186") (pin "1") (pinfunction "P_1") (pintype "passive"))
      (node (ref "PAD191") (pin "1") (pinfunction "P_1") (pintype "passive"))
      (node (ref "PAD206") (pin "1") (pinfunction "P_1") (pintype "passive"))
      (node (ref "PAD211") (pin "1") (pinfunction "P_1") (pintype "passive"))
      (node (ref "PAD226") (pin "1") (pinfunction "P_1") (pintype "passive"))
      (node (ref "PAD231") (pin "1") (pinfunction "P_1") (pintype "passive"))
      (node (ref "PAD246") (pin "1") (pinfunction "P_1") (pintype "passive"))
      (node (ref "PAD251") (pin "1") (pinfunction "P_1") (pintype "passive"))
      (node (ref "PAD266") (pin "1") (pinfunction "P_1") (pintype "passive"))
      (node (ref "PAD271") (pin "1") (pinfunction "P_1") (pintype "passive"))
      (node (ref "PAD286") (pin "1") (pinfunction "P_1") (pintype "passive"))
      (node (ref "PAD29") (pin "1") (pinfunction "P_1") (pintype "passive"))
      (node (ref "PAD291") (pin "1") (pinfunction "P_1") (pintype "passive"))
      (node (ref "PAD306") (pin "1") (pinfunction "P_1") (pintype "passive"))
      (node (ref "PAD311") (pin "1") (pinfunction "P_1") (pintype "passive"))
      (node (ref "PAD326") (pin "1") (pinfunction "P_1") (pintype "passive"))
      (node (ref "PAD331") (pin "1") (pinfunction "P_1") (pintype "passive"))
      (node (ref "PAD34") (pin "1") (pinfunction "P_1") (pintype "passive"))
      (node (ref "PAD346") (pin "1") (pinfunction "P_1") (pintype "passive"))
      (node (ref "PAD351") (pin "1") (pinfunction "P_1") (pintype "passive"))
      (node (ref "PAD38") (pin "1") (pinfunction "P_1") (pintype "passive"))
      (node (ref "PAD43") (pin "1") (pinfunction "P_1") (pintype "passive"))
      (node (ref "PAD47") (pin "1") (pinfunction "P_1") (pintype "passive"))
      (node (ref "PAD52") (pin "1") (pinfunction "P_1") (pintype "passive"))
      (node (ref "PAD65") (pin "1") (pinfunction "P_1") (pintype "passive"))
      (node (ref "PAD70") (pin "1") (pinfunction "P_1") (pintype "passive"))
      (node (ref "PAD74") (pin "1") (pinfunction "P_1") (pintype "passive"))
      (node (ref "PAD79") (pin "1") (pinfunction "P_1") (pintype "passive"))
      (node (ref "PAD83") (pin "1") (pinfunction "P_1") (pintype "passive"))
      (node (ref "PAD88") (pin "1") (pinfunction "P_1") (pintype "passive"))
      (node (ref "R100") (pin "1") (pinfunction "1_1") (pintype "passive"))
      (node (ref "R108") (pin "1") (pinfunction "1_1") (pintype "passive"))
      (node (ref "R116") (pin "1") (pinfunction "1_1") (pintype "passive"))
      (node (ref "R124") (pin "1") (pinfunction "1_1") (pintype "passive"))
      (node (ref "R132") (pin "1") (pinfunction "1_1") (pintype "passive"))
      (node (ref "R140") (pin "1") (pinfunction "1_1") (pintype "passive"))
      (node (ref "R148") (pin "1") (pinfunction "1_1") (pintype "passive"))
      (node (ref "R16") (pin "1") (pinfunction "1_1") (pintype "passive"))
      (node (ref "R20") (pin "1") (pinfunction "1_1") (pintype "passive"))
      (node (ref "R24") (pin "1") (pinfunction "1_1") (pintype "passive"))
      (node (ref "R32") (pin "1") (pinfunction "1_1") (pintype "passive"))
      (node (ref "R36") (pin "1") (pinfunction "1_1") (pintype "passive"))
      (node (ref "R40") (pin "1") (pinfunction "1_1") (pintype "passive"))
      (node (ref "R48") (pin "1") (pinfunction "1_1") (pintype "passive"))
      (node (ref "R56") (pin "1") (pinfunction "1_1") (pintype "passive"))
      (node (ref "R64") (pin "1") (pinfunction "1_1") (pintype "passive"))
      (node (ref "R76") (pin "1") (pinfunction "1_1") (pintype "passive"))
      (node (ref "R8") (pin "1") (pinfunction "1_1") (pintype "passive"))
      (node (ref "R84") (pin "1") (pinfunction "1_1") (pintype "passive"))
      (node (ref "R92") (pin "1") (pinfunction "1_1") (pintype "passive"))
      (node (ref "U10") (pin "CLIKIN") (pinfunction "CLKIN_CLIKIN") (pintype "bidirectional"))
      (node (ref "U10") (pin "DAP") (pinfunction "DAP_DAP") (pintype "bidirectional"))
      (node (ref "U10") (pin "GND") (pinfunction "GND_GND") (pintype "bidirectional"))
      (node (ref "U10") (pin "SD") (pinfunction "SD_SD") (pintype "bidirectional"))
      (node (ref "U12") (pin "CLIKIN") (pinfunction "CLKIN_CLIKIN") (pintype "bidirectional"))
      (node (ref "U12") (pin "DAP") (pinfunction "DAP_DAP") (pintype "bidirectional"))
      (node (ref "U12") (pin "GND") (pinfunction "GND_GND") (pintype "bidirectional"))
      (node (ref "U12") (pin "SD") (pinfunction "SD_SD") (pintype "bidirectional"))
      (node (ref "U14") (pin "CLIKIN") (pinfunction "CLKIN_CLIKIN") (pintype "bidirectional"))
      (node (ref "U14") (pin "DAP") (pinfunction "DAP_DAP") (pintype "bidirectional"))
      (node (ref "U14") (pin "GND") (pinfunction "GND_GND") (pintype "bidirectional"))
      (node (ref "U14") (pin "SD") (pinfunction "SD_SD") (pintype "bidirectional"))
      (node (ref "U16") (pin "CLIKIN") (pinfunction "CLKIN_CLIKIN") (pintype "bidirectional"))
      (node (ref "U16") (pin "DAP") (pinfunction "DAP_DAP") (pintype "bidirectional"))
      (node (ref "U16") (pin "GND") (pinfunction "GND_GND") (pintype "bidirectional"))
      (node (ref "U16") (pin "SD") (pinfunction "SD_SD") (pintype "bidirectional"))
      (node (ref "U19") (pin "CLIKIN") (pinfunction "CLKIN_CLIKIN") (pintype "bidirectional"))
      (node (ref "U19") (pin "DAP") (pinfunction "DAP_DAP") (pintype "bidirectional"))
      (node (ref "U19") (pin "GND") (pinfunction "GND_GND") (pintype "bidirectional"))
      (node (ref "U19") (pin "SD") (pinfunction "SD_SD") (pintype "bidirectional"))
      (node (ref "U2") (pin "CLIKIN") (pinfunction "CLKIN_CLIKIN") (pintype "bidirectional"))
      (node (ref "U2") (pin "DAP") (pinfunction "DAP_DAP") (pintype "bidirectional"))
      (node (ref "U2") (pin "GND") (pinfunction "GND_GND") (pintype "bidirectional"))
      (node (ref "U2") (pin "SD") (pinfunction "SD_SD") (pintype "bidirectional"))
      (node (ref "U21") (pin "CLIKIN") (pinfunction "CLKIN_CLIKIN") (pintype "bidirectional"))
      (node (ref "U21") (pin "DAP") (pinfunction "DAP_DAP") (pintype "bidirectional"))
      (node (ref "U21") (pin "GND") (pinfunction "GND_GND") (pintype "bidirectional"))
      (node (ref "U21") (pin "SD") (pinfunction "SD_SD") (pintype "bidirectional"))
      (node (ref "U23") (pin "CLIKIN") (pinfunction "CLKIN_CLIKIN") (pintype "bidirectional"))
      (node (ref "U23") (pin "DAP") (pinfunction "DAP_DAP") (pintype "bidirectional"))
      (node (ref "U23") (pin "GND") (pinfunction "GND_GND") (pintype "bidirectional"))
      (node (ref "U23") (pin "SD") (pinfunction "SD_SD") (pintype "bidirectional"))
      (node (ref "U25") (pin "CLIKIN") (pinfunction "CLKIN_CLIKIN") (pintype "bidirectional"))
      (node (ref "U25") (pin "DAP") (pinfunction "DAP_DAP") (pintype "bidirectional"))
      (node (ref "U25") (pin "GND") (pinfunction "GND_GND") (pintype "bidirectional"))
      (node (ref "U25") (pin "SD") (pinfunction "SD_SD") (pintype "bidirectional"))
      (node (ref "U27") (pin "CLIKIN") (pinfunction "CLKIN_CLIKIN") (pintype "bidirectional"))
      (node (ref "U27") (pin "DAP") (pinfunction "DAP_DAP") (pintype "bidirectional"))
      (node (ref "U27") (pin "GND") (pinfunction "GND_GND") (pintype "bidirectional"))
      (node (ref "U27") (pin "SD") (pinfunction "SD_SD") (pintype "bidirectional"))
      (node (ref "U29") (pin "CLIKIN") (pinfunction "CLKIN_CLIKIN") (pintype "bidirectional"))
      (node (ref "U29") (pin "DAP") (pinfunction "DAP_DAP") (pintype "bidirectional"))
      (node (ref "U29") (pin "GND") (pinfunction "GND_GND") (pintype "bidirectional"))
      (node (ref "U29") (pin "SD") (pinfunction "SD_SD") (pintype "bidirectional"))
      (node (ref "U31") (pin "CLIKIN") (pinfunction "CLKIN_CLIKIN") (pintype "bidirectional"))
      (node (ref "U31") (pin "DAP") (pinfunction "DAP_DAP") (pintype "bidirectional"))
      (node (ref "U31") (pin "GND") (pinfunction "GND_GND") (pintype "bidirectional"))
      (node (ref "U31") (pin "SD") (pinfunction "SD_SD") (pintype "bidirectional"))
      (node (ref "U33") (pin "CLIKIN") (pinfunction "CLKIN_CLIKIN") (pintype "bidirectional"))
      (node (ref "U33") (pin "DAP") (pinfunction "DAP_DAP") (pintype "bidirectional"))
      (node (ref "U33") (pin "GND") (pinfunction "GND_GND") (pintype "bidirectional"))
      (node (ref "U33") (pin "SD") (pinfunction "SD_SD") (pintype "bidirectional"))
      (node (ref "U35") (pin "CLIKIN") (pinfunction "CLKIN_CLIKIN") (pintype "bidirectional"))
      (node (ref "U35") (pin "DAP") (pinfunction "DAP_DAP") (pintype "bidirectional"))
      (node (ref "U35") (pin "GND") (pinfunction "GND_GND") (pintype "bidirectional"))
      (node (ref "U35") (pin "SD") (pinfunction "SD_SD") (pintype "bidirectional"))
      (node (ref "U37") (pin "CLIKIN") (pinfunction "CLKIN_CLIKIN") (pintype "bidirectional"))
      (node (ref "U37") (pin "DAP") (pinfunction "DAP_DAP") (pintype "bidirectional"))
      (node (ref "U37") (pin "GND") (pinfunction "GND_GND") (pintype "bidirectional"))
      (node (ref "U37") (pin "SD") (pinfunction "SD_SD") (pintype "bidirectional"))
      (node (ref "U4") (pin "CLIKIN") (pinfunction "CLKIN_CLIKIN") (pintype "bidirectional"))
      (node (ref "U4") (pin "DAP") (pinfunction "DAP_DAP") (pintype "bidirectional"))
      (node (ref "U4") (pin "GND") (pinfunction "GND_GND") (pintype "bidirectional"))
      (node (ref "U4") (pin "SD") (pinfunction "SD_SD") (pintype "bidirectional"))
      (node (ref "U5") (pin "CLIKIN") (pinfunction "CLKIN_CLIKIN") (pintype "bidirectional"))
      (node (ref "U5") (pin "DAP") (pinfunction "DAP_DAP") (pintype "bidirectional"))
      (node (ref "U5") (pin "GND") (pinfunction "GND_GND") (pintype "bidirectional"))
      (node (ref "U5") (pin "SD") (pinfunction "SD_SD") (pintype "bidirectional"))
      (node (ref "U6") (pin "CLIKIN") (pinfunction "CLKIN_CLIKIN") (pintype "bidirectional"))
      (node (ref "U6") (pin "DAP") (pinfunction "DAP_DAP") (pintype "bidirectional"))
      (node (ref "U6") (pin "GND") (pinfunction "GND_GND") (pintype "bidirectional"))
      (node (ref "U6") (pin "SD") (pinfunction "SD_SD") (pintype "bidirectional"))
      (node (ref "U8") (pin "CLIKIN") (pinfunction "CLKIN_CLIKIN") (pintype "bidirectional"))
      (node (ref "U8") (pin "DAP") (pinfunction "DAP_DAP") (pintype "bidirectional"))
      (node (ref "U8") (pin "GND") (pinfunction "GND_GND") (pintype "bidirectional"))
      (node (ref "U8") (pin "SD") (pinfunction "SD_SD") (pintype "bidirectional"))
      (node (ref "U9") (pin "CLIKIN") (pinfunction "CLKIN_CLIKIN") (pintype "bidirectional"))
      (node (ref "U9") (pin "DAP") (pinfunction "DAP_DAP") (pintype "bidirectional"))
      (node (ref "U9") (pin "GND") (pinfunction "GND_GND") (pintype "bidirectional"))
      (node (ref "U9") (pin "SD") (pinfunction "SD_SD") (pintype "bidirectional"))
    )
    (net (code "2") (name "Net-(PAD12-P)") (class "Default")
      (node (ref "PAD12") (pin "1") (pinfunction "P_1") (pintype "passive"))
      (node (ref "U2") (pin "INTB") (pinfunction "INTB_INTB") (pintype "bidirectional"))
    )
    (net (code "3") (name "Net-(PAD13-P)") (class "Default")
      (node (ref "PAD13") (pin "1") (pinfunction "P_1") (pintype "passive"))
      (node (ref "PAD17") (pin "1") (pinfunction "P_1") (pintype "passive"))
      (node (ref "R6") (pin "1") (pinfunction "1_1") (pintype "passive"))
      (node (ref "U2") (pin "SDA") (pinfunction "SDA_SDA") (pintype "bidirectional"))
    )
    (net (code "4") (name "Net-(PAD14-P)") (class "Default")
      (node (ref "PAD14") (pin "1") (pinfunction "P_1") (pintype "passive"))
      (node (ref "PAD18") (pin "1") (pinfunction "P_1") (pintype "passive"))
      (node (ref "R5") (pin "1") (pinfunction "1_1") (pintype "passive"))
      (node (ref "U2") (pin "SCL") (pinfunction "SCL_SCL") (pintype "bidirectional"))
    )
    (net (code "5") (name "Net-(PAD30-P)") (class "Default")
      (node (ref "PAD30") (pin "1") (pinfunction "P_1") (pintype "passive"))
      (node (ref "U4") (pin "INTB") (pinfunction "INTB_INTB") (pintype "bidirectional"))
    )
    (net (code "6") (name "Net-(PAD31-P)") (class "Default")
      (node (ref "PAD31") (pin "1") (pinfunction "P_1") (pintype "passive"))
      (node (ref "PAD35") (pin "1") (pinfunction "P_1") (pintype "passive"))
      (node (ref "R14") (pin "1") (pinfunction "1_1") (pintype "passive"))
      (node (ref "U4") (pin "SDA") (pinfunction "SDA_SDA") (pintype "bidirectional"))
    )
    (net (code "7") (name "Net-(PAD32-P)") (class "Default")
      (node (ref "PAD32") (pin "1") (pinfunction "P_1") (pintype "passive"))
      (node (ref "PAD36") (pin "1") (pinfunction "P_1") (pintype "passive"))
      (node (ref "R13") (pin "1") (pinfunction "1_1") (pintype "passive"))
      (node (ref "U4") (pin "SCL") (pinfunction "SCL_SCL") (pintype "bidirectional"))
    )
    (net (code "8") (name "Net-(PAD39-P)") (class "Default")
      (node (ref "PAD39") (pin "1") (pinfunction "P_1") (pintype "passive"))
      (node (ref "U5") (pin "INTB") (pinfunction "INTB_INTB") (pintype "bidirectional"))
    )
    (net (code "9") (name "Net-(PAD40-P)") (class "Default")
      (node (ref "PAD40") (pin "1") (pinfunction "P_1") (pintype "passive"))
      (node (ref "PAD44") (pin "1") (pinfunction "P_1") (pintype "passive"))
      (node (ref "R18") (pin "1") (pinfunction "1_1") (pintype "passive"))
      (node (ref "U5") (pin "SDA") (pinfunction "SDA_SDA") (pintype "bidirectional"))
    )
    (net (code "10") (name "Net-(PAD41-P)") (class "Default")
      (node (ref "PAD41") (pin "1") (pinfunction "P_1") (pintype "passive"))
      (node (ref "PAD45") (pin "1") (pinfunction "P_1") (pintype "passive"))
      (node (ref "R17") (pin "1") (pinfunction "1_1") (pintype "passive"))
      (node (ref "U5") (pin "SCL") (pinfunction "SCL_SCL") (pintype "bidirectional"))
    )
    (net (code "11") (name "Net-(PAD48-P)") (class "Default")
      (node (ref "PAD48") (pin "1") (pinfunction "P_1") (pintype "passive"))
      (node (ref "U6") (pin "INTB") (pinfunction "INTB_INTB") (pintype "bidirectional"))
    )
    (net (code "12") (name "Net-(PAD49-P)") (class "Default")
      (node (ref "PAD49") (pin "1") (pinfunction "P_1") (pintype "passive"))
      (node (ref "PAD53") (pin "1") (pinfunction "P_1") (pintype "passive"))
      (node (ref "R22") (pin "1") (pinfunction "1_1") (pintype "passive"))
      (node (ref "U6") (pin "SDA") (pinfunction "SDA_SDA") (pintype "bidirectional"))
    )
    (net (code "13") (name "Net-(PAD50-P)") (class "Default")
      (node (ref "PAD50") (pin "1") (pinfunction "P_1") (pintype "passive"))
      (node (ref "PAD54") (pin "1") (pinfunction "P_1") (pintype "passive"))
      (node (ref "R21") (pin "1") (pinfunction "1_1") (pintype "passive"))
      (node (ref "U6") (pin "SCL") (pinfunction "SCL_SCL") (pintype "bidirectional"))
    )
    (net (code "14") (name "Net-(PAD66-P)") (class "Default")
      (node (ref "PAD66") (pin "1") (pinfunction "P_1") (pintype "passive"))
      (node (ref "U8") (pin "INTB") (pinfunction "INTB_INTB") (pintype "bidirectional"))
    )
    (net (code "15") (name "Net-(PAD67-P)") (class "Default")
      (node (ref "PAD67") (pin "1") (pinfunction "P_1") (pintype "passive"))
      (node (ref "PAD71") (pin "1") (pinfunction "P_1") (pintype "passive"))
      (node (ref "R30") (pin "1") (pinfunction "1_1") (pintype "passive"))
      (node (ref "U8") (pin "SDA") (pinfunction "SDA_SDA") (pintype "bidirectional"))
    )
    (net (code "16") (name "Net-(PAD68-P)") (class "Default")
      (node (ref "PAD68") (pin "1") (pinfunction "P_1") (pintype "passive"))
      (node (ref "PAD72") (pin "1") (pinfunction "P_1") (pintype "passive"))
      (node (ref "R29") (pin "1") (pinfunction "1_1") (pintype "passive"))
      (node (ref "U8") (pin "SCL") (pinfunction "SCL_SCL") (pintype "bidirectional"))
    )
    (net (code "17") (name "Net-(PAD75-P)") (class "Default")
      (node (ref "PAD75") (pin "1") (pinfunction "P_1") (pintype "passive"))
      (node (ref "U9") (pin "INTB") (pinfunction "INTB_INTB") (pintype "bidirectional"))
    )
    (net (code "18") (name "Net-(PAD76-P)") (class "Default")
      (node (ref "PAD76") (pin "1") (pinfunction "P_1") (pintype "passive"))
      (node (ref "PAD80") (pin "1") (pinfunction "P_1") (pintype "passive"))
      (node (ref "R34") (pin "1") (pinfunction "1_1") (pintype "passive"))
      (node (ref "U9") (pin "SDA") (pinfunction "SDA_SDA") (pintype "bidirectional"))
    )
    (net (code "19") (name "Net-(PAD77-P)") (class "Default")
      (node (ref "PAD77") (pin "1") (pinfunction "P_1") (pintype "passive"))
      (node (ref "PAD81") (pin "1") (pinfunction "P_1") (pintype "passive"))
      (node (ref "R33") (pin "1") (pinfunction "1_1") (pintype "passive"))
      (node (ref "U9") (pin "SCL") (pinfunction "SCL_SCL") (pintype "bidirectional"))
    )
    (net (code "20") (name "Net-(PAD84-P)") (class "Default")
      (node (ref "PAD84") (pin "1") (pinfunction "P_1") (pintype "passive"))
      (node (ref "U10") (pin "INTB") (pinfunction "INTB_INTB") (pintype "bidirectional"))
    )
    (net (code "21") (name "Net-(PAD85-P)") (class "Default")
      (node (ref "PAD85") (pin "1") (pinfunction "P_1") (pintype "passive"))
      (node (ref "PAD89") (pin "1") (pinfunction "P_1") (pintype "passive"))
      (node (ref "R38") (pin "1") (pinfunction "1_1") (pintype "passive"))
      (node (ref "U10") (pin "SDA") (pinfunction "SDA_SDA") (pintype "bidirectional"))
    )
    (net (code "22") (name "Net-(PAD86-P)") (class "Default")
      (node (ref "PAD86") (pin "1") (pinfunction "P_1") (pintype "passive"))
      (node (ref "PAD90") (pin "1") (pinfunction "P_1") (pintype "passive"))
      (node (ref "R37") (pin "1") (pinfunction "1_1") (pintype "passive"))
      (node (ref "U10") (pin "SCL") (pinfunction "SCL_SCL") (pintype "bidirectional"))
    )
    (net (code "23") (name "Net-(PAD102-P)") (class "Default")
      (node (ref "PAD102") (pin "1") (pinfunction "P_1") (pintype "passive"))
      (node (ref "U12") (pin "INTB") (pinfunction "INTB_INTB") (pintype "bidirectional"))
    )
    (net (code "24") (name "Net-(PAD103-P)") (class "Default")
      (node (ref "PAD103") (pin "1") (pinfunction "P_1") (pintype "passive"))
      (node (ref "PAD107") (pin "1") (pinfunction "P_1") (pintype "passive"))
      (node (ref "R46") (pin "1") (pinfunction "1_1") (pintype "passive"))
      (node (ref "U12") (pin "SDA") (pinfunction "SDA_SDA") (pintype "bidirectional"))
    )
    (net (code "25") (name "Net-(PAD104-P)") (class "Default")
      (node (ref "PAD104") (pin "1") (pinfunction "P_1") (pintype "passive"))
      (node (ref "PAD108") (pin "1") (pinfunction "P_1") (pintype "passive"))
      (node (ref "R45") (pin "1") (pinfunction "1_1") (pintype "passive"))
      (node (ref "U12") (pin "SCL") (pinfunction "SCL_SCL") (pintype "bidirectional"))
    )
    (net (code "26") (name "Net-(PAD120-P)") (class "Default")
      (node (ref "PAD120") (pin "1") (pinfunction "P_1") (pintype "passive"))
      (node (ref "U14") (pin "INTB") (pinfunction "INTB_INTB") (pintype "bidirectional"))
    )
    (net (code "27") (name "Net-(PAD121-P)") (class "Default")
      (node (ref "PAD121") (pin "1") (pinfunction "P_1") (pintype "passive"))
      (node (ref "PAD125") (pin "1") (pinfunction "P_1") (pintype "passive"))
      (node (ref "R54") (pin "1") (pinfunction "1_1") (pintype "passive"))
      (node (ref "U14") (pin "SDA") (pinfunction "SDA_SDA") (pintype "bidirectional"))
    )
    (net (code "28") (name "Net-(PAD122-P)") (class "Default")
      (node (ref "PAD122") (pin "1") (pinfunction "P_1") (pintype "passive"))
      (node (ref "PAD126") (pin "1") (pinfunction "P_1") (pintype "passive"))
      (node (ref "R53") (pin "1") (pinfunction "1_1") (pintype "passive"))
      (node (ref "U14") (pin "SCL") (pinfunction "SCL_SCL") (pintype "bidirectional"))
    )
    (net (code "29") (name "Net-(PAD138-P)") (class "Default")
      (node (ref "PAD138") (pin "1") (pinfunction "P_1") (pintype "passive"))
      (node (ref "U16") (pin "INTB") (pinfunction "INTB_INTB") (pintype "bidirectional"))
    )
    (net (code "30") (name "Net-(PAD139-P)") (class "Default")
      (node (ref "PAD139") (pin "1") (pinfunction "P_1") (pintype "passive"))
      (node (ref "PAD143") (pin "1") (pinfunction "P_1") (pintype "passive"))
      (node (ref "R62") (pin "1") (pinfunction "1_1") (pintype "passive"))
      (node (ref "U16") (pin "SDA") (pinfunction "SDA_SDA") (pintype "bidirectional"))
    )
    (net (code "31") (name "Net-(PAD140-P)") (class "Default")
      (node (ref "PAD140") (pin "1") (pinfunction "P_1") (pintype "passive"))
      (node (ref "PAD144") (pin "1") (pinfunction "P_1") (pintype "passive"))
      (node (ref "R61") (pin "1") (pinfunction "1_1") (pintype "passive"))
      (node (ref "U16") (pin "SCL") (pinfunction "SCL_SCL") (pintype "bidirectional"))
    )
    (net (code "32") (name "Net-(PAD167-P)") (class "Default")
      (node (ref "PAD167") (pin "1") (pinfunction "P_1") (pintype "passive"))
      (node (ref "PAD172") (pin "1") (pinfunction "P_1") (pintype "passive"))
      (node (ref "U19") (pin "INTB") (pinfunction "INTB_INTB") (pintype "bidirectional"))
    )
    (net (code "33") (name "Net-(PAD168-P)") (class "Default")
      (node (ref "PAD168") (pin "1") (pinfunction "P_1") (pintype "passive"))
      (node (ref "PAD173") (pin "1") (pinfunction "P_1") (pintype "passive"))
      (node (ref "R74") (pin "1") (pinfunction "1_1") (pintype "passive"))
      (node (ref "U19") (pin "SDA") (pinfunction "SDA_SDA") (pintype "bidirectional"))
    )
    (net (code "34") (name "Net-(PAD169-P)") (class "Default")
      (node (ref "PAD169") (pin "1") (pinfunction "P_1") (pintype "passive"))
      (node (ref "PAD174") (pin "1") (pinfunction "P_1") (pintype "passive"))
      (node (ref "R73") (pin "1") (pinfunction "1_1") (pintype "passive"))
      (node (ref "U19") (pin "SCL") (pinfunction "SCL_SCL") (pintype "bidirectional"))
    )
    (net (code "35") (name "Net-(PAD187-P)") (class "Default")
      (node (ref "PAD187") (pin "1") (pinfunction "P_1") (pintype "passive"))
      (node (ref "PAD192") (pin "1") (pinfunction "P_1") (pintype "passive"))
      (node (ref "U21") (pin "INTB") (pinfunction "INTB_INTB") (pintype "bidirectional"))
    )
    (net (code "36") (name "Net-(PAD188-P)") (class "Default")
      (node (ref "PAD188") (pin "1") (pinfunction "P_1") (pintype "passive"))
      (node (ref "PAD193") (pin "1") (pinfunction "P_1") (pintype "passive"))
      (node (ref "R82") (pin "1") (pinfunction "1_1") (pintype "passive"))
      (node (ref "U21") (pin "SDA") (pinfunction "SDA_SDA") (pintype "bidirectional"))
    )
    (net (code "37") (name "Net-(PAD189-P)") (class "Default")
      (node (ref "PAD189") (pin "1") (pinfunction "P_1") (pintype "passive"))
      (node (ref "PAD194") (pin "1") (pinfunction "P_1") (pintype "passive"))
      (node (ref "R81") (pin "1") (pinfunction "1_1") (pintype "passive"))
      (node (ref "U21") (pin "SCL") (pinfunction "SCL_SCL") (pintype "bidirectional"))
    )
    (net (code "38") (name "Net-(PAD207-P)") (class "Default")
      (node (ref "PAD207") (pin "1") (pinfunction "P_1") (pintype "passive"))
      (node (ref "PAD212") (pin "1") (pinfunction "P_1") (pintype "passive"))
      (node (ref "U23") (pin "INTB") (pinfunction "INTB_INTB") (pintype "bidirectional"))
    )
    (net (code "39") (name "Net-(PAD208-P)") (class "Default")
      (node (ref "PAD208") (pin "1") (pinfunction "P_1") (pintype "passive"))
      (node (ref "PAD213") (pin "1") (pinfunction "P_1") (pintype "passive"))
      (node (ref "R90") (pin "1") (pinfunction "1_1") (pintype "passive"))
      (node (ref "U23") (pin "SDA") (pinfunction "SDA_SDA") (pintype "bidirectional"))
    )
    (net (code "40") (name "Net-(PAD209-P)") (class "Default")
      (node (ref "PAD209") (pin "1") (pinfunction "P_1") (pintype "passive"))
      (node (ref "PAD214") (pin "1") (pinfunction "P_1") (pintype "passive"))
      (node (ref "R89") (pin "1") (pinfunction "1_1") (pintype "passive"))
      (node (ref "U23") (pin "SCL") (pinfunction "SCL_SCL") (pintype "bidirectional"))
    )
    (net (code "41") (name "Net-(PAD227-P)") (class "Default")
      (node (ref "PAD227") (pin "1") (pinfunction "P_1") (pintype "passive"))
      (node (ref "PAD232") (pin "1") (pinfunction "P_1") (pintype "passive"))
      (node (ref "U25") (pin "INTB") (pinfunction "INTB_INTB") (pintype "bidirectional"))
    )
    (net (code "42") (name "Net-(PAD228-P)") (class "Default")
      (node (ref "PAD228") (pin "1") (pinfunction "P_1") (pintype "passive"))
      (node (ref "PAD233") (pin "1") (pinfunction "P_1") (pintype "passive"))
      (node (ref "R98") (pin "1") (pinfunction "1_1") (pintype "passive"))
      (node (ref "U25") (pin "SDA") (pinfunction "SDA_SDA") (pintype "bidirectional"))
    )
    (net (code "43") (name "Net-(PAD229-P)") (class "Default")
      (node (ref "PAD229") (pin "1") (pinfunction "P_1") (pintype "passive"))
      (node (ref "PAD234") (pin "1") (pinfunction "P_1") (pintype "passive"))
      (node (ref "R97") (pin "1") (pinfunction "1_1") (pintype "passive"))
      (node (ref "U25") (pin "SCL") (pinfunction "SCL_SCL") (pintype "bidirectional"))
    )
    (net (code "44") (name "Net-(PAD247-P)") (class "Default")
      (node (ref "PAD247") (pin "1") (pinfunction "P_1") (pintype "passive"))
      (node (ref "PAD252") (pin "1") (pinfunction "P_1") (pintype "passive"))
      (node (ref "U27") (pin "INTB") (pinfunction "INTB_INTB") (pintype "bidirectional"))
    )
    (net (code "45") (name "Net-(PAD248-P)") (class "Default")
      (node (ref "PAD248") (pin "1") (pinfunction "P_1") (pintype "passive"))
      (node (ref "PAD253") (pin "1") (pinfunction "P_1") (pintype "passive"))
      (node (ref "R106") (pin "1") (pinfunction "1_1") (pintype "passive"))
      (node (ref "U27") (pin "SDA") (pinfunction "SDA_SDA") (pintype "bidirectional"))
    )
    (net (code "46") (name "Net-(PAD249-P)") (class "Default")
      (node (ref "PAD249") (pin "1") (pinfunction "P_1") (pintype "passive"))
      (node (ref "PAD254") (pin "1") (pinfunction "P_1") (pintype "passive"))
      (node (ref "R105") (pin "1") (pinfunction "1_1") (pintype "passive"))
      (node (ref "U27") (pin "SCL") (pinfunction "SCL_SCL") (pintype "bidirectional"))
    )
    (net (code "47") (name "Net-(PAD267-P)") (class "Default")
      (node (ref "PAD267") (pin "1") (pinfunction "P_1") (pintype "passive"))
      (node (ref "PAD272") (pin "1") (pinfunction "P_1") (pintype "passive"))
      (node (ref "U29") (pin "INTB") (pinfunction "INTB_INTB") (pintype "bidirectional"))
    )
    (net (code "48") (name "Net-(PAD268-P)") (class "Default")
      (node (ref "PAD268") (pin "1") (pinfunction "P_1") (pintype "passive"))
      (node (ref "PAD273") (pin "1") (pinfunction "P_1") (pintype "passive"))
      (node (ref "R114") (pin "1") (pinfunction "1_1") (pintype "passive"))
      (node (ref "U29") (pin "SDA") (pinfunction "SDA_SDA") (pintype "bidirectional"))
    )
    (net (code "49") (name "Net-(PAD269-P)") (class "Default")
      (node (ref "PAD269") (pin "1") (pinfunction "P_1") (pintype "passive"))
      (node (ref "PAD274") (pin "1") (pinfunction "P_1") (pintype "passive"))
      (node (ref "R113") (pin "1") (pinfunction "1_1") (pintype "passive"))
      (node (ref "U29") (pin "SCL") (pinfunction "SCL_SCL") (pintype "bidirectional"))
    )
    (net (code "50") (name "Net-(PAD287-P)") (class "Default")
      (node (ref "PAD287") (pin "1") (pinfunction "P_1") (pintype "passive"))
      (node (ref "PAD292") (pin "1") (pinfunction "P_1") (pintype "passive"))
      (node (ref "U31") (pin "INTB") (pinfunction "INTB_INTB") (pintype "bidirectional"))
    )
    (net (code "51") (name "Net-(PAD288-P)") (class "Default")
      (node (ref "PAD288") (pin "1") (pinfunction "P_1") (pintype "passive"))
      (node (ref "PAD293") (pin "1") (pinfunction "P_1") (pintype "passive"))
      (node (ref "R122") (pin "1") (pinfunction "1_1") (pintype "passive"))
      (node (ref "U31") (pin "SDA") (pinfunction "SDA_SDA") (pintype "bidirectional"))
    )
    (net (code "52") (name "Net-(PAD289-P)") (class "Default")
      (node (ref "PAD289") (pin "1") (pinfunction "P_1") (pintype "passive"))
      (node (ref "PAD294") (pin "1") (pinfunction "P_1") (pintype "passive"))
      (node (ref "R121") (pin "1") (pinfunction "1_1") (pintype "passive"))
      (node (ref "U31") (pin "SCL") (pinfunction "SCL_SCL") (pintype "bidirectional"))
    )
    (net (code "53") (name "Net-(PAD307-P)") (class "Default")
      (node (ref "PAD307") (pin "1") (pinfunction "P_1") (pintype "passive"))
      (node (ref "PAD312") (pin "1") (pinfunction "P_1") (pintype "passive"))
      (node (ref "U33") (pin "INTB") (pinfunction "INTB_INTB") (pintype "bidirectional"))
    )
    (net (code "54") (name "Net-(PAD308-P)") (class "Default")
      (node (ref "PAD308") (pin "1") (pinfunction "P_1") (pintype "passive"))
      (node (ref "PAD313") (pin "1") (pinfunction "P_1") (pintype "passive"))
      (node (ref "R130") (pin "1") (pinfunction "1_1") (pintype "passive"))
      (node (ref "U33") (pin "SDA") (pinfunction "SDA_SDA") (pintype "bidirectional"))
    )
    (net (code "55") (name "Net-(PAD309-P)") (class "Default")
      (node (ref "PAD309") (pin "1") (pinfunction "P_1") (pintype "passive"))
      (node (ref "PAD314") (pin "1") (pinfunction "P_1") (pintype "passive"))
      (node (ref "R129") (pin "1") (pinfunction "1_1") (pintype "passive"))
      (node (ref "U33") (pin "SCL") (pinfunction "SCL_SCL") (pintype "bidirectional"))
    )
    (net (code "56") (name "Net-(PAD327-P)") (class "Default")
      (node (ref "PAD327") (pin "1") (pinfunction "P_1") (pintype "passive"))
      (node (ref "PAD332") (pin "1") (pinfunction "P_1") (pintype "passive"))
      (node (ref "U35") (pin "INTB") (pinfunction "INTB_INTB") (pintype "bidirectional"))
    )
    (net (code "57") (name "Net-(PAD328-P)") (class "Default")
      (node (ref "PAD328") (pin "1") (pinfunction "P_1") (pintype "passive"))
      (node (ref "PAD333") (pin "1") (pinfunction "P_1") (pintype "passive"))
      (node (ref "R138") (pin "1") (pinfunction "1_1") (pintype "passive"))
      (node (ref "U35") (pin "SDA") (pinfunction "SDA_SDA") (pintype "bidirectional"))
    )
    (net (code "58") (name "Net-(PAD329-P)") (class "Default")
      (node (ref "PAD329") (pin "1") (pinfunction "P_1") (pintype "passive"))
      (node (ref "PAD334") (pin "1") (pinfunction "P_1") (pintype "passive"))
      (node (ref "R137") (pin "1") (pinfunction "1_1") (pintype "passive"))
      (node (ref "U35") (pin "SCL") (pinfunction "SCL_SCL") (pintype "bidirectional"))
    )
    (net (code "59") (name "Net-(PAD347-P)") (class "Default")
      (node (ref "PAD347") (pin "1") (pinfunction "P_1") (pintype "passive"))
      (node (ref "PAD352") (pin "1") (pinfunction "P_1") (pintype "passive"))
      (node (ref "U37") (pin "INTB") (pinfunction "INTB_INTB") (pintype "bidirectional"))
    )
    (net (code "60") (name "Net-(PAD348-P)") (class "Default")
      (node (ref "PAD348") (pin "1") (pinfunction "P_1") (pintype "passive"))
      (node (ref "PAD353") (pin "1") (pinfunction "P_1") (pintype "passive"))
      (node (ref "R146") (pin "1") (pinfunction "1_1") (pintype "passive"))
      (node (ref "U37") (pin "SDA") (pinfunction "SDA_SDA") (pintype "bidirectional"))
    )
    (net (code "61") (name "Net-(PAD349-P)") (class "Default")
      (node (ref "PAD349") (pin "1") (pinfunction "P_1") (pintype "passive"))
      (node (ref "PAD354") (pin "1") (pinfunction "P_1") (pintype "passive"))
      (node (ref "R145") (pin "1") (pinfunction "1_1") (pintype "passive"))
      (node (ref "U37") (pin "SCL") (pinfunction "SCL_SCL") (pintype "bidirectional"))
    )
    (net (code "62") (name "Net-(R7-Pad1)") (class "Default")
      (node (ref "R7") (pin "1") (pinfunction "1_1") (pintype "passive"))
      (node (ref "R8") (pin "2") (pinfunction "2_2") (pintype "passive"))
      (node (ref "U2") (pin "ADDR") (pinfunction "ADDR_ADDR") (pintype "bidirectional"))
    )
    (net (code "63") (name "Net-(R15-Pad1)") (class "Default")
      (node (ref "R15") (pin "1") (pinfunction "1_1") (pintype "passive"))
      (node (ref "R16") (pin "2") (pinfunction "2_2") (pintype "passive"))
      (node (ref "U4") (pin "ADDR") (pinfunction "ADDR_ADDR") (pintype "bidirectional"))
    )
    (net (code "64") (name "Net-(R19-Pad1)") (class "Default")
      (node (ref "R19") (pin "1") (pinfunction "1_1") (pintype "passive"))
      (node (ref "R20") (pin "2") (pinfunction "2_2") (pintype "passive"))
      (node (ref "U5") (pin "ADDR") (pinfunction "ADDR_ADDR") (pintype "bidirectional"))
    )
    (net (code "65") (name "Net-(R23-Pad1)") (class "Default")
      (node (ref "R23") (pin "1") (pinfunction "1_1") (pintype "passive"))
      (node (ref "R24") (pin "2") (pinfunction "2_2") (pintype "passive"))
      (node (ref "U6") (pin "ADDR") (pinfunction "ADDR_ADDR") (pintype "bidirectional"))
    )
    (net (code "66") (name "Net-(R31-Pad1)") (class "Default")
      (node (ref "R31") (pin "1") (pinfunction "1_1") (pintype "passive"))
      (node (ref "R32") (pin "2") (pinfunction "2_2") (pintype "passive"))
      (node (ref "U8") (pin "ADDR") (pinfunction "ADDR_ADDR") (pintype "bidirectional"))
    )
    (net (code "67") (name "Net-(R35-Pad1)") (class "Default")
      (node (ref "R35") (pin "1") (pinfunction "1_1") (pintype "passive"))
      (node (ref "R36") (pin "2") (pinfunction "2_2") (pintype "passive"))
      (node (ref "U9") (pin "ADDR") (pinfunction "ADDR_ADDR") (pintype "bidirectional"))
    )
    (net (code "68") (name "Net-(R39-Pad1)") (class "Default")
      (node (ref "R39") (pin "1") (pinfunction "1_1") (pintype "passive"))
      (node (ref "R40") (pin "2") (pinfunction "2_2") (pintype "passive"))
      (node (ref "U10") (pin "ADDR") (pinfunction "ADDR_ADDR") (pintype "bidirectional"))
    )
    (net (code "69") (name "Net-(R47-Pad1)") (class "Default")
      (node (ref "R47") (pin "1") (pinfunction "1_1") (pintype "passive"))
      (node (ref "R48") (pin "2") (pinfunction "2_2") (pintype "passive"))
      (node (ref "U12") (pin "ADDR") (pinfunction "ADDR_ADDR") (pintype "bidirectional"))
    )
    (net (code "70") (name "Net-(R55-Pad1)") (class "Default")
      (node (ref "R55") (pin "1") (pinfunction "1_1") (pintype "passive"))
      (node (ref "R56") (pin "2") (pinfunction "2_2") (pintype "passive"))
      (node (ref "U14") (pin "ADDR") (pinfunction "ADDR_ADDR") (pintype "bidirectional"))
    )
    (net (code "71") (name "Net-(R63-Pad1)") (class "Default")
      (node (ref "R63") (pin "1") (pinfunction "1_1") (pintype "passive"))
      (node (ref "R64") (pin "2") (pinfunction "2_2") (pintype "passive"))
      (node (ref "U16") (pin "ADDR") (pinfunction "ADDR_ADDR") (pintype "bidirectional"))
    )
    (net (code "72") (name "Net-(R75-Pad1)") (class "Default")
      (node (ref "R75") (pin "1") (pinfunction "1_1") (pintype "passive"))
      (node (ref "R76") (pin "2") (pinfunction "2_2") (pintype "passive"))
      (node (ref "U19") (pin "ADDR") (pinfunction "ADDR_ADDR") (pintype "bidirectional"))
    )
    (net (code "73") (name "Net-(R83-Pad1)") (class "Default")
      (node (ref "R83") (pin "1") (pinfunction "1_1") (pintype "passive"))
      (node (ref "R84") (pin "2") (pinfunction "2_2") (pintype "passive"))
      (node (ref "U21") (pin "ADDR") (pinfunction "ADDR_ADDR") (pintype "bidirectional"))
    )
    (net (code "74") (name "Net-(R91-Pad1)") (class "Default")
      (node (ref "R91") (pin "1") (pinfunction "1_1") (pintype "passive"))
      (node (ref "R92") (pin "2") (pinfunction "2_2") (pintype "passive"))
      (node (ref "U23") (pin "ADDR") (pinfunction "ADDR_ADDR") (pintype "bidirectional"))
    )
    (net (code "75") (name "Net-(R100-Pad2)") (class "Default")
      (node (ref "R100") (pin "2") (pinfunction "2_2") (pintype "passive"))
      (node (ref "R99") (pin "1") (pinfunction "1_1") (pintype "passive"))
      (node (ref "U25") (pin "ADDR") (pinfunction "ADDR_ADDR") (pintype "bidirectional"))
    )
    (net (code "76") (name "Net-(R107-Pad1)") (class "Default")
      (node (ref "R107") (pin "1") (pinfunction "1_1") (pintype "passive"))
      (node (ref "R108") (pin "2") (pinfunction "2_2") (pintype "passive"))
      (node (ref "U27") (pin "ADDR") (pinfunction "ADDR_ADDR") (pintype "bidirectional"))
    )
    (net (code "77") (name "Net-(R115-Pad1)") (class "Default")
      (node (ref "R115") (pin "1") (pinfunction "1_1") (pintype "passive"))
      (node (ref "R116") (pin "2") (pinfunction "2_2") (pintype "passive"))
      (node (ref "U29") (pin "ADDR") (pinfunction "ADDR_ADDR") (pintype "bidirectional"))
    )
    (net (code "78") (name "Net-(R123-Pad1)") (class "Default")
      (node (ref "R123") (pin "1") (pinfunction "1_1") (pintype "passive"))
      (node (ref "R124") (pin "2") (pinfunction "2_2") (pintype "passive"))
      (node (ref "U31") (pin "ADDR") (pinfunction "ADDR_ADDR") (pintype "bidirectional"))
    )
    (net (code "79") (name "Net-(R131-Pad1)") (class "Default")
      (node (ref "R131") (pin "1") (pinfunction "1_1") (pintype "passive"))
      (node (ref "R132") (pin "2") (pinfunction "2_2") (pintype "passive"))
      (node (ref "U33") (pin "ADDR") (pinfunction "ADDR_ADDR") (pintype "bidirectional"))
    )
    (net (code "80") (name "Net-(R139-Pad1)") (class "Default")
      (node (ref "R139") (pin "1") (pinfunction "1_1") (pintype "passive"))
      (node (ref "R140") (pin "2") (pinfunction "2_2") (pintype "passive"))
      (node (ref "U35") (pin "ADDR") (pinfunction "ADDR_ADDR") (pintype "bidirectional"))
    )
    (net (code "81") (name "Net-(R147-Pad1)") (class "Default")
      (node (ref "R147") (pin "1") (pinfunction "1_1") (pintype "passive"))
      (node (ref "R148") (pin "2") (pinfunction "2_2") (pintype "passive"))
      (node (ref "U37") (pin "ADDR") (pinfunction "ADDR_ADDR") (pintype "bidirectional"))
    )
    (net (code "82") (name "Net-(U$1-PadEXITCOIL0)") (class "Default")
      (node (ref "U$1") (pin "EXITCOIL0") (pinfunction "EXITCOIL0_EXITCOIL0") (pintype "bidirectional"))
      (node (ref "U2") (pin "IN1B") (pinfunction "IN1B_IN1B") (pintype "bidirectional"))
    )
    (net (code "83") (name "Net-(U$1-PadEXITCOIL1)") (class "Default")
      (node (ref "U$1") (pin "EXITCOIL1") (pinfunction "EXITCOIL1_EXITCOIL1") (pintype "bidirectional"))
      (node (ref "U2") (pin "IN0B") (pinfunction "IN0B_IN0B") (pintype "bidirectional"))
    )
    (net (code "84") (name "Net-(U$1-PadEXITCOIL2)") (class "Default")
      (node (ref "U$1") (pin "EXITCOIL2") (pinfunction "EXITCOIL2_EXITCOIL2") (pintype "bidirectional"))
      (node (ref "U2") (pin "IN2A") (pinfunction "IN2A_IN2A") (pintype "bidirectional"))
    )
    (net (code "85") (name "Net-(U$1-PadEXITCOIL3)") (class "Default")
      (node (ref "U$1") (pin "EXITCOIL3") (pinfunction "EXITCOIL3_EXITCOIL3") (pintype "bidirectional"))
      (node (ref "U2") (pin "IN3B") (pinfunction "IN3B_IN3B") (pintype "bidirectional"))
    )
    (net (code "86") (name "Net-(U$1-PadINCOIL0)") (class "Default")
      (node (ref "U$1") (pin "INCOIL0") (pinfunction "INCOIL0_INCOIL0") (pintype "bidirectional"))
      (node (ref "U2") (pin "IN1A") (pinfunction "IN1A_IN1A") (pintype "bidirectional"))
    )
    (net (code "87") (name "Net-(U$1-PadINCOIL1)") (class "Default")
      (node (ref "U$1") (pin "INCOIL1") (pinfunction "INCOIL1_INCOIL1") (pintype "bidirectional"))
      (node (ref "U2") (pin "IN0A") (pinfunction "IN0A_IN0A") (pintype "bidirectional"))
    )
    (net (code "88") (name "Net-(U$1-PadINCOIL2)") (class "Default")
      (node (ref "U$1") (pin "INCOIL2") (pinfunction "INCOIL2_INCOIL2") (pintype "bidirectional"))
      (node (ref "U2") (pin "IN2B") (pinfunction "IN2B_IN2B") (pintype "bidirectional"))
    )
    (net (code "89") (name "Net-(U$1-PadINCOIL3)") (class "Default")
      (node (ref "U$1") (pin "INCOIL3") (pinfunction "INCOIL3_INCOIL3") (pintype "bidirectional"))
      (node (ref "U2") (pin "IN3A") (pinfunction "IN3A_IN3A") (pintype "bidirectional"))
    )
    (net (code "90") (name "Net-(U$4-PadEXITCOIL0)") (class "Default")
      (node (ref "U$4") (pin "EXITCOIL0") (pinfunction "EXITCOIL0_EXITCOIL0") (pintype "bidirectional"))
      (node (ref "U4") (pin "IN1B") (pinfunction "IN1B_IN1B") (pintype "bidirectional"))
    )
    (net (code "91") (name "Net-(U$4-PadEXITCOIL1)") (class "Default")
      (node (ref "U$4") (pin "EXITCOIL1") (pinfunction "EXITCOIL1_EXITCOIL1") (pintype "bidirectional"))
      (node (ref "U4") (pin "IN0B") (pinfunction "IN0B_IN0B") (pintype "bidirectional"))
    )
    (net (code "92") (name "Net-(U$4-PadEXITCOIL2)") (class "Default")
      (node (ref "U$4") (pin "EXITCOIL2") (pinfunction "EXITCOIL2_EXITCOIL2") (pintype "bidirectional"))
      (node (ref "U4") (pin "IN2A") (pinfunction "IN2A_IN2A") (pintype "bidirectional"))
    )
    (net (code "93") (name "Net-(U$4-PadEXITCOIL3)") (class "Default")
      (node (ref "U$4") (pin "EXITCOIL3") (pinfunction "EXITCOIL3_EXITCOIL3") (pintype "bidirectional"))
      (node (ref "U4") (pin "IN3B") (pinfunction "IN3B_IN3B") (pintype "bidirectional"))
    )
    (net (code "94") (name "Net-(U$4-PadINCOIL0)") (class "Default")
      (node (ref "U$4") (pin "INCOIL0") (pinfunction "INCOIL0_INCOIL0") (pintype "bidirectional"))
      (node (ref "U4") (pin "IN1A") (pinfunction "IN1A_IN1A") (pintype "bidirectional"))
    )
    (net (code "95") (name "Net-(U$4-PadINCOIL1)") (class "Default")
      (node (ref "U$4") (pin "INCOIL1") (pinfunction "INCOIL1_INCOIL1") (pintype "bidirectional"))
      (node (ref "U4") (pin "IN0A") (pinfunction "IN0A_IN0A") (pintype "bidirectional"))
    )
    (net (code "96") (name "Net-(U$4-PadINCOIL2)") (class "Default")
      (node (ref "U$4") (pin "INCOIL2") (pinfunction "INCOIL2_INCOIL2") (pintype "bidirectional"))
      (node (ref "U4") (pin "IN2B") (pinfunction "IN2B_IN2B") (pintype "bidirectional"))
    )
    (net (code "97") (name "Net-(U$4-PadINCOIL3)") (class "Default")
      (node (ref "U$4") (pin "INCOIL3") (pinfunction "INCOIL3_INCOIL3") (pintype "bidirectional"))
      (node (ref "U4") (pin "IN3A") (pinfunction "IN3A_IN3A") (pintype "bidirectional"))
    )
    (net (code "98") (name "Net-(U$5-PadEXITCOIL0)") (class "Default")
      (node (ref "U$5") (pin "EXITCOIL0") (pinfunction "EXITCOIL0_EXITCOIL0") (pintype "bidirectional"))
      (node (ref "U5") (pin "IN1B") (pinfunction "IN1B_IN1B") (pintype "bidirectional"))
    )
    (net (code "99") (name "Net-(U$5-PadEXITCOIL1)") (class "Default")
      (node (ref "U$5") (pin "EXITCOIL1") (pinfunction "EXITCOIL1_EXITCOIL1") (pintype "bidirectional"))
      (node (ref "U5") (pin "IN0B") (pinfunction "IN0B_IN0B") (pintype "bidirectional"))
    )
    (net (code "100") (name "Net-(U$5-PadEXITCOIL2)") (class "Default")
      (node (ref "U$5") (pin "EXITCOIL2") (pinfunction "EXITCOIL2_EXITCOIL2") (pintype "bidirectional"))
      (node (ref "U5") (pin "IN2A") (pinfunction "IN2A_IN2A") (pintype "bidirectional"))
    )
    (net (code "101") (name "Net-(U$5-PadEXITCOIL3)") (class "Default")
      (node (ref "U$5") (pin "EXITCOIL3") (pinfunction "EXITCOIL3_EXITCOIL3") (pintype "bidirectional"))
      (node (ref "U5") (pin "IN3B") (pinfunction "IN3B_IN3B") (pintype "bidirectional"))
    )
    (net (code "102") (name "Net-(U$5-PadINCOIL0)") (class "Default")
      (node (ref "U$5") (pin "INCOIL0") (pinfunction "INCOIL0_INCOIL0") (pintype "bidirectional"))
      (node (ref "U5") (pin "IN1A") (pinfunction "IN1A_IN1A") (pintype "bidirectional"))
    )
    (net (code "103") (name "Net-(U$5-PadINCOIL1)") (class "Default")
      (node (ref "U$5") (pin "INCOIL1") (pinfunction "INCOIL1_INCOIL1") (pintype "bidirectional"))
      (node (ref "U5") (pin "IN0A") (pinfunction "IN0A_IN0A") (pintype "bidirectional"))
    )
    (net (code "104") (name "Net-(U$5-PadINCOIL2)") (class "Default")
      (node (ref "U$5") (pin "INCOIL2") (pinfunction "INCOIL2_INCOIL2") (pintype "bidirectional"))
      (node (ref "U5") (pin "IN2B") (pinfunction "IN2B_IN2B") (pintype "bidirectional"))
    )
    (net (code "105") (name "Net-(U$5-PadINCOIL3)") (class "Default")
      (node (ref "U$5") (pin "INCOIL3") (pinfunction "INCOIL3_INCOIL3") (pintype "bidirectional"))
      (node (ref "U5") (pin "IN3A") (pinfunction "IN3A_IN3A") (pintype "bidirectional"))
    )
    (net (code "106") (name "Net-(U$6-PadEXITCOIL0)") (class "Default")
      (node (ref "U$6") (pin "EXITCOIL0") (pinfunction "EXITCOIL0_EXITCOIL0") (pintype "bidirectional"))
      (node (ref "U6") (pin "IN1B") (pinfunction "IN1B_IN1B") (pintype "bidirectional"))
    )
    (net (code "107") (name "Net-(U$6-PadEXITCOIL1)") (class "Default")
      (node (ref "U$6") (pin "EXITCOIL1") (pinfunction "EXITCOIL1_EXITCOIL1") (pintype "bidirectional"))
      (node (ref "U6") (pin "IN0B") (pinfunction "IN0B_IN0B") (pintype "bidirectional"))
    )
    (net (code "108") (name "Net-(U$6-PadEXITCOIL2)") (class "Default")
      (node (ref "U$6") (pin "EXITCOIL2") (pinfunction "EXITCOIL2_EXITCOIL2") (pintype "bidirectional"))
      (node (ref "U6") (pin "IN2A") (pinfunction "IN2A_IN2A") (pintype "bidirectional"))
    )
    (net (code "109") (name "Net-(U$6-PadEXITCOIL3)") (class "Default")
      (node (ref "U$6") (pin "EXITCOIL3") (pinfunction "EXITCOIL3_EXITCOIL3") (pintype "bidirectional"))
      (node (ref "U6") (pin "IN3B") (pinfunction "IN3B_IN3B") (pintype "bidirectional"))
    )
    (net (code "110") (name "Net-(U$6-PadINCOIL0)") (class "Default")
      (node (ref "U$6") (pin "INCOIL0") (pinfunction "INCOIL0_INCOIL0") (pintype "bidirectional"))
      (node (ref "U6") (pin "IN1A") (pinfunction "IN1A_IN1A") (pintype "bidirectional"))
    )
    (net (code "111") (name "Net-(U$6-PadINCOIL1)") (class "Default")
      (node (ref "U$6") (pin "INCOIL1") (pinfunction "INCOIL1_INCOIL1") (pintype "bidirectional"))
      (node (ref "U6") (pin "IN0A") (pinfunction "IN0A_IN0A") (pintype "bidirectional"))
    )
    (net (code "112") (name "Net-(U$6-PadINCOIL2)") (class "Default")
      (node (ref "U$6") (pin "INCOIL2") (pinfunction "INCOIL2_INCOIL2") (pintype "bidirectional"))
      (node (ref "U6") (pin "IN2B") (pinfunction "IN2B_IN2B") (pintype "bidirectional"))
    )
    (net (code "113") (name "Net-(U$6-PadINCOIL3)") (class "Default")
      (node (ref "U$6") (pin "INCOIL3") (pinfunction "INCOIL3_INCOIL3") (pintype "bidirectional"))
      (node (ref "U6") (pin "IN3A") (pinfunction "IN3A_IN3A") (pintype "bidirectional"))
    )
    (net (code "114") (name "Net-(U$8-PadEXITCOIL0)") (class "Default")
      (node (ref "U$8") (pin "EXITCOIL0") (pinfunction "EXITCOIL0_EXITCOIL0") (pintype "bidirectional"))
      (node (ref "U8") (pin "IN1B") (pinfunction "IN1B_IN1B") (pintype "bidirectional"))
    )
    (net (code "115") (name "Net-(U$8-PadEXITCOIL1)") (class "Default")
      (node (ref "U$8") (pin "EXITCOIL1") (pinfunction "EXITCOIL1_EXITCOIL1") (pintype "bidirectional"))
      (node (ref "U8") (pin "IN0B") (pinfunction "IN0B_IN0B") (pintype "bidirectional"))
    )
    (net (code "116") (name "Net-(U$8-PadEXITCOIL2)") (class "Default")
      (node (ref "U$8") (pin "EXITCOIL2") (pinfunction "EXITCOIL2_EXITCOIL2") (pintype "bidirectional"))
      (node (ref "U8") (pin "IN2A") (pinfunction "IN2A_IN2A") (pintype "bidirectional"))
    )
    (net (code "117") (name "Net-(U$8-PadEXITCOIL3)") (class "Default")
      (node (ref "U$8") (pin "EXITCOIL3") (pinfunction "EXITCOIL3_EXITCOIL3") (pintype "bidirectional"))
      (node (ref "U8") (pin "IN3B") (pinfunction "IN3B_IN3B") (pintype "bidirectional"))
    )
    (net (code "118") (name "Net-(U$8-PadINCOIL0)") (class "Default")
      (node (ref "U$8") (pin "INCOIL0") (pinfunction "INCOIL0_INCOIL0") (pintype "bidirectional"))
      (node (ref "U8") (pin "IN1A") (pinfunction "IN1A_IN1A") (pintype "bidirectional"))
    )
    (net (code "119") (name "Net-(U$8-PadINCOIL1)") (class "Default")
      (node (ref "U$8") (pin "INCOIL1") (pinfunction "INCOIL1_INCOIL1") (pintype "bidirectional"))
      (node (ref "U8") (pin "IN0A") (pinfunction "IN0A_IN0A") (pintype "bidirectional"))
    )
    (net (code "120") (name "Net-(U$8-PadINCOIL2)") (class "Default")
      (node (ref "U$8") (pin "INCOIL2") (pinfunction "INCOIL2_INCOIL2") (pintype "bidirectional"))
      (node (ref "U8") (pin "IN2B") (pinfunction "IN2B_IN2B") (pintype "bidirectional"))
    )
    (net (code "121") (name "Net-(U$8-PadINCOIL3)") (class "Default")
      (node (ref "U$8") (pin "INCOIL3") (pinfunction "INCOIL3_INCOIL3") (pintype "bidirectional"))
      (node (ref "U8") (pin "IN3A") (pinfunction "IN3A_IN3A") (pintype "bidirectional"))
    )
    (net (code "122") (name "Net-(U$9-PadEXITCOIL0)") (class "Default")
      (node (ref "U$9") (pin "EXITCOIL0") (pinfunction "EXITCOIL0_EXITCOIL0") (pintype "bidirectional"))
      (node (ref "U9") (pin "IN1B") (pinfunction "IN1B_IN1B") (pintype "bidirectional"))
    )
    (net (code "123") (name "Net-(U$9-PadEXITCOIL1)") (class "Default")
      (node (ref "U$9") (pin "EXITCOIL1") (pinfunction "EXITCOIL1_EXITCOIL1") (pintype "bidirectional"))
      (node (ref "U9") (pin "IN0B") (pinfunction "IN0B_IN0B") (pintype "bidirectional"))
    )
    (net (code "124") (name "Net-(U$9-PadEXITCOIL2)") (class "Default")
      (node (ref "U$9") (pin "EXITCOIL2") (pinfunction "EXITCOIL2_EXITCOIL2") (pintype "bidirectional"))
      (node (ref "U9") (pin "IN2A") (pinfunction "IN2A_IN2A") (pintype "bidirectional"))
    )
    (net (code "125") (name "Net-(U$9-PadEXITCOIL3)") (class "Default")
      (node (ref "U$9") (pin "EXITCOIL3") (pinfunction "EXITCOIL3_EXITCOIL3") (pintype "bidirectional"))
      (node (ref "U9") (pin "IN3B") (pinfunction "IN3B_IN3B") (pintype "bidirectional"))
    )
    (net (code "126") (name "Net-(U$9-PadINCOIL0)") (class "Default")
      (node (ref "U$9") (pin "INCOIL0") (pinfunction "INCOIL0_INCOIL0") (pintype "bidirectional"))
      (node (ref "U9") (pin "IN1A") (pinfunction "IN1A_IN1A") (pintype "bidirectional"))
    )
    (net (code "127") (name "Net-(U$9-PadINCOIL1)") (class "Default")
      (node (ref "U$9") (pin "INCOIL1") (pinfunction "INCOIL1_INCOIL1") (pintype "bidirectional"))
      (node (ref "U9") (pin "IN0A") (pinfunction "IN0A_IN0A") (pintype "bidirectional"))
    )
    (net (code "128") (name "Net-(U$9-PadINCOIL2)") (class "Default")
      (node (ref "U$9") (pin "INCOIL2") (pinfunction "INCOIL2_INCOIL2") (pintype "bidirectional"))
      (node (ref "U9") (pin "IN2B") (pinfunction "IN2B_IN2B") (pintype "bidirectional"))
    )
    (net (code "129") (name "Net-(U$9-PadINCOIL3)") (class "Default")
      (node (ref "U$9") (pin "INCOIL3") (pinfunction "INCOIL3_INCOIL3") (pintype "bidirectional"))
      (node (ref "U9") (pin "IN3A") (pinfunction "IN3A_IN3A") (pintype "bidirectional"))
    )
    (net (code "130") (name "Net-(U$10-PadEXITCOIL0)") (class "Default")
      (node (ref "U$10") (pin "EXITCOIL0") (pinfunction "EXITCOIL0_EXITCOIL0") (pintype "bidirectional"))
      (node (ref "U10") (pin "IN1B") (pinfunction "IN1B_IN1B") (pintype "bidirectional"))
    )
    (net (code "131") (name "Net-(U$10-PadEXITCOIL1)") (class "Default")
      (node (ref "U$10") (pin "EXITCOIL1") (pinfunction "EXITCOIL1_EXITCOIL1") (pintype "bidirectional"))
      (node (ref "U10") (pin "IN0B") (pinfunction "IN0B_IN0B") (pintype "bidirectional"))
    )
    (net (code "132") (name "Net-(U$10-PadEXITCOIL2)") (class "Default")
      (node (ref "U$10") (pin "EXITCOIL2") (pinfunction "EXITCOIL2_EXITCOIL2") (pintype "bidirectional"))
      (node (ref "U10") (pin "IN2A") (pinfunction "IN2A_IN2A") (pintype "bidirectional"))
    )
    (net (code "133") (name "Net-(U$10-PadEXITCOIL3)") (class "Default")
      (node (ref "U$10") (pin "EXITCOIL3") (pinfunction "EXITCOIL3_EXITCOIL3") (pintype "bidirectional"))
      (node (ref "U10") (pin "IN3B") (pinfunction "IN3B_IN3B") (pintype "bidirectional"))
    )
    (net (code "134") (name "Net-(U$10-PadINCOIL0)") (class "Default")
      (node (ref "U$10") (pin "INCOIL0") (pinfunction "INCOIL0_INCOIL0") (pintype "bidirectional"))
      (node (ref "U10") (pin "IN1A") (pinfunction "IN1A_IN1A") (pintype "bidirectional"))
    )
    (net (code "135") (name "Net-(U$10-PadINCOIL1)") (class "Default")
      (node (ref "U$10") (pin "INCOIL1") (pinfunction "INCOIL1_INCOIL1") (pintype "bidirectional"))
      (node (ref "U10") (pin "IN0A") (pinfunction "IN0A_IN0A") (pintype "bidirectional"))
    )
    (net (code "136") (name "Net-(U$10-PadINCOIL2)") (class "Default")
      (node (ref "U$10") (pin "INCOIL2") (pinfunction "INCOIL2_INCOIL2") (pintype "bidirectional"))
      (node (ref "U10") (pin "IN2B") (pinfunction "IN2B_IN2B") (pintype "bidirectional"))
    )
    (net (code "137") (name "Net-(U$10-PadINCOIL3)") (class "Default")
      (node (ref "U$10") (pin "INCOIL3") (pinfunction "INCOIL3_INCOIL3") (pintype "bidirectional"))
      (node (ref "U10") (pin "IN3A") (pinfunction "IN3A_IN3A") (pintype "bidirectional"))
    )
    (net (code "138") (name "Net-(U$12-PadEXITCOIL0)") (class "Default")
      (node (ref "U$12") (pin "EXITCOIL0") (pinfunction "EXITCOIL0_EXITCOIL0") (pintype "bidirectional"))
      (node (ref "U12") (pin "IN1B") (pinfunction "IN1B_IN1B") (pintype "bidirectional"))
    )
    (net (code "139") (name "Net-(U$12-PadEXITCOIL1)") (class "Default")
      (node (ref "U$12") (pin "EXITCOIL1") (pinfunction "EXITCOIL1_EXITCOIL1") (pintype "bidirectional"))
      (node (ref "U12") (pin "IN0B") (pinfunction "IN0B_IN0B") (pintype "bidirectional"))
    )
    (net (code "140") (name "Net-(U$12-PadEXITCOIL2)") (class "Default")
      (node (ref "U$12") (pin "EXITCOIL2") (pinfunction "EXITCOIL2_EXITCOIL2") (pintype "bidirectional"))
      (node (ref "U12") (pin "IN2A") (pinfunction "IN2A_IN2A") (pintype "bidirectional"))
    )
    (net (code "141") (name "Net-(U$12-PadEXITCOIL3)") (class "Default")
      (node (ref "U$12") (pin "EXITCOIL3") (pinfunction "EXITCOIL3_EXITCOIL3") (pintype "bidirectional"))
      (node (ref "U12") (pin "IN3B") (pinfunction "IN3B_IN3B") (pintype "bidirectional"))
    )
    (net (code "142") (name "Net-(U$12-PadINCOIL0)") (class "Default")
      (node (ref "U$12") (pin "INCOIL0") (pinfunction "INCOIL0_INCOIL0") (pintype "bidirectional"))
      (node (ref "U12") (pin "IN1A") (pinfunction "IN1A_IN1A") (pintype "bidirectional"))
    )
    (net (code "143") (name "Net-(U$12-PadINCOIL1)") (class "Default")
      (node (ref "U$12") (pin "INCOIL1") (pinfunction "INCOIL1_INCOIL1") (pintype "bidirectional"))
      (node (ref "U12") (pin "IN0A") (pinfunction "IN0A_IN0A") (pintype "bidirectional"))
    )
    (net (code "144") (name "Net-(U$12-PadINCOIL2)") (class "Default")
      (node (ref "U$12") (pin "INCOIL2") (pinfunction "INCOIL2_INCOIL2") (pintype "bidirectional"))
      (node (ref "U12") (pin "IN2B") (pinfunction "IN2B_IN2B") (pintype "bidirectional"))
    )
    (net (code "145") (name "Net-(U$12-PadINCOIL3)") (class "Default")
      (node (ref "U$12") (pin "INCOIL3") (pinfunction "INCOIL3_INCOIL3") (pintype "bidirectional"))
      (node (ref "U12") (pin "IN3A") (pinfunction "IN3A_IN3A") (pintype "bidirectional"))
    )
    (net (code "146") (name "Net-(U$14-PadEXITCOIL0)") (class "Default")
      (node (ref "U$14") (pin "EXITCOIL0") (pinfunction "EXITCOIL0_EXITCOIL0") (pintype "bidirectional"))
      (node (ref "U14") (pin "IN1B") (pinfunction "IN1B_IN1B") (pintype "bidirectional"))
    )
    (net (code "147") (name "Net-(U$14-PadEXITCOIL1)") (class "Default")
      (node (ref "U$14") (pin "EXITCOIL1") (pinfunction "EXITCOIL1_EXITCOIL1") (pintype "bidirectional"))
      (node (ref "U14") (pin "IN0B") (pinfunction "IN0B_IN0B") (pintype "bidirectional"))
    )
    (net (code "148") (name "Net-(U$14-PadEXITCOIL2)") (class "Default")
      (node (ref "U$14") (pin "EXITCOIL2") (pinfunction "EXITCOIL2_EXITCOIL2") (pintype "bidirectional"))
      (node (ref "U14") (pin "IN2A") (pinfunction "IN2A_IN2A") (pintype "bidirectional"))
    )
    (net (code "149") (name "Net-(U$14-PadEXITCOIL3)") (class "Default")
      (node (ref "U$14") (pin "EXITCOIL3") (pinfunction "EXITCOIL3_EXITCOIL3") (pintype "bidirectional"))
      (node (ref "U14") (pin "IN3B") (pinfunction "IN3B_IN3B") (pintype "bidirectional"))
    )
    (net (code "150") (name "Net-(U$14-PadINCOIL0)") (class "Default")
      (node (ref "U$14") (pin "INCOIL0") (pinfunction "INCOIL0_INCOIL0") (pintype "bidirectional"))
      (node (ref "U14") (pin "IN1A") (pinfunction "IN1A_IN1A") (pintype "bidirectional"))
    )
    (net (code "151") (name "Net-(U$14-PadINCOIL1)") (class "Default")
      (node (ref "U$14") (pin "INCOIL1") (pinfunction "INCOIL1_INCOIL1") (pintype "bidirectional"))
      (node (ref "U14") (pin "IN0A") (pinfunction "IN0A_IN0A") (pintype "bidirectional"))
    )
    (net (code "152") (name "Net-(U$14-PadINCOIL2)") (class "Default")
      (node (ref "U$14") (pin "INCOIL2") (pinfunction "INCOIL2_INCOIL2") (pintype "bidirectional"))
      (node (ref "U14") (pin "IN2B") (pinfunction "IN2B_IN2B") (pintype "bidirectional"))
    )
    (net (code "153") (name "Net-(U$14-PadINCOIL3)") (class "Default")
      (node (ref "U$14") (pin "INCOIL3") (pinfunction "INCOIL3_INCOIL3") (pintype "bidirectional"))
      (node (ref "U14") (pin "IN3A") (pinfunction "IN3A_IN3A") (pintype "bidirectional"))
    )
    (net (code "154") (name "Net-(U$16-PadEXITCOIL0)") (class "Default")
      (node (ref "U$16") (pin "EXITCOIL0") (pinfunction "EXITCOIL0_EXITCOIL0") (pintype "bidirectional"))
      (node (ref "U16") (pin "IN1B") (pinfunction "IN1B_IN1B") (pintype "bidirectional"))
    )
    (net (code "155") (name "Net-(U$16-PadEXITCOIL1)") (class "Default")
      (node (ref "U$16") (pin "EXITCOIL1") (pinfunction "EXITCOIL1_EXITCOIL1") (pintype "bidirectional"))
      (node (ref "U16") (pin "IN0B") (pinfunction "IN0B_IN0B") (pintype "bidirectional"))
    )
    (net (code "156") (name "Net-(U$16-PadEXITCOIL2)") (class "Default")
      (node (ref "U$16") (pin "EXITCOIL2") (pinfunction "EXITCOIL2_EXITCOIL2") (pintype "bidirectional"))
      (node (ref "U16") (pin "IN2A") (pinfunction "IN2A_IN2A") (pintype "bidirectional"))
    )
    (net (code "157") (name "Net-(U$16-PadEXITCOIL3)") (class "Default")
      (node (ref "U$16") (pin "EXITCOIL3") (pinfunction "EXITCOIL3_EXITCOIL3") (pintype "bidirectional"))
      (node (ref "U16") (pin "IN3B") (pinfunction "IN3B_IN3B") (pintype "bidirectional"))
    )
    (net (code "158") (name "Net-(U$16-PadINCOIL0)") (class "Default")
      (node (ref "U$16") (pin "INCOIL0") (pinfunction "INCOIL0_INCOIL0") (pintype "bidirectional"))
      (node (ref "U16") (pin "IN1A") (pinfunction "IN1A_IN1A") (pintype "bidirectional"))
    )
    (net (code "159") (name "Net-(U$16-PadINCOIL1)") (class "Default")
      (node (ref "U$16") (pin "INCOIL1") (pinfunction "INCOIL1_INCOIL1") (pintype "bidirectional"))
      (node (ref "U16") (pin "IN0A") (pinfunction "IN0A_IN0A") (pintype "bidirectional"))
    )
    (net (code "160") (name "Net-(U$16-PadINCOIL2)") (class "Default")
      (node (ref "U$16") (pin "INCOIL2") (pinfunction "INCOIL2_INCOIL2") (pintype "bidirectional"))
      (node (ref "U16") (pin "IN2B") (pinfunction "IN2B_IN2B") (pintype "bidirectional"))
    )
    (net (code "161") (name "Net-(U$16-PadINCOIL3)") (class "Default")
      (node (ref "U$16") (pin "INCOIL3") (pinfunction "INCOIL3_INCOIL3") (pintype "bidirectional"))
      (node (ref "U16") (pin "IN3A") (pinfunction "IN3A_IN3A") (pintype "bidirectional"))
    )
    (net (code "162") (name "Net-(U$19-EXITCOIL2)") (class "Default")
      (node (ref "U$19") (pin "EXITCOIL2B") (pinfunction "EXITCOIL2_EXITCOIL2B") (pintype "bidirectional"))
      (node (ref "U19") (pin "IN2A") (pinfunction "IN2A_IN2A") (pintype "bidirectional"))
    )
    (net (code "163") (name "Net-(U$19-INCOIL2)") (class "Default")
      (node (ref "U$19") (pin "INCOIL2B") (pinfunction "INCOIL2_INCOIL2B") (pintype "bidirectional"))
      (node (ref "U19") (pin "IN2B") (pinfunction "IN2B_IN2B") (pintype "bidirectional"))
    )
    (net (code "164") (name "Net-(U$19-PadEXITCOIL0)") (class "Default")
      (node (ref "U$19") (pin "EXITCOIL0") (pinfunction "EXITCOIL0_EXITCOIL0") (pintype "bidirectional"))
      (node (ref "U19") (pin "IN1B") (pinfunction "IN1B_IN1B") (pintype "bidirectional"))
    )
    (net (code "165") (name "Net-(U$19-PadEXITCOIL1)") (class "Default")
      (node (ref "U$19") (pin "EXITCOIL1") (pinfunction "EXITCOIL1_EXITCOIL1") (pintype "bidirectional"))
      (node (ref "U19") (pin "IN0B") (pinfunction "IN0B_IN0B") (pintype "bidirectional"))
    )
    (net (code "166") (name "Net-(U$19-PadEXITCOIL3)") (class "Default")
      (node (ref "U$19") (pin "EXITCOIL3") (pinfunction "EXITCOIL3_EXITCOIL3") (pintype "bidirectional"))
      (node (ref "U19") (pin "IN3B") (pinfunction "IN3B_IN3B") (pintype "bidirectional"))
    )
    (net (code "167") (name "Net-(U$19-PadINCOIL0)") (class "Default")
      (node (ref "U$19") (pin "INCOIL0") (pinfunction "INCOIL0_INCOIL0") (pintype "bidirectional"))
      (node (ref "U19") (pin "IN1A") (pinfunction "IN1A_IN1A") (pintype "bidirectional"))
    )
    (net (code "168") (name "Net-(U$19-PadINCOIL1)") (class "Default")
      (node (ref "U$19") (pin "INCOIL1") (pinfunction "INCOIL1_INCOIL1") (pintype "bidirectional"))
      (node (ref "U19") (pin "IN0A") (pinfunction "IN0A_IN0A") (pintype "bidirectional"))
    )
    (net (code "169") (name "Net-(U$19-PadINCOIL3)") (class "Default")
      (node (ref "U$19") (pin "INCOIL3") (pinfunction "INCOIL3_INCOIL3") (pintype "bidirectional"))
      (node (ref "U19") (pin "IN3A") (pinfunction "IN3A_IN3A") (pintype "bidirectional"))
    )
    (net (code "170") (name "Net-(U$21-EXITCOIL2)") (class "Default")
      (node (ref "U$21") (pin "EXITCOIL2B") (pinfunction "EXITCOIL2_EXITCOIL2B") (pintype "bidirectional"))
      (node (ref "U21") (pin "IN2A") (pinfunction "IN2A_IN2A") (pintype "bidirectional"))
    )
    (net (code "171") (name "Net-(U$21-INCOIL2)") (class "Default")
      (node (ref "U$21") (pin "INCOIL2B") (pinfunction "INCOIL2_INCOIL2B") (pintype "bidirectional"))
      (node (ref "U21") (pin "IN2B") (pinfunction "IN2B_IN2B") (pintype "bidirectional"))
    )
    (net (code "172") (name "Net-(U$21-PadEXITCOIL0)") (class "Default")
      (node (ref "U$21") (pin "EXITCOIL0") (pinfunction "EXITCOIL0_EXITCOIL0") (pintype "bidirectional"))
      (node (ref "U21") (pin "IN1B") (pinfunction "IN1B_IN1B") (pintype "bidirectional"))
    )
    (net (code "173") (name "Net-(U$21-PadEXITCOIL1)") (class "Default")
      (node (ref "U$21") (pin "EXITCOIL1") (pinfunction "EXITCOIL1_EXITCOIL1") (pintype "bidirectional"))
      (node (ref "U21") (pin "IN0B") (pinfunction "IN0B_IN0B") (pintype "bidirectional"))
    )
    (net (code "174") (name "Net-(U$21-PadEXITCOIL3)") (class "Default")
      (node (ref "U$21") (pin "EXITCOIL3") (pinfunction "EXITCOIL3_EXITCOIL3") (pintype "bidirectional"))
      (node (ref "U21") (pin "IN3B") (pinfunction "IN3B_IN3B") (pintype "bidirectional"))
    )
    (net (code "175") (name "Net-(U$21-PadINCOIL0)") (class "Default")
      (node (ref "U$21") (pin "INCOIL0") (pinfunction "INCOIL0_INCOIL0") (pintype "bidirectional"))
      (node (ref "U21") (pin "IN1A") (pinfunction "IN1A_IN1A") (pintype "bidirectional"))
    )
    (net (code "176") (name "Net-(U$21-PadINCOIL1)") (class "Default")
      (node (ref "U$21") (pin "INCOIL1") (pinfunction "INCOIL1_INCOIL1") (pintype "bidirectional"))
      (node (ref "U21") (pin "IN0A") (pinfunction "IN0A_IN0A") (pintype "bidirectional"))
    )
    (net (code "177") (name "Net-(U$21-PadINCOIL3)") (class "Default")
      (node (ref "U$21") (pin "INCOIL3") (pinfunction "INCOIL3_INCOIL3") (pintype "bidirectional"))
      (node (ref "U21") (pin "IN3A") (pinfunction "IN3A_IN3A") (pintype "bidirectional"))
    )
    (net (code "178") (name "Net-(U$23-EXITCOIL2)") (class "Default")
      (node (ref "U$23") (pin "EXITCOIL2B") (pinfunction "EXITCOIL2_EXITCOIL2B") (pintype "bidirectional"))
      (node (ref "U23") (pin "IN2A") (pinfunction "IN2A_IN2A") (pintype "bidirectional"))
    )
    (net (code "179") (name "Net-(U$23-INCOIL2)") (class "Default")
      (node (ref "U$23") (pin "INCOIL2B") (pinfunction "INCOIL2_INCOIL2B") (pintype "bidirectional"))
      (node (ref "U23") (pin "IN2B") (pinfunction "IN2B_IN2B") (pintype "bidirectional"))
    )
    (net (code "180") (name "Net-(U$23-PadEXITCOIL0)") (class "Default")
      (node (ref "U$23") (pin "EXITCOIL0") (pinfunction "EXITCOIL0_EXITCOIL0") (pintype "bidirectional"))
      (node (ref "U23") (pin "IN1B") (pinfunction "IN1B_IN1B") (pintype "bidirectional"))
    )
    (net (code "181") (name "Net-(U$23-PadEXITCOIL1)") (class "Default")
      (node (ref "U$23") (pin "EXITCOIL1") (pinfunction "EXITCOIL1_EXITCOIL1") (pintype "bidirectional"))
      (node (ref "U23") (pin "IN0B") (pinfunction "IN0B_IN0B") (pintype "bidirectional"))
    )
    (net (code "182") (name "Net-(U$23-PadEXITCOIL3)") (class "Default")
      (node (ref "U$23") (pin "EXITCOIL3") (pinfunction "EXITCOIL3_EXITCOIL3") (pintype "bidirectional"))
      (node (ref "U23") (pin "IN3B") (pinfunction "IN3B_IN3B") (pintype "bidirectional"))
    )
    (net (code "183") (name "Net-(U$23-PadINCOIL0)") (class "Default")
      (node (ref "U$23") (pin "INCOIL0") (pinfunction "INCOIL0_INCOIL0") (pintype "bidirectional"))
      (node (ref "U23") (pin "IN1A") (pinfunction "IN1A_IN1A") (pintype "bidirectional"))
    )
    (net (code "184") (name "Net-(U$23-PadINCOIL1)") (class "Default")
      (node (ref "U$23") (pin "INCOIL1") (pinfunction "INCOIL1_INCOIL1") (pintype "bidirectional"))
      (node (ref "U23") (pin "IN0A") (pinfunction "IN0A_IN0A") (pintype "bidirectional"))
    )
    (net (code "185") (name "Net-(U$23-PadINCOIL3)") (class "Default")
      (node (ref "U$23") (pin "INCOIL3") (pinfunction "INCOIL3_INCOIL3") (pintype "bidirectional"))
      (node (ref "U23") (pin "IN3A") (pinfunction "IN3A_IN3A") (pintype "bidirectional"))
    )
    (net (code "186") (name "Net-(U$25-EXITCOIL2)") (class "Default")
      (node (ref "U$25") (pin "EXITCOIL2B") (pinfunction "EXITCOIL2_EXITCOIL2B") (pintype "bidirectional"))
      (node (ref "U25") (pin "IN2A") (pinfunction "IN2A_IN2A") (pintype "bidirectional"))
    )
    (net (code "187") (name "Net-(U$25-INCOIL2)") (class "Default")
      (node (ref "U$25") (pin "INCOIL2B") (pinfunction "INCOIL2_INCOIL2B") (pintype "bidirectional"))
      (node (ref "U25") (pin "IN2B") (pinfunction "IN2B_IN2B") (pintype "bidirectional"))
    )
    (net (code "188") (name "Net-(U$25-PadEXITCOIL0)") (class "Default")
      (node (ref "U$25") (pin "EXITCOIL0") (pinfunction "EXITCOIL0_EXITCOIL0") (pintype "bidirectional"))
      (node (ref "U25") (pin "IN1B") (pinfunction "IN1B_IN1B") (pintype "bidirectional"))
    )
    (net (code "189") (name "Net-(U$25-PadEXITCOIL1)") (class "Default")
      (node (ref "U$25") (pin "EXITCOIL1") (pinfunction "EXITCOIL1_EXITCOIL1") (pintype "bidirectional"))
      (node (ref "U25") (pin "IN0B") (pinfunction "IN0B_IN0B") (pintype "bidirectional"))
    )
    (net (code "190") (name "Net-(U$25-PadEXITCOIL3)") (class "Default")
      (node (ref "U$25") (pin "EXITCOIL3") (pinfunction "EXITCOIL3_EXITCOIL3") (pintype "bidirectional"))
      (node (ref "U25") (pin "IN3B") (pinfunction "IN3B_IN3B") (pintype "bidirectional"))
    )
    (net (code "191") (name "Net-(U$25-PadINCOIL0)") (class "Default")
      (node (ref "U$25") (pin "INCOIL0") (pinfunction "INCOIL0_INCOIL0") (pintype "bidirectional"))
      (node (ref "U25") (pin "IN1A") (pinfunction "IN1A_IN1A") (pintype "bidirectional"))
    )
    (net (code "192") (name "Net-(U$25-PadINCOIL1)") (class "Default")
      (node (ref "U$25") (pin "INCOIL1") (pinfunction "INCOIL1_INCOIL1") (pintype "bidirectional"))
      (node (ref "U25") (pin "IN0A") (pinfunction "IN0A_IN0A") (pintype "bidirectional"))
    )
    (net (code "193") (name "Net-(U$25-PadINCOIL3)") (class "Default")
      (node (ref "U$25") (pin "INCOIL3") (pinfunction "INCOIL3_INCOIL3") (pintype "bidirectional"))
      (node (ref "U25") (pin "IN3A") (pinfunction "IN3A_IN3A") (pintype "bidirectional"))
    )
    (net (code "194") (name "Net-(U$27-EXITCOIL2)") (class "Default")
      (node (ref "U$27") (pin "EXITCOIL2B") (pinfunction "EXITCOIL2_EXITCOIL2B") (pintype "bidirectional"))
      (node (ref "U27") (pin "IN2A") (pinfunction "IN2A_IN2A") (pintype "bidirectional"))
    )
    (net (code "195") (name "Net-(U$27-INCOIL2)") (class "Default")
      (node (ref "U$27") (pin "INCOIL2B") (pinfunction "INCOIL2_INCOIL2B") (pintype "bidirectional"))
      (node (ref "U27") (pin "IN2B") (pinfunction "IN2B_IN2B") (pintype "bidirectional"))
    )
    (net (code "196") (name "Net-(U$27-PadEXITCOIL0)") (class "Default")
      (node (ref "U$27") (pin "EXITCOIL0") (pinfunction "EXITCOIL0_EXITCOIL0") (pintype "bidirectional"))
      (node (ref "U27") (pin "IN1B") (pinfunction "IN1B_IN1B") (pintype "bidirectional"))
    )
    (net (code "197") (name "Net-(U$27-PadEXITCOIL1)") (class "Default")
      (node (ref "U$27") (pin "EXITCOIL1") (pinfunction "EXITCOIL1_EXITCOIL1") (pintype "bidirectional"))
      (node (ref "U27") (pin "IN0B") (pinfunction "IN0B_IN0B") (pintype "bidirectional"))
    )
    (net (code "198") (name "Net-(U$27-PadEXITCOIL3)") (class "Default")
      (node (ref "U$27") (pin "EXITCOIL3") (pinfunction "EXITCOIL3_EXITCOIL3") (pintype "bidirectional"))
      (node (ref "U27") (pin "IN3B") (pinfunction "IN3B_IN3B") (pintype "bidirectional"))
    )
    (net (code "199") (name "Net-(U$27-PadINCOIL0)") (class "Default")
      (node (ref "U$27") (pin "INCOIL0") (pinfunction "INCOIL0_INCOIL0") (pintype "bidirectional"))
      (node (ref "U27") (pin "IN1A") (pinfunction "IN1A_IN1A") (pintype "bidirectional"))
    )
    (net (code "200") (name "Net-(U$27-PadINCOIL1)") (class "Default")
      (node (ref "U$27") (pin "INCOIL1") (pinfunction "INCOIL1_INCOIL1") (pintype "bidirectional"))
      (node (ref "U27") (pin "IN0A") (pinfunction "IN0A_IN0A") (pintype "bidirectional"))
    )
    (net (code "201") (name "Net-(U$27-PadINCOIL3)") (class "Default")
      (node (ref "U$27") (pin "INCOIL3") (pinfunction "INCOIL3_INCOIL3") (pintype "bidirectional"))
      (node (ref "U27") (pin "IN3A") (pinfunction "IN3A_IN3A") (pintype "bidirectional"))
    )
    (net (code "202") (name "Net-(U$29-EXITCOIL2)") (class "Default")
      (node (ref "U$29") (pin "EXITCOIL2B") (pinfunction "EXITCOIL2_EXITCOIL2B") (pintype "bidirectional"))
      (node (ref "U29") (pin "IN2A") (pinfunction "IN2A_IN2A") (pintype "bidirectional"))
    )
    (net (code "203") (name "Net-(U$29-INCOIL2)") (class "Default")
      (node (ref "U$29") (pin "INCOIL2B") (pinfunction "INCOIL2_INCOIL2B") (pintype "bidirectional"))
      (node (ref "U29") (pin "IN2B") (pinfunction "IN2B_IN2B") (pintype "bidirectional"))
    )
    (net (code "204") (name "Net-(U$29-PadEXITCOIL0)") (class "Default")
      (node (ref "U$29") (pin "EXITCOIL0") (pinfunction "EXITCOIL0_EXITCOIL0") (pintype "bidirectional"))
      (node (ref "U29") (pin "IN1B") (pinfunction "IN1B_IN1B") (pintype "bidirectional"))
    )
    (net (code "205") (name "Net-(U$29-PadEXITCOIL1)") (class "Default")
      (node (ref "U$29") (pin "EXITCOIL1") (pinfunction "EXITCOIL1_EXITCOIL1") (pintype "bidirectional"))
      (node (ref "U29") (pin "IN0B") (pinfunction "IN0B_IN0B") (pintype "bidirectional"))
    )
    (net (code "206") (name "Net-(U$29-PadEXITCOIL3)") (class "Default")
      (node (ref "U$29") (pin "EXITCOIL3") (pinfunction "EXITCOIL3_EXITCOIL3") (pintype "bidirectional"))
      (node (ref "U29") (pin "IN3B") (pinfunction "IN3B_IN3B") (pintype "bidirectional"))
    )
    (net (code "207") (name "Net-(U$29-PadINCOIL0)") (class "Default")
      (node (ref "U$29") (pin "INCOIL0") (pinfunction "INCOIL0_INCOIL0") (pintype "bidirectional"))
      (node (ref "U29") (pin "IN1A") (pinfunction "IN1A_IN1A") (pintype "bidirectional"))
    )
    (net (code "208") (name "Net-(U$29-PadINCOIL1)") (class "Default")
      (node (ref "U$29") (pin "INCOIL1") (pinfunction "INCOIL1_INCOIL1") (pintype "bidirectional"))
      (node (ref "U29") (pin "IN0A") (pinfunction "IN0A_IN0A") (pintype "bidirectional"))
    )
    (net (code "209") (name "Net-(U$29-PadINCOIL3)") (class "Default")
      (node (ref "U$29") (pin "INCOIL3") (pinfunction "INCOIL3_INCOIL3") (pintype "bidirectional"))
      (node (ref "U29") (pin "IN3A") (pinfunction "IN3A_IN3A") (pintype "bidirectional"))
    )
    (net (code "210") (name "Net-(U$31-EXITCOIL2)") (class "Default")
      (node (ref "U$31") (pin "EXITCOIL2B") (pinfunction "EXITCOIL2_EXITCOIL2B") (pintype "bidirectional"))
      (node (ref "U31") (pin "IN2A") (pinfunction "IN2A_IN2A") (pintype "bidirectional"))
    )
    (net (code "211") (name "Net-(U$31-INCOIL2)") (class "Default")
      (node (ref "U$31") (pin "INCOIL2B") (pinfunction "INCOIL2_INCOIL2B") (pintype "bidirectional"))
      (node (ref "U31") (pin "IN2B") (pinfunction "IN2B_IN2B") (pintype "bidirectional"))
    )
    (net (code "212") (name "Net-(U$31-PadEXITCOIL0)") (class "Default")
      (node (ref "U$31") (pin "EXITCOIL0") (pinfunction "EXITCOIL0_EXITCOIL0") (pintype "bidirectional"))
      (node (ref "U31") (pin "IN1B") (pinfunction "IN1B_IN1B") (pintype "bidirectional"))
    )
    (net (code "213") (name "Net-(U$31-PadEXITCOIL1)") (class "Default")
      (node (ref "U$31") (pin "EXITCOIL1") (pinfunction "EXITCOIL1_EXITCOIL1") (pintype "bidirectional"))
      (node (ref "U31") (pin "IN0B") (pinfunction "IN0B_IN0B") (pintype "bidirectional"))
    )
    (net (code "214") (name "Net-(U$31-PadEXITCOIL3)") (class "Default")
      (node (ref "U$31") (pin "EXITCOIL3") (pinfunction "EXITCOIL3_EXITCOIL3") (pintype "bidirectional"))
      (node (ref "U31") (pin "IN3B") (pinfunction "IN3B_IN3B") (pintype "bidirectional"))
    )
    (net (code "215") (name "Net-(U$31-PadINCOIL0)") (class "Default")
      (node (ref "U$31") (pin "INCOIL0") (pinfunction "INCOIL0_INCOIL0") (pintype "bidirectional"))
      (node (ref "U31") (pin "IN1A") (pinfunction "IN1A_IN1A") (pintype "bidirectional"))
    )
    (net (code "216") (name "Net-(U$31-PadINCOIL1)") (class "Default")
      (node (ref "U$31") (pin "INCOIL1") (pinfunction "INCOIL1_INCOIL1") (pintype "bidirectional"))
      (node (ref "U31") (pin "IN0A") (pinfunction "IN0A_IN0A") (pintype "bidirectional"))
    )
    (net (code "217") (name "Net-(U$31-PadINCOIL3)") (class "Default")
      (node (ref "U$31") (pin "INCOIL3") (pinfunction "INCOIL3_INCOIL3") (pintype "bidirectional"))
      (node (ref "U31") (pin "IN3A") (pinfunction "IN3A_IN3A") (pintype "bidirectional"))
    )
    (net (code "218") (name "Net-(U$33-EXITCOIL2)") (class "Default")
      (node (ref "U$33") (pin "EXITCOIL2B") (pinfunction "EXITCOIL2_EXITCOIL2B") (pintype "bidirectional"))
      (node (ref "U33") (pin "IN2A") (pinfunction "IN2A_IN2A") (pintype "bidirectional"))
    )
    (net (code "219") (name "Net-(U$33-INCOIL2)") (class "Default")
      (node (ref "U$33") (pin "INCOIL2B") (pinfunction "INCOIL2_INCOIL2B") (pintype "bidirectional"))
      (node (ref "U33") (pin "IN2B") (pinfunction "IN2B_IN2B") (pintype "bidirectional"))
    )
    (net (code "220") (name "Net-(U$33-PadEXITCOIL0)") (class "Default")
      (node (ref "U$33") (pin "EXITCOIL0") (pinfunction "EXITCOIL0_EXITCOIL0") (pintype "bidirectional"))
      (node (ref "U33") (pin "IN1B") (pinfunction "IN1B_IN1B") (pintype "bidirectional"))
    )
    (net (code "221") (name "Net-(U$33-PadEXITCOIL1)") (class "Default")
      (node (ref "U$33") (pin "EXITCOIL1") (pinfunction "EXITCOIL1_EXITCOIL1") (pintype "bidirectional"))
      (node (ref "U33") (pin "IN0B") (pinfunction "IN0B_IN0B") (pintype "bidirectional"))
    )
    (net (code "222") (name "Net-(U$33-PadEXITCOIL3)") (class "Default")
      (node (ref "U$33") (pin "EXITCOIL3") (pinfunction "EXITCOIL3_EXITCOIL3") (pintype "bidirectional"))
      (node (ref "U33") (pin "IN3B") (pinfunction "IN3B_IN3B") (pintype "bidirectional"))
    )
    (net (code "223") (name "Net-(U$33-PadINCOIL0)") (class "Default")
      (node (ref "U$33") (pin "INCOIL0") (pinfunction "INCOIL0_INCOIL0") (pintype "bidirectional"))
      (node (ref "U33") (pin "IN1A") (pinfunction "IN1A_IN1A") (pintype "bidirectional"))
    )
    (net (code "224") (name "Net-(U$33-PadINCOIL1)") (class "Default")
      (node (ref "U$33") (pin "INCOIL1") (pinfunction "INCOIL1_INCOIL1") (pintype "bidirectional"))
      (node (ref "U33") (pin "IN0A") (pinfunction "IN0A_IN0A") (pintype "bidirectional"))
    )
    (net (code "225") (name "Net-(U$33-PadINCOIL3)") (class "Default")
      (node (ref "U$33") (pin "INCOIL3") (pinfunction "INCOIL3_INCOIL3") (pintype "bidirectional"))
      (node (ref "U33") (pin "IN3A") (pinfunction "IN3A_IN3A") (pintype "bidirectional"))
    )
    (net (code "226") (name "Net-(U$35-EXITCOIL2)") (class "Default")
      (node (ref "U$35") (pin "EXITCOIL2B") (pinfunction "EXITCOIL2_EXITCOIL2B") (pintype "bidirectional"))
      (node (ref "U35") (pin "IN2A") (pinfunction "IN2A_IN2A") (pintype "bidirectional"))
    )
    (net (code "227") (name "Net-(U$35-INCOIL2)") (class "Default")
      (node (ref "U$35") (pin "INCOIL2B") (pinfunction "INCOIL2_INCOIL2B") (pintype "bidirectional"))
      (node (ref "U35") (pin "IN2B") (pinfunction "IN2B_IN2B") (pintype "bidirectional"))
    )
    (net (code "228") (name "Net-(U$35-PadEXITCOIL0)") (class "Default")
      (node (ref "U$35") (pin "EXITCOIL0") (pinfunction "EXITCOIL0_EXITCOIL0") (pintype "bidirectional"))
      (node (ref "U35") (pin "IN1B") (pinfunction "IN1B_IN1B") (pintype "bidirectional"))
    )
    (net (code "229") (name "Net-(U$35-PadEXITCOIL1)") (class "Default")
      (node (ref "U$35") (pin "EXITCOIL1") (pinfunction "EXITCOIL1_EXITCOIL1") (pintype "bidirectional"))
      (node (ref "U35") (pin "IN0B") (pinfunction "IN0B_IN0B") (pintype "bidirectional"))
    )
    (net (code "230") (name "Net-(U$35-PadEXITCOIL3)") (class "Default")
      (node (ref "U$35") (pin "EXITCOIL3") (pinfunction "EXITCOIL3_EXITCOIL3") (pintype "bidirectional"))
      (node (ref "U35") (pin "IN3B") (pinfunction "IN3B_IN3B") (pintype "bidirectional"))
    )
    (net (code "231") (name "Net-(U$35-PadINCOIL0)") (class "Default")
      (node (ref "U$35") (pin "INCOIL0") (pinfunction "INCOIL0_INCOIL0") (pintype "bidirectional"))
      (node (ref "U35") (pin "IN1A") (pinfunction "IN1A_IN1A") (pintype "bidirectional"))
    )
    (net (code "232") (name "Net-(U$35-PadINCOIL1)") (class "Default")
      (node (ref "U$35") (pin "INCOIL1") (pinfunction "INCOIL1_INCOIL1") (pintype "bidirectional"))
      (node (ref "U35") (pin "IN0A") (pinfunction "IN0A_IN0A") (pintype "bidirectional"))
    )
    (net (code "233") (name "Net-(U$35-PadINCOIL3)") (class "Default")
      (node (ref "U$35") (pin "INCOIL3") (pinfunction "INCOIL3_INCOIL3") (pintype "bidirectional"))
      (node (ref "U35") (pin "IN3A") (pinfunction "IN3A_IN3A") (pintype "bidirectional"))
    )
    (net (code "234") (name "Net-(U$37-EXITCOIL2)") (class "Default")
      (node (ref "U$37") (pin "EXITCOIL2B") (pinfunction "EXITCOIL2_EXITCOIL2B") (pintype "bidirectional"))
      (node (ref "U37") (pin "IN2A") (pinfunction "IN2A_IN2A") (pintype "bidirectional"))
    )
    (net (code "235") (name "Net-(U$37-INCOIL2)") (class "Default")
      (node (ref "U$37") (pin "INCOIL2B") (pinfunction "INCOIL2_INCOIL2B") (pintype "bidirectional"))
      (node (ref "U37") (pin "IN2B") (pinfunction "IN2B_IN2B") (pintype "bidirectional"))
    )
    (net (code "236") (name "Net-(U$37-PadEXITCOIL0)") (class "Default")
      (node (ref "U$37") (pin "EXITCOIL0") (pinfunction "EXITCOIL0_EXITCOIL0") (pintype "bidirectional"))
      (node (ref "U37") (pin "IN1B") (pinfunction "IN1B_IN1B") (pintype "bidirectional"))
    )
    (net (code "237") (name "Net-(U$37-PadEXITCOIL1)") (class "Default")
      (node (ref "U$37") (pin "EXITCOIL1") (pinfunction "EXITCOIL1_EXITCOIL1") (pintype "bidirectional"))
      (node (ref "U37") (pin "IN0B") (pinfunction "IN0B_IN0B") (pintype "bidirectional"))
    )
    (net (code "238") (name "Net-(U$37-PadEXITCOIL3)") (class "Default")
      (node (ref "U$37") (pin "EXITCOIL3") (pinfunction "EXITCOIL3_EXITCOIL3") (pintype "bidirectional"))
      (node (ref "U37") (pin "IN3B") (pinfunction "IN3B_IN3B") (pintype "bidirectional"))
    )
    (net (code "239") (name "Net-(U$37-PadINCOIL0)") (class "Default")
      (node (ref "U$37") (pin "INCOIL0") (pinfunction "INCOIL0_INCOIL0") (pintype "bidirectional"))
      (node (ref "U37") (pin "IN1A") (pinfunction "IN1A_IN1A") (pintype "bidirectional"))
    )
    (net (code "240") (name "Net-(U$37-PadINCOIL1)") (class "Default")
      (node (ref "U$37") (pin "INCOIL1") (pinfunction "INCOIL1_INCOIL1") (pintype "bidirectional"))
      (node (ref "U37") (pin "IN0A") (pinfunction "IN0A_IN0A") (pintype "bidirectional"))
    )
    (net (code "241") (name "Net-(U$37-PadINCOIL3)") (class "Default")
      (node (ref "U$37") (pin "INCOIL3") (pinfunction "INCOIL3_INCOIL3") (pintype "bidirectional"))
      (node (ref "U37") (pin "IN3A") (pinfunction "IN3A_IN3A") (pintype "bidirectional"))
    )
    (net (code "242") (name "VDD") (class "Default")
      (node (ref "C10") (pin "1") (pinfunction "1_1") (pintype "passive"))
      (node (ref "C12") (pin "1") (pinfunction "1_1") (pintype "passive"))
      (node (ref "C14") (pin "1") (pinfunction "1_1") (pintype "passive"))
      (node (ref "C16") (pin "1") (pinfunction "1_1") (pintype "passive"))
      (node (ref "C19") (pin "1") (pinfunction "1_1") (pintype "passive"))
      (node (ref "C2") (pin "1") (pinfunction "1_1") (pintype "passive"))
      (node (ref "C21") (pin "1") (pinfunction "1_1") (pintype "passive"))
      (node (ref "C23") (pin "1") (pinfunction "1_1") (pintype "passive"))
      (node (ref "C25") (pin "1") (pinfunction "1_1") (pintype "passive"))
      (node (ref "C27") (pin "1") (pinfunction "1_1") (pintype "passive"))
      (node (ref "C29") (pin "1") (pinfunction "1_1") (pintype "passive"))
      (node (ref "C31") (pin "1") (pinfunction "1_1") (pintype "passive"))
      (node (ref "C33") (pin "1") (pinfunction "1_1") (pintype "passive"))
      (node (ref "C35") (pin "1") (pinfunction "1_1") (pintype "passive"))
      (node (ref "C37") (pin "1") (pinfunction "1_1") (pintype "passive"))
      (node (ref "C4") (pin "1") (pinfunction "1_1") (pintype "passive"))
      (node (ref "C5") (pin "1") (pinfunction "1_1") (pintype "passive"))
      (node (ref "C6") (pin "1") (pinfunction "1_1") (pintype "passive"))
      (node (ref "C8") (pin "1") (pinfunction "1_1") (pintype "passive"))
      (node (ref "C9") (pin "1") (pinfunction "1_1") (pintype "passive"))
      (node (ref "PAD100") (pin "1") (pinfunction "P_1") (pintype "passive"))
      (node (ref "PAD105") (pin "1") (pinfunction "P_1") (pintype "passive"))
      (node (ref "PAD118") (pin "1") (pinfunction "P_1") (pintype "passive"))
      (node (ref "PAD123") (pin "1") (pinfunction "P_1") (pintype "passive"))
      (node (ref "PAD136") (pin "1") (pinfunction "P_1") (pintype "passive"))
      (node (ref "PAD141") (pin "1") (pinfunction "P_1") (pintype "passive"))
      (node (ref "PAD15") (pin "1") (pinfunction "P_1") (pintype "passive"))
      (node (ref "PAD165") (pin "1") (pinfunction "P_1") (pintype "passive"))
      (node (ref "PAD170") (pin "1") (pinfunction "P_1") (pintype "passive"))
      (node (ref "PAD185") (pin "1") (pinfunction "P_1") (pintype "passive"))
      (node (ref "PAD190") (pin "1") (pinfunction "P_1") (pintype "passive"))
      (node (ref "PAD205") (pin "1") (pinfunction "P_1") (pintype "passive"))
      (node (ref "PAD210") (pin "1") (pinfunction "P_1") (pintype "passive"))
      (node (ref "PAD225") (pin "1") (pinfunction "P_1") (pintype "passive"))
      (node (ref "PAD230") (pin "1") (pinfunction "P_1") (pintype "passive"))
      (node (ref "PAD245") (pin "1") (pinfunction "P_1") (pintype "passive"))
      (node (ref "PAD250") (pin "1") (pinfunction "P_1") (pintype "passive"))
      (node (ref "PAD265") (pin "1") (pinfunction "P_1") (pintype "passive"))
      (node (ref "PAD270") (pin "1") (pinfunction "P_1") (pintype "passive"))
      (node (ref "PAD28") (pin "1") (pinfunction "P_1") (pintype "passive"))
      (node (ref "PAD285") (pin "1") (pinfunction "P_1") (pintype "passive"))
      (node (ref "PAD290") (pin "1") (pinfunction "P_1") (pintype "passive"))
      (node (ref "PAD305") (pin "1") (pinfunction "P_1") (pintype "passive"))
      (node (ref "PAD310") (pin "1") (pinfunction "P_1") (pintype "passive"))
      (node (ref "PAD325") (pin "1") (pinfunction "P_1") (pintype "passive"))
      (node (ref "PAD33") (pin "1") (pinfunction "P_1") (pintype "passive"))
      (node (ref "PAD330") (pin "1") (pinfunction "P_1") (pintype "passive"))
      (node (ref "PAD345") (pin "1") (pinfunction "P_1") (pintype "passive"))
      (node (ref "PAD350") (pin "1") (pinfunction "P_1") (pintype "passive"))
      (node (ref "PAD37") (pin "1") (pinfunction "P_1") (pintype "passive"))
      (node (ref "PAD42") (pin "1") (pinfunction "P_1") (pintype "passive"))
      (node (ref "PAD46") (pin "1") (pinfunction "P_1") (pintype "passive"))
      (node (ref "PAD51") (pin "1") (pinfunction "P_1") (pintype "passive"))
      (node (ref "PAD64") (pin "1") (pinfunction "P_1") (pintype "passive"))
      (node (ref "PAD69") (pin "1") (pinfunction "P_1") (pintype "passive"))
      (node (ref "PAD73") (pin "1") (pinfunction "P_1") (pintype "passive"))
      (node (ref "PAD78") (pin "1") (pinfunction "P_1") (pintype "passive"))
      (node (ref "PAD8") (pin "1") (pinfunction "P_1") (pintype "passive"))
      (node (ref "PAD82") (pin "1") (pinfunction "P_1") (pintype "passive"))
      (node (ref "PAD87") (pin "1") (pinfunction "P_1") (pintype "passive"))
      (node (ref "R105") (pin "2") (pinfunction "2_2") (pintype "passive"))
      (node (ref "R106") (pin "2") (pinfunction "2_2") (pintype "passive"))
      (node (ref "R107") (pin "2") (pinfunction "2_2") (pintype "passive"))
      (node (ref "R113") (pin "2") (pinfunction "2_2") (pintype "passive"))
      (node (ref "R114") (pin "2") (pinfunction "2_2") (pintype "passive"))
      (node (ref "R115") (pin "2") (pinfunction "2_2") (pintype "passive"))
      (node (ref "R121") (pin "2") (pinfunction "2_2") (pintype "passive"))
      (node (ref "R122") (pin "2") (pinfunction "2_2") (pintype "passive"))
      (node (ref "R123") (pin "2") (pinfunction "2_2") (pintype "passive"))
      (node (ref "R129") (pin "2") (pinfunction "2_2") (pintype "passive"))
      (node (ref "R13") (pin "2") (pinfunction "2_2") (pintype "passive"))
      (node (ref "R130") (pin "2") (pinfunction "2_2") (pintype "passive"))
      (node (ref "R131") (pin "2") (pinfunction "2_2") (pintype "passive"))
      (node (ref "R137") (pin "2") (pinfunction "2_2") (pintype "passive"))
      (node (ref "R138") (pin "2") (pinfunction "2_2") (pintype "passive"))
      (node (ref "R139") (pin "2") (pinfunction "2_2") (pintype "passive"))
      (node (ref "R14") (pin "2") (pinfunction "2_2") (pintype "passive"))
      (node (ref "R145") (pin "2") (pinfunction "2_2") (pintype "passive"))
      (node (ref "R146") (pin "2") (pinfunction "2_2") (pintype "passive"))
      (node (ref "R147") (pin "2") (pinfunction "2_2") (pintype "passive"))
      (node (ref "R15") (pin "2") (pinfunction "2_2") (pintype "passive"))
      (node (ref "R17") (pin "2") (pinfunction "2_2") (pintype "passive"))
      (node (ref "R18") (pin "2") (pinfunction "2_2") (pintype "passive"))
      (node (ref "R19") (pin "2") (pinfunction "2_2") (pintype "passive"))
      (node (ref "R21") (pin "2") (pinfunction "2_2") (pintype "passive"))
      (node (ref "R22") (pin "2") (pinfunction "2_2") (pintype "passive"))
      (node (ref "R23") (pin "2") (pinfunction "2_2") (pintype "passive"))
      (node (ref "R29") (pin "2") (pinfunction "2_2") (pintype "passive"))
      (node (ref "R30") (pin "2") (pinfunction "2_2") (pintype "passive"))
      (node (ref "R31") (pin "2") (pinfunction "2_2") (pintype "passive"))
      (node (ref "R33") (pin "2") (pinfunction "2_2") (pintype "passive"))
      (node (ref "R34") (pin "2") (pinfunction "2_2") (pintype "passive"))
      (node (ref "R35") (pin "2") (pinfunction "2_2") (pintype "passive"))
      (node (ref "R37") (pin "2") (pinfunction "2_2") (pintype "passive"))
      (node (ref "R38") (pin "2") (pinfunction "2_2") (pintype "passive"))
      (node (ref "R39") (pin "2") (pinfunction "2_2") (pintype "passive"))
      (node (ref "R45") (pin "2") (pinfunction "2_2") (pintype "passive"))
      (node (ref "R46") (pin "2") (pinfunction "2_2") (pintype "passive"))
      (node (ref "R47") (pin "2") (pinfunction "2_2") (pintype "passive"))
      (node (ref "R5") (pin "2") (pinfunction "2_2") (pintype "passive"))
      (node (ref "R53") (pin "2") (pinfunction "2_2") (pintype "passive"))
      (node (ref "R54") (pin "2") (pinfunction "2_2") (pintype "passive"))
      (node (ref "R55") (pin "2") (pinfunction "2_2") (pintype "passive"))
      (node (ref "R6") (pin "2") (pinfunction "2_2") (pintype "passive"))
      (node (ref "R61") (pin "2") (pinfunction "2_2") (pintype "passive"))
      (node (ref "R62") (pin "2") (pinfunction "2_2") (pintype "passive"))
      (node (ref "R63") (pin "2") (pinfunction "2_2") (pintype "passive"))
      (node (ref "R7") (pin "2") (pinfunction "2_2") (pintype "passive"))
      (node (ref "R73") (pin "2") (pinfunction "2_2") (pintype "passive"))
      (node (ref "R74") (pin "2") (pinfunction "2_2") (pintype "passive"))
      (node (ref "R75") (pin "2") (pinfunction "2_2") (pintype "passive"))
      (node (ref "R81") (pin "2") (pinfunction "2_2") (pintype "passive"))
      (node (ref "R82") (pin "2") (pinfunction "2_2") (pintype "passive"))
      (node (ref "R83") (pin "2") (pinfunction "2_2") (pintype "passive"))
      (node (ref "R89") (pin "2") (pinfunction "2_2") (pintype "passive"))
      (node (ref "R90") (pin "2") (pinfunction "2_2") (pintype "passive"))
      (node (ref "R91") (pin "2") (pinfunction "2_2") (pintype "passive"))
      (node (ref "R97") (pin "2") (pinfunction "2_2") (pintype "passive"))
      (node (ref "R98") (pin "2") (pinfunction "2_2") (pintype "passive"))
      (node (ref "R99") (pin "2") (pinfunction "2_2") (pintype "passive"))
      (node (ref "U10") (pin "VDD") (pinfunction "VDD_VDD") (pintype "bidirectional"))
      (node (ref "U12") (pin "VDD") (pinfunction "VDD_VDD") (pintype "bidirectional"))
      (node (ref "U14") (pin "VDD") (pinfunction "VDD_VDD") (pintype "bidirectional"))
      (node (ref "U16") (pin "VDD") (pinfunction "VDD_VDD") (pintype "bidirectional"))
      (node (ref "U19") (pin "VDD") (pinfunction "VDD_VDD") (pintype "bidirectional"))
      (node (ref "U2") (pin "VDD") (pinfunction "VDD_VDD") (pintype "bidirectional"))
      (node (ref "U21") (pin "VDD") (pinfunction "VDD_VDD") (pintype "bidirectional"))
      (node (ref "U23") (pin "VDD") (pinfunction "VDD_VDD") (pintype "bidirectional"))
      (node (ref "U25") (pin "VDD") (pinfunction "VDD_VDD") (pintype "bidirectional"))
      (node (ref "U27") (pin "VDD") (pinfunction "VDD_VDD") (pintype "bidirectional"))
      (node (ref "U29") (pin "VDD") (pinfunction "VDD_VDD") (pintype "bidirectional"))
      (node (ref "U31") (pin "VDD") (pinfunction "VDD_VDD") (pintype "bidirectional"))
      (node (ref "U33") (pin "VDD") (pinfunction "VDD_VDD") (pintype "bidirectional"))
      (node (ref "U35") (pin "VDD") (pinfunction "VDD_VDD") (pintype "bidirectional"))
      (node (ref "U37") (pin "VDD") (pinfunction "VDD_VDD") (pintype "bidirectional"))
      (node (ref "U4") (pin "VDD") (pinfunction "VDD_VDD") (pintype "bidirectional"))
      (node (ref "U5") (pin "VDD") (pinfunction "VDD_VDD") (pintype "bidirectional"))
      (node (ref "U6") (pin "VDD") (pinfunction "VDD_VDD") (pintype "bidirectional"))
      (node (ref "U8") (pin "VDD") (pinfunction "VDD_VDD") (pintype "bidirectional"))
      (node (ref "U9") (pin "VDD") (pinfunction "VDD_VDD") (pintype "bidirectional"))
    )
    (net (code "243") (name "unconnected-(U$1-PadINT1_INT2_COIL0)") (class "Default")
      (node (ref "U$1") (pin "INT1_INT2_COIL0") (pinfunction "INT1_INT2_COIL0_INT1_INT2_COIL0") (pintype "bidirectional"))
    )
    (net (code "244") (name "unconnected-(U$1-PadINT1_INT2_COIL1)") (class "Default")
      (node (ref "U$1") (pin "INT1_INT2_COIL1") (pinfunction "INT1_INT2_COIL1_INT1_INT2_COIL1") (pintype "bidirectional"))
    )
    (net (code "245") (name "unconnected-(U$1-PadINT1_INT2_COIL2)") (class "Default")
      (node (ref "U$1") (pin "INT1_INT2_COIL2") (pinfunction "INT1_INT2_COIL2_INT1_INT2_COIL2") (pintype "bidirectional"))
    )
    (net (code "246") (name "unconnected-(U$1-PadINT1_INT2_COIL3)") (class "Default")
      (node (ref "U$1") (pin "INT1_INT2_COIL3") (pinfunction "INT1_INT2_COIL3_INT1_INT2_COIL3") (pintype "bidirectional"))
    )
    (net (code "247") (name "unconnected-(U$1-PadTOP_INT1_COIL0)") (class "Default")
      (node (ref "U$1") (pin "TOP_INT1_COIL0") (pinfunction "TOP_INT1_COIL0_TOP_INT1_COIL0") (pintype "bidirectional"))
    )
    (net (code "248") (name "unconnected-(U$1-PadTOP_INT1_COIL1)") (class "Default")
      (node (ref "U$1") (pin "TOP_INT1_COIL1") (pinfunction "TOP_INT1_COIL1_TOP_INT1_COIL1") (pintype "bidirectional"))
    )
    (net (code "249") (name "unconnected-(U$1-PadTOP_INT1_COIL2)") (class "Default")
      (node (ref "U$1") (pin "TOP_INT1_COIL2") (pinfunction "TOP_INT1_COIL2_TOP_INT1_COIL2") (pintype "bidirectional"))
    )
    (net (code "250") (name "unconnected-(U$1-PadTOP_INT1_COIL3)") (class "Default")
      (node (ref "U$1") (pin "TOP_INT1_COIL3") (pinfunction "TOP_INT1_COIL3_TOP_INT1_COIL3") (pintype "bidirectional"))
    )
    (net (code "251") (name "unconnected-(U$4-PadINT1_INT2_COIL0)") (class "Default")
      (node (ref "U$4") (pin "INT1_INT2_COIL0") (pinfunction "INT1_INT2_COIL0_INT1_INT2_COIL0") (pintype "bidirectional"))
    )
    (net (code "252") (name "unconnected-(U$4-PadINT1_INT2_COIL1)") (class "Default")
      (node (ref "U$4") (pin "INT1_INT2_COIL1") (pinfunction "INT1_INT2_COIL1_INT1_INT2_COIL1") (pintype "bidirectional"))
    )
    (net (code "253") (name "unconnected-(U$4-PadINT1_INT2_COIL2)") (class "Default")
      (node (ref "U$4") (pin "INT1_INT2_COIL2") (pinfunction "INT1_INT2_COIL2_INT1_INT2_COIL2") (pintype "bidirectional"))
    )
    (net (code "254") (name "unconnected-(U$4-PadINT1_INT2_COIL3)") (class "Default")
      (node (ref "U$4") (pin "INT1_INT2_COIL3") (pinfunction "INT1_INT2_COIL3_INT1_INT2_COIL3") (pintype "bidirectional"))
    )
    (net (code "255") (name "unconnected-(U$4-PadTOP_INT1_COIL0)") (class "Default")
      (node (ref "U$4") (pin "TOP_INT1_COIL0") (pinfunction "TOP_INT1_COIL0_TOP_INT1_COIL0") (pintype "bidirectional"))
    )
    (net (code "256") (name "unconnected-(U$4-PadTOP_INT1_COIL1)") (class "Default")
      (node (ref "U$4") (pin "TOP_INT1_COIL1") (pinfunction "TOP_INT1_COIL1_TOP_INT1_COIL1") (pintype "bidirectional"))
    )
    (net (code "257") (name "unconnected-(U$4-PadTOP_INT1_COIL2)") (class "Default")
      (node (ref "U$4") (pin "TOP_INT1_COIL2") (pinfunction "TOP_INT1_COIL2_TOP_INT1_COIL2") (pintype "bidirectional"))
    )
    (net (code "258") (name "unconnected-(U$4-PadTOP_INT1_COIL3)") (class "Default")
      (node (ref "U$4") (pin "TOP_INT1_COIL3") (pinfunction "TOP_INT1_COIL3_TOP_INT1_COIL3") (pintype "bidirectional"))
    )
    (net (code "259") (name "unconnected-(U$5-PadINT1_INT2_COIL0)") (class "Default")
      (node (ref "U$5") (pin "INT1_INT2_COIL0") (pinfunction "INT1_INT2_COIL0_INT1_INT2_COIL0") (pintype "bidirectional"))
    )
    (net (code "260") (name "unconnected-(U$5-PadINT1_INT2_COIL1)") (class "Default")
      (node (ref "U$5") (pin "INT1_INT2_COIL1") (pinfunction "INT1_INT2_COIL1_INT1_INT2_COIL1") (pintype "bidirectional"))
    )
    (net (code "261") (name "unconnected-(U$5-PadINT1_INT2_COIL2)") (class "Default")
      (node (ref "U$5") (pin "INT1_INT2_COIL2") (pinfunction "INT1_INT2_COIL2_INT1_INT2_COIL2") (pintype "bidirectional"))
    )
    (net (code "262") (name "unconnected-(U$5-PadINT1_INT2_COIL3)") (class "Default")
      (node (ref "U$5") (pin "INT1_INT2_COIL3") (pinfunction "INT1_INT2_COIL3_INT1_INT2_COIL3") (pintype "bidirectional"))
    )
    (net (code "263") (name "unconnected-(U$5-PadTOP_INT1_COIL0)") (class "Default")
      (node (ref "U$5") (pin "TOP_INT1_COIL0") (pinfunction "TOP_INT1_COIL0_TOP_INT1_COIL0") (pintype "bidirectional"))
    )
    (net (code "264") (name "unconnected-(U$5-PadTOP_INT1_COIL1)") (class "Default")
      (node (ref "U$5") (pin "TOP_INT1_COIL1") (pinfunction "TOP_INT1_COIL1_TOP_INT1_COIL1") (pintype "bidirectional"))
    )
    (net (code "265") (name "unconnected-(U$5-PadTOP_INT1_COIL2)") (class "Default")
      (node (ref "U$5") (pin "TOP_INT1_COIL2") (pinfunction "TOP_INT1_COIL2_TOP_INT1_COIL2") (pintype "bidirectional"))
    )
    (net (code "266") (name "unconnected-(U$5-PadTOP_INT1_COIL3)") (class "Default")
      (node (ref "U$5") (pin "TOP_INT1_COIL3") (pinfunction "TOP_INT1_COIL3_TOP_INT1_COIL3") (pintype "bidirectional"))
    )
    (net (code "267") (name "unconnected-(U$6-PadINT1_INT2_COIL0)") (class "Default")
      (node (ref "U$6") (pin "INT1_INT2_COIL0") (pinfunction "INT1_INT2_COIL0_INT1_INT2_COIL0") (pintype "bidirectional"))
    )
    (net (code "268") (name "unconnected-(U$6-PadINT1_INT2_COIL1)") (class "Default")
      (node (ref "U$6") (pin "INT1_INT2_COIL1") (pinfunction "INT1_INT2_COIL1_INT1_INT2_COIL1") (pintype "bidirectional"))
    )
    (net (code "269") (name "unconnected-(U$6-PadINT1_INT2_COIL2)") (class "Default")
      (node (ref "U$6") (pin "INT1_INT2_COIL2") (pinfunction "INT1_INT2_COIL2_INT1_INT2_COIL2") (pintype "bidirectional"))
    )
    (net (code "270") (name "unconnected-(U$6-PadINT1_INT2_COIL3)") (class "Default")
      (node (ref "U$6") (pin "INT1_INT2_COIL3") (pinfunction "INT1_INT2_COIL3_INT1_INT2_COIL3") (pintype "bidirectional"))
    )
    (net (code "271") (name "unconnected-(U$6-PadTOP_INT1_COIL0)") (class "Default")
      (node (ref "U$6") (pin "TOP_INT1_COIL0") (pinfunction "TOP_INT1_COIL0_TOP_INT1_COIL0") (pintype "bidirectional"))
    )
    (net (code "272") (name "unconnected-(U$6-PadTOP_INT1_COIL1)") (class "Default")
      (node (ref "U$6") (pin "TOP_INT1_COIL1") (pinfunction "TOP_INT1_COIL1_TOP_INT1_COIL1") (pintype "bidirectional"))
    )
    (net (code "273") (name "unconnected-(U$6-PadTOP_INT1_COIL2)") (class "Default")
      (node (ref "U$6") (pin "TOP_INT1_COIL2") (pinfunction "TOP_INT1_COIL2_TOP_INT1_COIL2") (pintype "bidirectional"))
    )
    (net (code "274") (name "unconnected-(U$6-PadTOP_INT1_COIL3)") (class "Default")
      (node (ref "U$6") (pin "TOP_INT1_COIL3") (pinfunction "TOP_INT1_COIL3_TOP_INT1_COIL3") (pintype "bidirectional"))
    )
    (net (code "275") (name "unconnected-(U$8-PadINT1_INT2_COIL0)") (class "Default")
      (node (ref "U$8") (pin "INT1_INT2_COIL0") (pinfunction "INT1_INT2_COIL0_INT1_INT2_COIL0") (pintype "bidirectional"))
    )
    (net (code "276") (name "unconnected-(U$8-PadINT1_INT2_COIL1)") (class "Default")
      (node (ref "U$8") (pin "INT1_INT2_COIL1") (pinfunction "INT1_INT2_COIL1_INT1_INT2_COIL1") (pintype "bidirectional"))
    )
    (net (code "277") (name "unconnected-(U$8-PadINT1_INT2_COIL2)") (class "Default")
      (node (ref "U$8") (pin "INT1_INT2_COIL2") (pinfunction "INT1_INT2_COIL2_INT1_INT2_COIL2") (pintype "bidirectional"))
    )
    (net (code "278") (name "unconnected-(U$8-PadINT1_INT2_COIL3)") (class "Default")
      (node (ref "U$8") (pin "INT1_INT2_COIL3") (pinfunction "INT1_INT2_COIL3_INT1_INT2_COIL3") (pintype "bidirectional"))
    )
    (net (code "279") (name "unconnected-(U$8-PadTOP_INT1_COIL0)") (class "Default")
      (node (ref "U$8") (pin "TOP_INT1_COIL0") (pinfunction "TOP_INT1_COIL0_TOP_INT1_COIL0") (pintype "bidirectional"))
    )
    (net (code "280") (name "unconnected-(U$8-PadTOP_INT1_COIL1)") (class "Default")
      (node (ref "U$8") (pin "TOP_INT1_COIL1") (pinfunction "TOP_INT1_COIL1_TOP_INT1_COIL1") (pintype "bidirectional"))
    )
    (net (code "281") (name "unconnected-(U$8-PadTOP_INT1_COIL2)") (class "Default")
      (node (ref "U$8") (pin "TOP_INT1_COIL2") (pinfunction "TOP_INT1_COIL2_TOP_INT1_COIL2") (pintype "bidirectional"))
    )
    (net (code "282") (name "unconnected-(U$8-PadTOP_INT1_COIL3)") (class "Default")
      (node (ref "U$8") (pin "TOP_INT1_COIL3") (pinfunction "TOP_INT1_COIL3_TOP_INT1_COIL3") (pintype "bidirectional"))
    )
    (net (code "283") (name "unconnected-(U$9-PadINT1_INT2_COIL0)") (class "Default")
      (node (ref "U$9") (pin "INT1_INT2_COIL0") (pinfunction "INT1_INT2_COIL0_INT1_INT2_COIL0") (pintype "bidirectional"))
    )
    (net (code "284") (name "unconnected-(U$9-PadINT1_INT2_COIL1)") (class "Default")
      (node (ref "U$9") (pin "INT1_INT2_COIL1") (pinfunction "INT1_INT2_COIL1_INT1_INT2_COIL1") (pintype "bidirectional"))
    )
    (net (code "285") (name "unconnected-(U$9-PadINT1_INT2_COIL2)") (class "Default")
      (node (ref "U$9") (pin "INT1_INT2_COIL2") (pinfunction "INT1_INT2_COIL2_INT1_INT2_COIL2") (pintype "bidirectional"))
    )
    (net (code "286") (name "unconnected-(U$9-PadINT1_INT2_COIL3)") (class "Default")
      (node (ref "U$9") (pin "INT1_INT2_COIL3") (pinfunction "INT1_INT2_COIL3_INT1_INT2_COIL3") (pintype "bidirectional"))
    )
    (net (code "287") (name "unconnected-(U$9-PadTOP_INT1_COIL0)") (class "Default")
      (node (ref "U$9") (pin "TOP_INT1_COIL0") (pinfunction "TOP_INT1_COIL0_TOP_INT1_COIL0") (pintype "bidirectional"))
    )
    (net (code "288") (name "unconnected-(U$9-PadTOP_INT1_COIL1)") (class "Default")
      (node (ref "U$9") (pin "TOP_INT1_COIL1") (pinfunction "TOP_INT1_COIL1_TOP_INT1_COIL1") (pintype "bidirectional"))
    )
    (net (code "289") (name "unconnected-(U$9-PadTOP_INT1_COIL2)") (class "Default")
      (node (ref "U$9") (pin "TOP_INT1_COIL2") (pinfunction "TOP_INT1_COIL2_TOP_INT1_COIL2") (pintype "bidirectional"))
    )
    (net (code "290") (name "unconnected-(U$9-PadTOP_INT1_COIL3)") (class "Default")
      (node (ref "U$9") (pin "TOP_INT1_COIL3") (pinfunction "TOP_INT1_COIL3_TOP_INT1_COIL3") (pintype "bidirectional"))
    )
    (net (code "291") (name "unconnected-(U$10-PadINT1_INT2_COIL0)") (class "Default")
      (node (ref "U$10") (pin "INT1_INT2_COIL0") (pinfunction "INT1_INT2_COIL0_INT1_INT2_COIL0") (pintype "bidirectional"))
    )
    (net (code "292") (name "unconnected-(U$10-PadINT1_INT2_COIL1)") (class "Default")
      (node (ref "U$10") (pin "INT1_INT2_COIL1") (pinfunction "INT1_INT2_COIL1_INT1_INT2_COIL1") (pintype "bidirectional"))
    )
    (net (code "293") (name "unconnected-(U$10-PadINT1_INT2_COIL2)") (class "Default")
      (node (ref "U$10") (pin "INT1_INT2_COIL2") (pinfunction "INT1_INT2_COIL2_INT1_INT2_COIL2") (pintype "bidirectional"))
    )
    (net (code "294") (name "unconnected-(U$10-PadINT1_INT2_COIL3)") (class "Default")
      (node (ref "U$10") (pin "INT1_INT2_COIL3") (pinfunction "INT1_INT2_COIL3_INT1_INT2_COIL3") (pintype "bidirectional"))
    )
    (net (code "295") (name "unconnected-(U$10-PadTOP_INT1_COIL0)") (class "Default")
      (node (ref "U$10") (pin "TOP_INT1_COIL0") (pinfunction "TOP_INT1_COIL0_TOP_INT1_COIL0") (pintype "bidirectional"))
    )
    (net (code "296") (name "unconnected-(U$10-PadTOP_INT1_COIL1)") (class "Default")
      (node (ref "U$10") (pin "TOP_INT1_COIL1") (pinfunction "TOP_INT1_COIL1_TOP_INT1_COIL1") (pintype "bidirectional"))
    )
    (net (code "297") (name "unconnected-(U$10-PadTOP_INT1_COIL2)") (class "Default")
      (node (ref "U$10") (pin "TOP_INT1_COIL2") (pinfunction "TOP_INT1_COIL2_TOP_INT1_COIL2") (pintype "bidirectional"))
    )
    (net (code "298") (name "unconnected-(U$10-PadTOP_INT1_COIL3)") (class "Default")
      (node (ref "U$10") (pin "TOP_INT1_COIL3") (pinfunction "TOP_INT1_COIL3_TOP_INT1_COIL3") (pintype "bidirectional"))
    )
    (net (code "299") (name "unconnected-(U$12-PadINT1_INT2_COIL0)") (class "Default")
      (node (ref "U$12") (pin "INT1_INT2_COIL0") (pinfunction "INT1_INT2_COIL0_INT1_INT2_COIL0") (pintype "bidirectional"))
    )
    (net (code "300") (name "unconnected-(U$12-PadINT1_INT2_COIL1)") (class "Default")
      (node (ref "U$12") (pin "INT1_INT2_COIL1") (pinfunction "INT1_INT2_COIL1_INT1_INT2_COIL1") (pintype "bidirectional"))
    )
    (net (code "301") (name "unconnected-(U$12-PadINT1_INT2_COIL2)") (class "Default")
      (node (ref "U$12") (pin "INT1_INT2_COIL2") (pinfunction "INT1_INT2_COIL2_INT1_INT2_COIL2") (pintype "bidirectional"))
    )
    (net (code "302") (name "unconnected-(U$12-PadINT1_INT2_COIL3)") (class "Default")
      (node (ref "U$12") (pin "INT1_INT2_COIL3") (pinfunction "INT1_INT2_COIL3_INT1_INT2_COIL3") (pintype "bidirectional"))
    )
    (net (code "303") (name "unconnected-(U$12-PadTOP_INT1_COIL0)") (class "Default")
      (node (ref "U$12") (pin "TOP_INT1_COIL0") (pinfunction "TOP_INT1_COIL0_TOP_INT1_COIL0") (pintype "bidirectional"))
    )
    (net (code "304") (name "unconnected-(U$12-PadTOP_INT1_COIL1)") (class "Default")
      (node (ref "U$12") (pin "TOP_INT1_COIL1") (pinfunction "TOP_INT1_COIL1_TOP_INT1_COIL1") (pintype "bidirectional"))
    )
    (net (code "305") (name "unconnected-(U$12-PadTOP_INT1_COIL2)") (class "Default")
      (node (ref "U$12") (pin "TOP_INT1_COIL2") (pinfunction "TOP_INT1_COIL2_TOP_INT1_COIL2") (pintype "bidirectional"))
    )
    (net (code "306") (name "unconnected-(U$12-PadTOP_INT1_COIL3)") (class "Default")
      (node (ref "U$12") (pin "TOP_INT1_COIL3") (pinfunction "TOP_INT1_COIL3_TOP_INT1_COIL3") (pintype "bidirectional"))
    )
    (net (code "307") (name "unconnected-(U$14-PadINT1_INT2_COIL0)") (class "Default")
      (node (ref "U$14") (pin "INT1_INT2_COIL0") (pinfunction "INT1_INT2_COIL0_INT1_INT2_COIL0") (pintype "bidirectional"))
    )
    (net (code "308") (name "unconnected-(U$14-PadINT1_INT2_COIL1)") (class "Default")
      (node (ref "U$14") (pin "INT1_INT2_COIL1") (pinfunction "INT1_INT2_COIL1_INT1_INT2_COIL1") (pintype "bidirectional"))
    )
    (net (code "309") (name "unconnected-(U$14-PadINT1_INT2_COIL2)") (class "Default")
      (node (ref "U$14") (pin "INT1_INT2_COIL2") (pinfunction "INT1_INT2_COIL2_INT1_INT2_COIL2") (pintype "bidirectional"))
    )
    (net (code "310") (name "unconnected-(U$14-PadINT1_INT2_COIL3)") (class "Default")
      (node (ref "U$14") (pin "INT1_INT2_COIL3") (pinfunction "INT1_INT2_COIL3_INT1_INT2_COIL3") (pintype "bidirectional"))
    )
    (net (code "311") (name "unconnected-(U$14-PadTOP_INT1_COIL0)") (class "Default")
      (node (ref "U$14") (pin "TOP_INT1_COIL0") (pinfunction "TOP_INT1_COIL0_TOP_INT1_COIL0") (pintype "bidirectional"))
    )
    (net (code "312") (name "unconnected-(U$14-PadTOP_INT1_COIL1)") (class "Default")
      (node (ref "U$14") (pin "TOP_INT1_COIL1") (pinfunction "TOP_INT1_COIL1_TOP_INT1_COIL1") (pintype "bidirectional"))
    )
    (net (code "313") (name "unconnected-(U$14-PadTOP_INT1_COIL2)") (class "Default")
      (node (ref "U$14") (pin "TOP_INT1_COIL2") (pinfunction "TOP_INT1_COIL2_TOP_INT1_COIL2") (pintype "bidirectional"))
    )
    (net (code "314") (name "unconnected-(U$14-PadTOP_INT1_COIL3)") (class "Default")
      (node (ref "U$14") (pin "TOP_INT1_COIL3") (pinfunction "TOP_INT1_COIL3_TOP_INT1_COIL3") (pintype "bidirectional"))
    )
    (net (code "315") (name "unconnected-(U$16-PadINT1_INT2_COIL0)") (class "Default")
      (node (ref "U$16") (pin "INT1_INT2_COIL0") (pinfunction "INT1_INT2_COIL0_INT1_INT2_COIL0") (pintype "bidirectional"))
    )
    (net (code "316") (name "unconnected-(U$16-PadINT1_INT2_COIL1)") (class "Default")
      (node (ref "U$16") (pin "INT1_INT2_COIL1") (pinfunction "INT1_INT2_COIL1_INT1_INT2_COIL1") (pintype "bidirectional"))
    )
    (net (code "317") (name "unconnected-(U$16-PadINT1_INT2_COIL2)") (class "Default")
      (node (ref "U$16") (pin "INT1_INT2_COIL2") (pinfunction "INT1_INT2_COIL2_INT1_INT2_COIL2") (pintype "bidirectional"))
    )
    (net (code "318") (name "unconnected-(U$16-PadINT1_INT2_COIL3)") (class "Default")
      (node (ref "U$16") (pin "INT1_INT2_COIL3") (pinfunction "INT1_INT2_COIL3_INT1_INT2_COIL3") (pintype "bidirectional"))
    )
    (net (code "319") (name "unconnected-(U$16-PadTOP_INT1_COIL0)") (class "Default")
      (node (ref "U$16") (pin "TOP_INT1_COIL0") (pinfunction "TOP_INT1_COIL0_TOP_INT1_COIL0") (pintype "bidirectional"))
    )
    (net (code "320") (name "unconnected-(U$16-PadTOP_INT1_COIL1)") (class "Default")
      (node (ref "U$16") (pin "TOP_INT1_COIL1") (pinfunction "TOP_INT1_COIL1_TOP_INT1_COIL1") (pintype "bidirectional"))
    )
    (net (code "321") (name "unconnected-(U$16-PadTOP_INT1_COIL2)") (class "Default")
      (node (ref "U$16") (pin "TOP_INT1_COIL2") (pinfunction "TOP_INT1_COIL2_TOP_INT1_COIL2") (pintype "bidirectional"))
    )
    (net (code "322") (name "unconnected-(U$16-PadTOP_INT1_COIL3)") (class "Default")
      (node (ref "U$16") (pin "TOP_INT1_COIL3") (pinfunction "TOP_INT1_COIL3_TOP_INT1_COIL3") (pintype "bidirectional"))
    )
    (net (code "323") (name "unconnected-(U$19-INT1_INT2_COIL2-PadINT1_INT2_COIL2B)") (class "Default")
      (node (ref "U$19") (pin "INT1_INT2_COIL2B") (pinfunction "INT1_INT2_COIL2_INT1_INT2_COIL2B") (pintype "bidirectional"))
    )
    (net (code "324") (name "unconnected-(U$19-PadINT1_INT2_COIL0)") (class "Default")
      (node (ref "U$19") (pin "INT1_INT2_COIL0") (pinfunction "INT1_INT2_COIL0_INT1_INT2_COIL0") (pintype "bidirectional"))
    )
    (net (code "325") (name "unconnected-(U$19-PadINT1_INT2_COIL1)") (class "Default")
      (node (ref "U$19") (pin "INT1_INT2_COIL1") (pinfunction "INT1_INT2_COIL1_INT1_INT2_COIL1") (pintype "bidirectional"))
    )
    (net (code "326") (name "unconnected-(U$19-PadINT1_INT2_COIL3)") (class "Default")
      (node (ref "U$19") (pin "INT1_INT2_COIL3") (pinfunction "INT1_INT2_COIL3_INT1_INT2_COIL3") (pintype "bidirectional"))
    )
    (net (code "327") (name "unconnected-(U$19-PadTOP_INT1_COIL0)") (class "Default")
      (node (ref "U$19") (pin "TOP_INT1_COIL0") (pinfunction "TOP_INT1_COIL0_TOP_INT1_COIL0") (pintype "bidirectional"))
    )
    (net (code "328") (name "unconnected-(U$19-PadTOP_INT1_COIL1)") (class "Default")
      (node (ref "U$19") (pin "TOP_INT1_COIL1") (pinfunction "TOP_INT1_COIL1_TOP_INT1_COIL1") (pintype "bidirectional"))
    )
    (net (code "329") (name "unconnected-(U$19-PadTOP_INT1_COIL3)") (class "Default")
      (node (ref "U$19") (pin "TOP_INT1_COIL3") (pinfunction "TOP_INT1_COIL3_TOP_INT1_COIL3") (pintype "bidirectional"))
    )
    (net (code "330") (name "unconnected-(U$19-TOP_INT1_COIL2-PadTOP_INT1_COIL12B)") (class "Default")
      (node (ref "U$19") (pin "TOP_INT1_COIL12B") (pinfunction "TOP_INT1_COIL2_TOP_INT1_COIL12B") (pintype "bidirectional"))
    )
    (net (code "331") (name "unconnected-(U$21-INT1_INT2_COIL2-PadINT1_INT2_COIL2B)") (class "Default")
      (node (ref "U$21") (pin "INT1_INT2_COIL2B") (pinfunction "INT1_INT2_COIL2_INT1_INT2_COIL2B") (pintype "bidirectional"))
    )
    (net (code "332") (name "unconnected-(U$21-PadINT1_INT2_COIL0)") (class "Default")
      (node (ref "U$21") (pin "INT1_INT2_COIL0") (pinfunction "INT1_INT2_COIL0_INT1_INT2_COIL0") (pintype "bidirectional"))
    )
    (net (code "333") (name "unconnected-(U$21-PadINT1_INT2_COIL1)") (class "Default")
      (node (ref "U$21") (pin "INT1_INT2_COIL1") (pinfunction "INT1_INT2_COIL1_INT1_INT2_COIL1") (pintype "bidirectional"))
    )
    (net (code "334") (name "unconnected-(U$21-PadINT1_INT2_COIL3)") (class "Default")
      (node (ref "U$21") (pin "INT1_INT2_COIL3") (pinfunction "INT1_INT2_COIL3_INT1_INT2_COIL3") (pintype "bidirectional"))
    )
    (net (code "335") (name "unconnected-(U$21-PadTOP_INT1_COIL0)") (class "Default")
      (node (ref "U$21") (pin "TOP_INT1_COIL0") (pinfunction "TOP_INT1_COIL0_TOP_INT1_COIL0") (pintype "bidirectional"))
    )
    (net (code "336") (name "unconnected-(U$21-PadTOP_INT1_COIL1)") (class "Default")
      (node (ref "U$21") (pin "TOP_INT1_COIL1") (pinfunction "TOP_INT1_COIL1_TOP_INT1_COIL1") (pintype "bidirectional"))
    )
    (net (code "337") (name "unconnected-(U$21-PadTOP_INT1_COIL3)") (class "Default")
      (node (ref "U$21") (pin "TOP_INT1_COIL3") (pinfunction "TOP_INT1_COIL3_TOP_INT1_COIL3") (pintype "bidirectional"))
    )
    (net (code "338") (name "unconnected-(U$21-TOP_INT1_COIL2-PadTOP_INT1_COIL12B)") (class "Default")
      (node (ref "U$21") (pin "TOP_INT1_COIL12B") (pinfunction "TOP_INT1_COIL2_TOP_INT1_COIL12B") (pintype "bidirectional"))
    )
    (net (code "339") (name "unconnected-(U$23-INT1_INT2_COIL2-PadINT1_INT2_COIL2B)") (class "Default")
      (node (ref "U$23") (pin "INT1_INT2_COIL2B") (pinfunction "INT1_INT2_COIL2_INT1_INT2_COIL2B") (pintype "bidirectional"))
    )
    (net (code "340") (name "unconnected-(U$23-PadINT1_INT2_COIL0)") (class "Default")
      (node (ref "U$23") (pin "INT1_INT2_COIL0") (pinfunction "INT1_INT2_COIL0_INT1_INT2_COIL0") (pintype "bidirectional"))
    )
    (net (code "341") (name "unconnected-(U$23-PadINT1_INT2_COIL1)") (class "Default")
      (node (ref "U$23") (pin "INT1_INT2_COIL1") (pinfunction "INT1_INT2_COIL1_INT1_INT2_COIL1") (pintype "bidirectional"))
    )
    (net (code "342") (name "unconnected-(U$23-PadINT1_INT2_COIL3)") (class "Default")
      (node (ref "U$23") (pin "INT1_INT2_COIL3") (pinfunction "INT1_INT2_COIL3_INT1_INT2_COIL3") (pintype "bidirectional"))
    )
    (net (code "343") (name "unconnected-(U$23-PadTOP_INT1_COIL0)") (class "Default")
      (node (ref "U$23") (pin "TOP_INT1_COIL0") (pinfunction "TOP_INT1_COIL0_TOP_INT1_COIL0") (pintype "bidirectional"))
    )
    (net (code "344") (name "unconnected-(U$23-PadTOP_INT1_COIL1)") (class "Default")
      (node (ref "U$23") (pin "TOP_INT1_COIL1") (pinfunction "TOP_INT1_COIL1_TOP_INT1_COIL1") (pintype "bidirectional"))
    )
    (net (code "345") (name "unconnected-(U$23-PadTOP_INT1_COIL3)") (class "Default")
      (node (ref "U$23") (pin "TOP_INT1_COIL3") (pinfunction "TOP_INT1_COIL3_TOP_INT1_COIL3") (pintype "bidirectional"))
    )
    (net (code "346") (name "unconnected-(U$23-TOP_INT1_COIL2-PadTOP_INT1_COIL12B)") (class "Default")
      (node (ref "U$23") (pin "TOP_INT1_COIL12B") (pinfunction "TOP_INT1_COIL2_TOP_INT1_COIL12B") (pintype "bidirectional"))
    )
    (net (code "347") (name "unconnected-(U$25-INT1_INT2_COIL2-PadINT1_INT2_COIL2B)") (class "Default")
      (node (ref "U$25") (pin "INT1_INT2_COIL2B") (pinfunction "INT1_INT2_COIL2_INT1_INT2_COIL2B") (pintype "bidirectional"))
    )
    (net (code "348") (name "unconnected-(U$25-PadINT1_INT2_COIL0)") (class "Default")
      (node (ref "U$25") (pin "INT1_INT2_COIL0") (pinfunction "INT1_INT2_COIL0_INT1_INT2_COIL0") (pintype "bidirectional"))
    )
    (net (code "349") (name "unconnected-(U$25-PadINT1_INT2_COIL1)") (class "Default")
      (node (ref "U$25") (pin "INT1_INT2_COIL1") (pinfunction "INT1_INT2_COIL1_INT1_INT2_COIL1") (pintype "bidirectional"))
    )
    (net (code "350") (name "unconnected-(U$25-PadINT1_INT2_COIL3)") (class "Default")
      (node (ref "U$25") (pin "INT1_INT2_COIL3") (pinfunction "INT1_INT2_COIL3_INT1_INT2_COIL3") (pintype "bidirectional"))
    )
    (net (code "351") (name "unconnected-(U$25-PadTOP_INT1_COIL0)") (class "Default")
      (node (ref "U$25") (pin "TOP_INT1_COIL0") (pinfunction "TOP_INT1_COIL0_TOP_INT1_COIL0") (pintype "bidirectional"))
    )
    (net (code "352") (name "unconnected-(U$25-PadTOP_INT1_COIL1)") (class "Default")
      (node (ref "U$25") (pin "TOP_INT1_COIL1") (pinfunction "TOP_INT1_COIL1_TOP_INT1_COIL1") (pintype "bidirectional"))
    )
    (net (code "353") (name "unconnected-(U$25-PadTOP_INT1_COIL3)") (class "Default")
      (node (ref "U$25") (pin "TOP_INT1_COIL3") (pinfunction "TOP_INT1_COIL3_TOP_INT1_COIL3") (pintype "bidirectional"))
    )
    (net (code "354") (name "unconnected-(U$25-TOP_INT1_COIL2-PadTOP_INT1_COIL12B)") (class "Default")
      (node (ref "U$25") (pin "TOP_INT1_COIL12B") (pinfunction "TOP_INT1_COIL2_TOP_INT1_COIL12B") (pintype "bidirectional"))
    )
    (net (code "355") (name "unconnected-(U$27-INT1_INT2_COIL2-PadINT1_INT2_COIL2B)") (class "Default")
      (node (ref "U$27") (pin "INT1_INT2_COIL2B") (pinfunction "INT1_INT2_COIL2_INT1_INT2_COIL2B") (pintype "bidirectional"))
    )
    (net (code "356") (name "unconnected-(U$27-PadINT1_INT2_COIL0)") (class "Default")
      (node (ref "U$27") (pin "INT1_INT2_COIL0") (pinfunction "INT1_INT2_COIL0_INT1_INT2_COIL0") (pintype "bidirectional"))
    )
    (net (code "357") (name "unconnected-(U$27-PadINT1_INT2_COIL1)") (class "Default")
      (node (ref "U$27") (pin "INT1_INT2_COIL1") (pinfunction "INT1_INT2_COIL1_INT1_INT2_COIL1") (pintype "bidirectional"))
    )
    (net (code "358") (name "unconnected-(U$27-PadINT1_INT2_COIL3)") (class "Default")
      (node (ref "U$27") (pin "INT1_INT2_COIL3") (pinfunction "INT1_INT2_COIL3_INT1_INT2_COIL3") (pintype "bidirectional"))
    )
    (net (code "359") (name "unconnected-(U$27-PadTOP_INT1_COIL0)") (class "Default")
      (node (ref "U$27") (pin "TOP_INT1_COIL0") (pinfunction "TOP_INT1_COIL0_TOP_INT1_COIL0") (pintype "bidirectional"))
    )
    (net (code "360") (name "unconnected-(U$27-PadTOP_INT1_COIL1)") (class "Default")
      (node (ref "U$27") (pin "TOP_INT1_COIL1") (pinfunction "TOP_INT1_COIL1_TOP_INT1_COIL1") (pintype "bidirectional"))
    )
    (net (code "361") (name "unconnected-(U$27-PadTOP_INT1_COIL3)") (class "Default")
      (node (ref "U$27") (pin "TOP_INT1_COIL3") (pinfunction "TOP_INT1_COIL3_TOP_INT1_COIL3") (pintype "bidirectional"))
    )
    (net (code "362") (name "unconnected-(U$27-TOP_INT1_COIL2-PadTOP_INT1_COIL12B)") (class "Default")
      (node (ref "U$27") (pin "TOP_INT1_COIL12B") (pinfunction "TOP_INT1_COIL2_TOP_INT1_COIL12B") (pintype "bidirectional"))
    )
    (net (code "363") (name "unconnected-(U$29-INT1_INT2_COIL2-PadINT1_INT2_COIL2B)") (class "Default")
      (node (ref "U$29") (pin "INT1_INT2_COIL2B") (pinfunction "INT1_INT2_COIL2_INT1_INT2_COIL2B") (pintype "bidirectional"))
    )
    (net (code "364") (name "unconnected-(U$29-PadINT1_INT2_COIL0)") (class "Default")
      (node (ref "U$29") (pin "INT1_INT2_COIL0") (pinfunction "INT1_INT2_COIL0_INT1_INT2_COIL0") (pintype "bidirectional"))
    )
    (net (code "365") (name "unconnected-(U$29-PadINT1_INT2_COIL1)") (class "Default")
      (node (ref "U$29") (pin "INT1_INT2_COIL1") (pinfunction "INT1_INT2_COIL1_INT1_INT2_COIL1") (pintype "bidirectional"))
    )
    (net (code "366") (name "unconnected-(U$29-PadINT1_INT2_COIL3)") (class "Default")
      (node (ref "U$29") (pin "INT1_INT2_COIL3") (pinfunction "INT1_INT2_COIL3_INT1_INT2_COIL3") (pintype "bidirectional"))
    )
    (net (code "367") (name "unconnected-(U$29-PadTOP_INT1_COIL0)") (class "Default")
      (node (ref "U$29") (pin "TOP_INT1_COIL0") (pinfunction "TOP_INT1_COIL0_TOP_INT1_COIL0") (pintype "bidirectional"))
    )
    (net (code "368") (name "unconnected-(U$29-PadTOP_INT1_COIL1)") (class "Default")
      (node (ref "U$29") (pin "TOP_INT1_COIL1") (pinfunction "TOP_INT1_COIL1_TOP_INT1_COIL1") (pintype "bidirectional"))
    )
    (net (code "369") (name "unconnected-(U$29-PadTOP_INT1_COIL3)") (class "Default")
      (node (ref "U$29") (pin "TOP_INT1_COIL3") (pinfunction "TOP_INT1_COIL3_TOP_INT1_COIL3") (pintype "bidirectional"))
    )
    (net (code "370") (name "unconnected-(U$29-TOP_INT1_COIL2-PadTOP_INT1_COIL12B)") (class "Default")
      (node (ref "U$29") (pin "TOP_INT1_COIL12B") (pinfunction "TOP_INT1_COIL2_TOP_INT1_COIL12B") (pintype "bidirectional"))
    )
    (net (code "371") (name "unconnected-(U$31-INT1_INT2_COIL2-PadINT1_INT2_COIL2B)") (class "Default")
      (node (ref "U$31") (pin "INT1_INT2_COIL2B") (pinfunction "INT1_INT2_COIL2_INT1_INT2_COIL2B") (pintype "bidirectional"))
    )
    (net (code "372") (name "unconnected-(U$31-PadINT1_INT2_COIL0)") (class "Default")
      (node (ref "U$31") (pin "INT1_INT2_COIL0") (pinfunction "INT1_INT2_COIL0_INT1_INT2_COIL0") (pintype "bidirectional"))
    )
    (net (code "373") (name "unconnected-(U$31-PadINT1_INT2_COIL1)") (class "Default")
      (node (ref "U$31") (pin "INT1_INT2_COIL1") (pinfunction "INT1_INT2_COIL1_INT1_INT2_COIL1") (pintype "bidirectional"))
    )
    (net (code "374") (name "unconnected-(U$31-PadINT1_INT2_COIL3)") (class "Default")
      (node (ref "U$31") (pin "INT1_INT2_COIL3") (pinfunction "INT1_INT2_COIL3_INT1_INT2_COIL3") (pintype "bidirectional"))
    )
    (net (code "375") (name "unconnected-(U$31-PadTOP_INT1_COIL0)") (class "Default")
      (node (ref "U$31") (pin "TOP_INT1_COIL0") (pinfunction "TOP_INT1_COIL0_TOP_INT1_COIL0") (pintype "bidirectional"))
    )
    (net (code "376") (name "unconnected-(U$31-PadTOP_INT1_COIL1)") (class "Default")
      (node (ref "U$31") (pin "TOP_INT1_COIL1") (pinfunction "TOP_INT1_COIL1_TOP_INT1_COIL1") (pintype "bidirectional"))
    )
    (net (code "377") (name "unconnected-(U$31-PadTOP_INT1_COIL3)") (class "Default")
      (node (ref "U$31") (pin "TOP_INT1_COIL3") (pinfunction "TOP_INT1_COIL3_TOP_INT1_COIL3") (pintype "bidirectional"))
    )
    (net (code "378") (name "unconnected-(U$31-TOP_INT1_COIL2-PadTOP_INT1_COIL12B)") (class "Default")
      (node (ref "U$31") (pin "TOP_INT1_COIL12B") (pinfunction "TOP_INT1_COIL2_TOP_INT1_COIL12B") (pintype "bidirectional"))
    )
    (net (code "379") (name "unconnected-(U$33-INT1_INT2_COIL2-PadINT1_INT2_COIL2B)") (class "Default")
      (node (ref "U$33") (pin "INT1_INT2_COIL2B") (pinfunction "INT1_INT2_COIL2_INT1_INT2_COIL2B") (pintype "bidirectional"))
    )
    (net (code "380") (name "unconnected-(U$33-PadINT1_INT2_COIL0)") (class "Default")
      (node (ref "U$33") (pin "INT1_INT2_COIL0") (pinfunction "INT1_INT2_COIL0_INT1_INT2_COIL0") (pintype "bidirectional"))
    )
    (net (code "381") (name "unconnected-(U$33-PadINT1_INT2_COIL1)") (class "Default")
      (node (ref "U$33") (pin "INT1_INT2_COIL1") (pinfunction "INT1_INT2_COIL1_INT1_INT2_COIL1") (pintype "bidirectional"))
    )
    (net (code "382") (name "unconnected-(U$33-PadINT1_INT2_COIL3)") (class "Default")
      (node (ref "U$33") (pin "INT1_INT2_COIL3") (pinfunction "INT1_INT2_COIL3_INT1_INT2_COIL3") (pintype "bidirectional"))
    )
    (net (code "383") (name "unconnected-(U$33-PadTOP_INT1_COIL0)") (class "Default")
      (node (ref "U$33") (pin "TOP_INT1_COIL0") (pinfunction "TOP_INT1_COIL0_TOP_INT1_COIL0") (pintype "bidirectional"))
    )
    (net (code "384") (name "unconnected-(U$33-PadTOP_INT1_COIL1)") (class "Default")
      (node (ref "U$33") (pin "TOP_INT1_COIL1") (pinfunction "TOP_INT1_COIL1_TOP_INT1_COIL1") (pintype "bidirectional"))
    )
    (net (code "385") (name "unconnected-(U$33-PadTOP_INT1_COIL3)") (class "Default")
      (node (ref "U$33") (pin "TOP_INT1_COIL3") (pinfunction "TOP_INT1_COIL3_TOP_INT1_COIL3") (pintype "bidirectional"))
    )
    (net (code "386") (name "unconnected-(U$33-TOP_INT1_COIL2-PadTOP_INT1_COIL12B)") (class "Default")
      (node (ref "U$33") (pin "TOP_INT1_COIL12B") (pinfunction "TOP_INT1_COIL2_TOP_INT1_COIL12B") (pintype "bidirectional"))
    )
    (net (code "387") (name "unconnected-(U$35-INT1_INT2_COIL2-PadINT1_INT2_COIL2B)") (class "Default")
      (node (ref "U$35") (pin "INT1_INT2_COIL2B") (pinfunction "INT1_INT2_COIL2_INT1_INT2_COIL2B") (pintype "bidirectional"))
    )
    (net (code "388") (name "unconnected-(U$35-PadINT1_INT2_COIL0)") (class "Default")
      (node (ref "U$35") (pin "INT1_INT2_COIL0") (pinfunction "INT1_INT2_COIL0_INT1_INT2_COIL0") (pintype "bidirectional"))
    )
    (net (code "389") (name "unconnected-(U$35-PadINT1_INT2_COIL1)") (class "Default")
      (node (ref "U$35") (pin "INT1_INT2_COIL1") (pinfunction "INT1_INT2_COIL1_INT1_INT2_COIL1") (pintype "bidirectional"))
    )
    (net (code "390") (name "unconnected-(U$35-PadINT1_INT2_COIL3)") (class "Default")
      (node (ref "U$35") (pin "INT1_INT2_COIL3") (pinfunction "INT1_INT2_COIL3_INT1_INT2_COIL3") (pintype "bidirectional"))
    )
    (net (code "391") (name "unconnected-(U$35-PadTOP_INT1_COIL0)") (class "Default")
      (node (ref "U$35") (pin "TOP_INT1_COIL0") (pinfunction "TOP_INT1_COIL0_TOP_INT1_COIL0") (pintype "bidirectional"))
    )
    (net (code "392") (name "unconnected-(U$35-PadTOP_INT1_COIL1)") (class "Default")
      (node (ref "U$35") (pin "TOP_INT1_COIL1") (pinfunction "TOP_INT1_COIL1_TOP_INT1_COIL1") (pintype "bidirectional"))
    )
    (net (code "393") (name "unconnected-(U$35-PadTOP_INT1_COIL3)") (class "Default")
      (node (ref "U$35") (pin "TOP_INT1_COIL3") (pinfunction "TOP_INT1_COIL3_TOP_INT1_COIL3") (pintype "bidirectional"))
    )
    (net (code "394") (name "unconnected-(U$35-TOP_INT1_COIL2-PadTOP_INT1_COIL12B)") (class "Default")
      (node (ref "U$35") (pin "TOP_INT1_COIL12B") (pinfunction "TOP_INT1_COIL2_TOP_INT1_COIL12B") (pintype "bidirectional"))
    )
    (net (code "395") (name "unconnected-(U$37-INT1_INT2_COIL2-PadINT1_INT2_COIL2B)") (class "Default")
      (node (ref "U$37") (pin "INT1_INT2_COIL2B") (pinfunction "INT1_INT2_COIL2_INT1_INT2_COIL2B") (pintype "bidirectional"))
    )
    (net (code "396") (name "unconnected-(U$37-PadINT1_INT2_COIL0)") (class "Default")
      (node (ref "U$37") (pin "INT1_INT2_COIL0") (pinfunction "INT1_INT2_COIL0_INT1_INT2_COIL0") (pintype "bidirectional"))
    )
    (net (code "397") (name "unconnected-(U$37-PadINT1_INT2_COIL1)") (class "Default")
      (node (ref "U$37") (pin "INT1_INT2_COIL1") (pinfunction "INT1_INT2_COIL1_INT1_INT2_COIL1") (pintype "bidirectional"))
    )
    (net (code "398") (name "unconnected-(U$37-PadINT1_INT2_COIL3)") (class "Default")
      (node (ref "U$37") (pin "INT1_INT2_COIL3") (pinfunction "INT1_INT2_COIL3_INT1_INT2_COIL3") (pintype "bidirectional"))
    )
    (net (code "399") (name "unconnected-(U$37-PadTOP_INT1_COIL0)") (class "Default")
      (node (ref "U$37") (pin "TOP_INT1_COIL0") (pinfunction "TOP_INT1_COIL0_TOP_INT1_COIL0") (pintype "bidirectional"))
    )
    (net (code "400") (name "unconnected-(U$37-PadTOP_INT1_COIL1)") (class "Default")
      (node (ref "U$37") (pin "TOP_INT1_COIL1") (pinfunction "TOP_INT1_COIL1_TOP_INT1_COIL1") (pintype "bidirectional"))
    )
    (net (code "401") (name "unconnected-(U$37-PadTOP_INT1_COIL3)") (class "Default")
      (node (ref "U$37") (pin "TOP_INT1_COIL3") (pinfunction "TOP_INT1_COIL3_TOP_INT1_COIL3") (pintype "bidirectional"))
    )
    (net (code "402") (name "unconnected-(U$37-TOP_INT1_COIL2-PadTOP_INT1_COIL12B)") (class "Default")
      (node (ref "U$37") (pin "TOP_INT1_COIL12B") (pinfunction "TOP_INT1_COIL2_TOP_INT1_COIL12B") (pintype "bidirectional"))
    )
  )
)
